# FPGA_1.net
KiCad netlist of a schematic drawn in Altium Designer
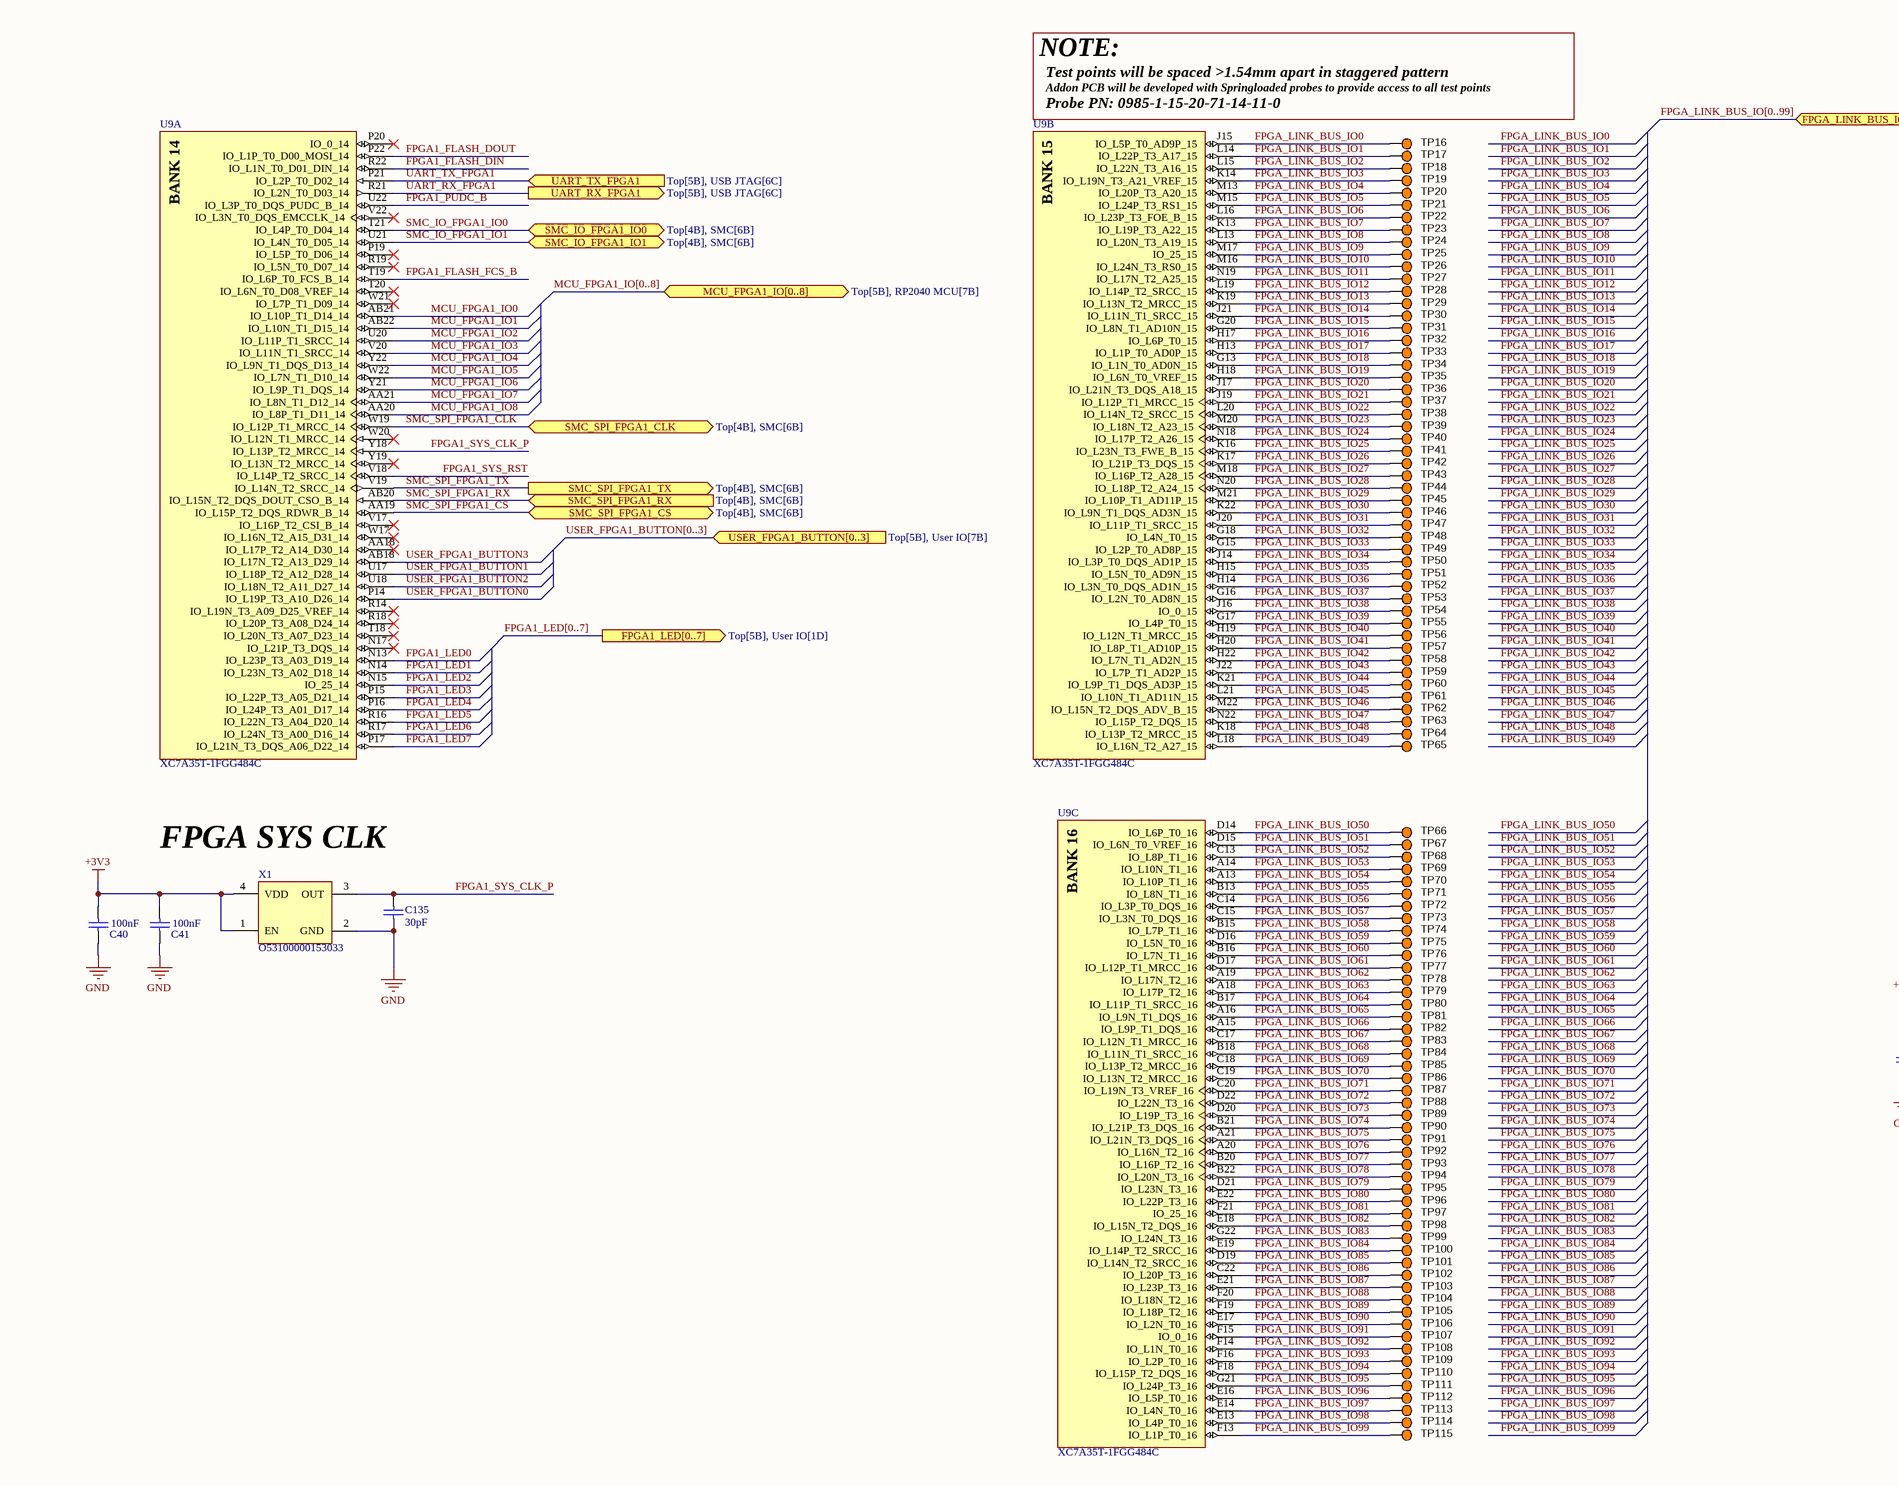
[diagram p0: FPGA_1.SchDoc, top left]
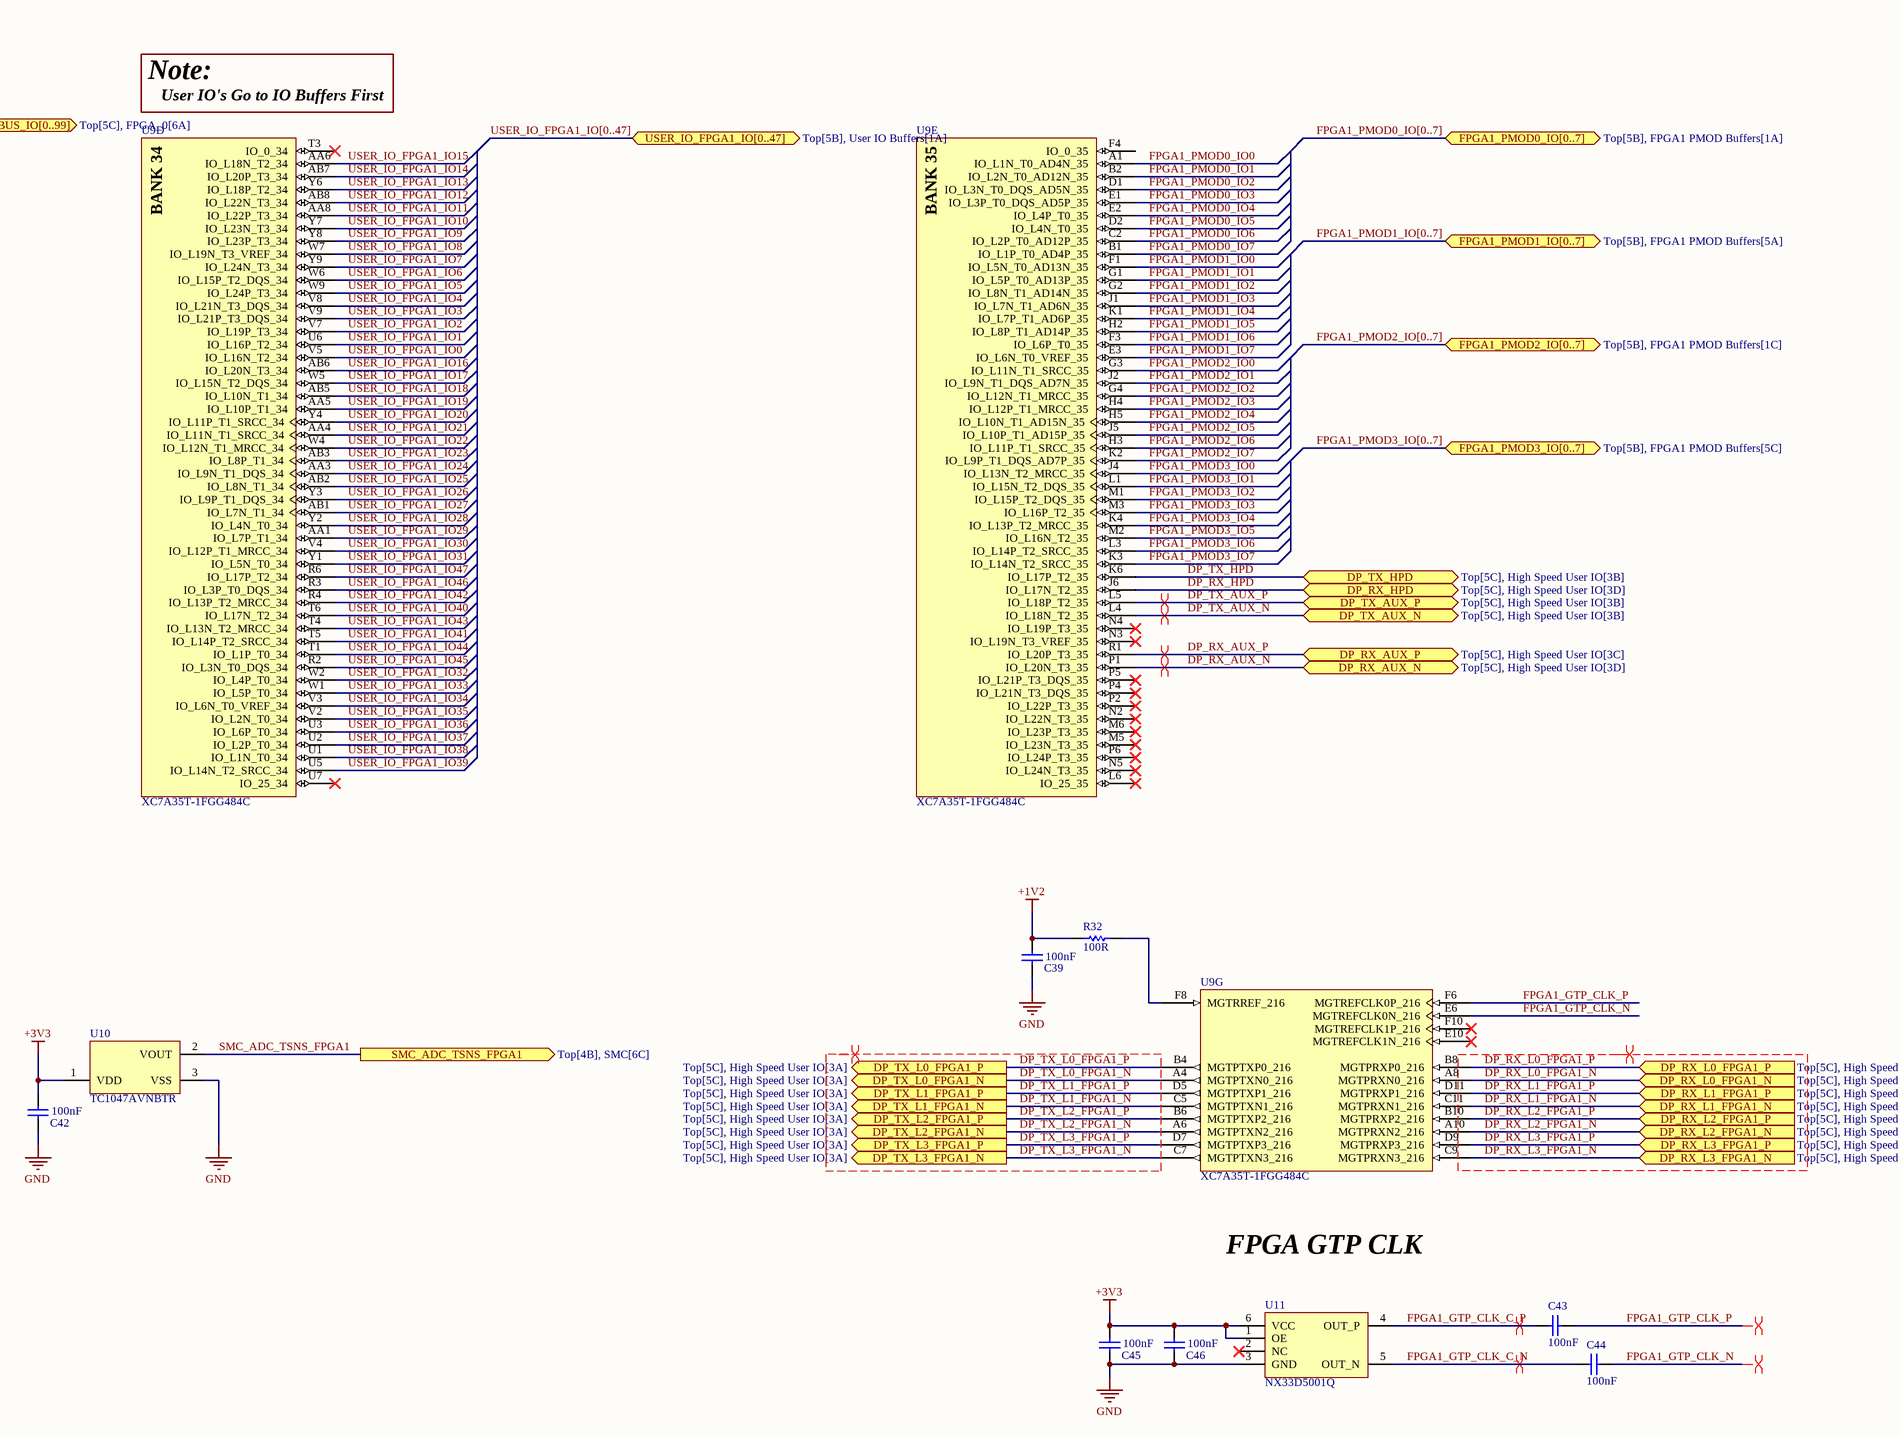
[diagram p1: FPGA_1.SchDoc, top right]
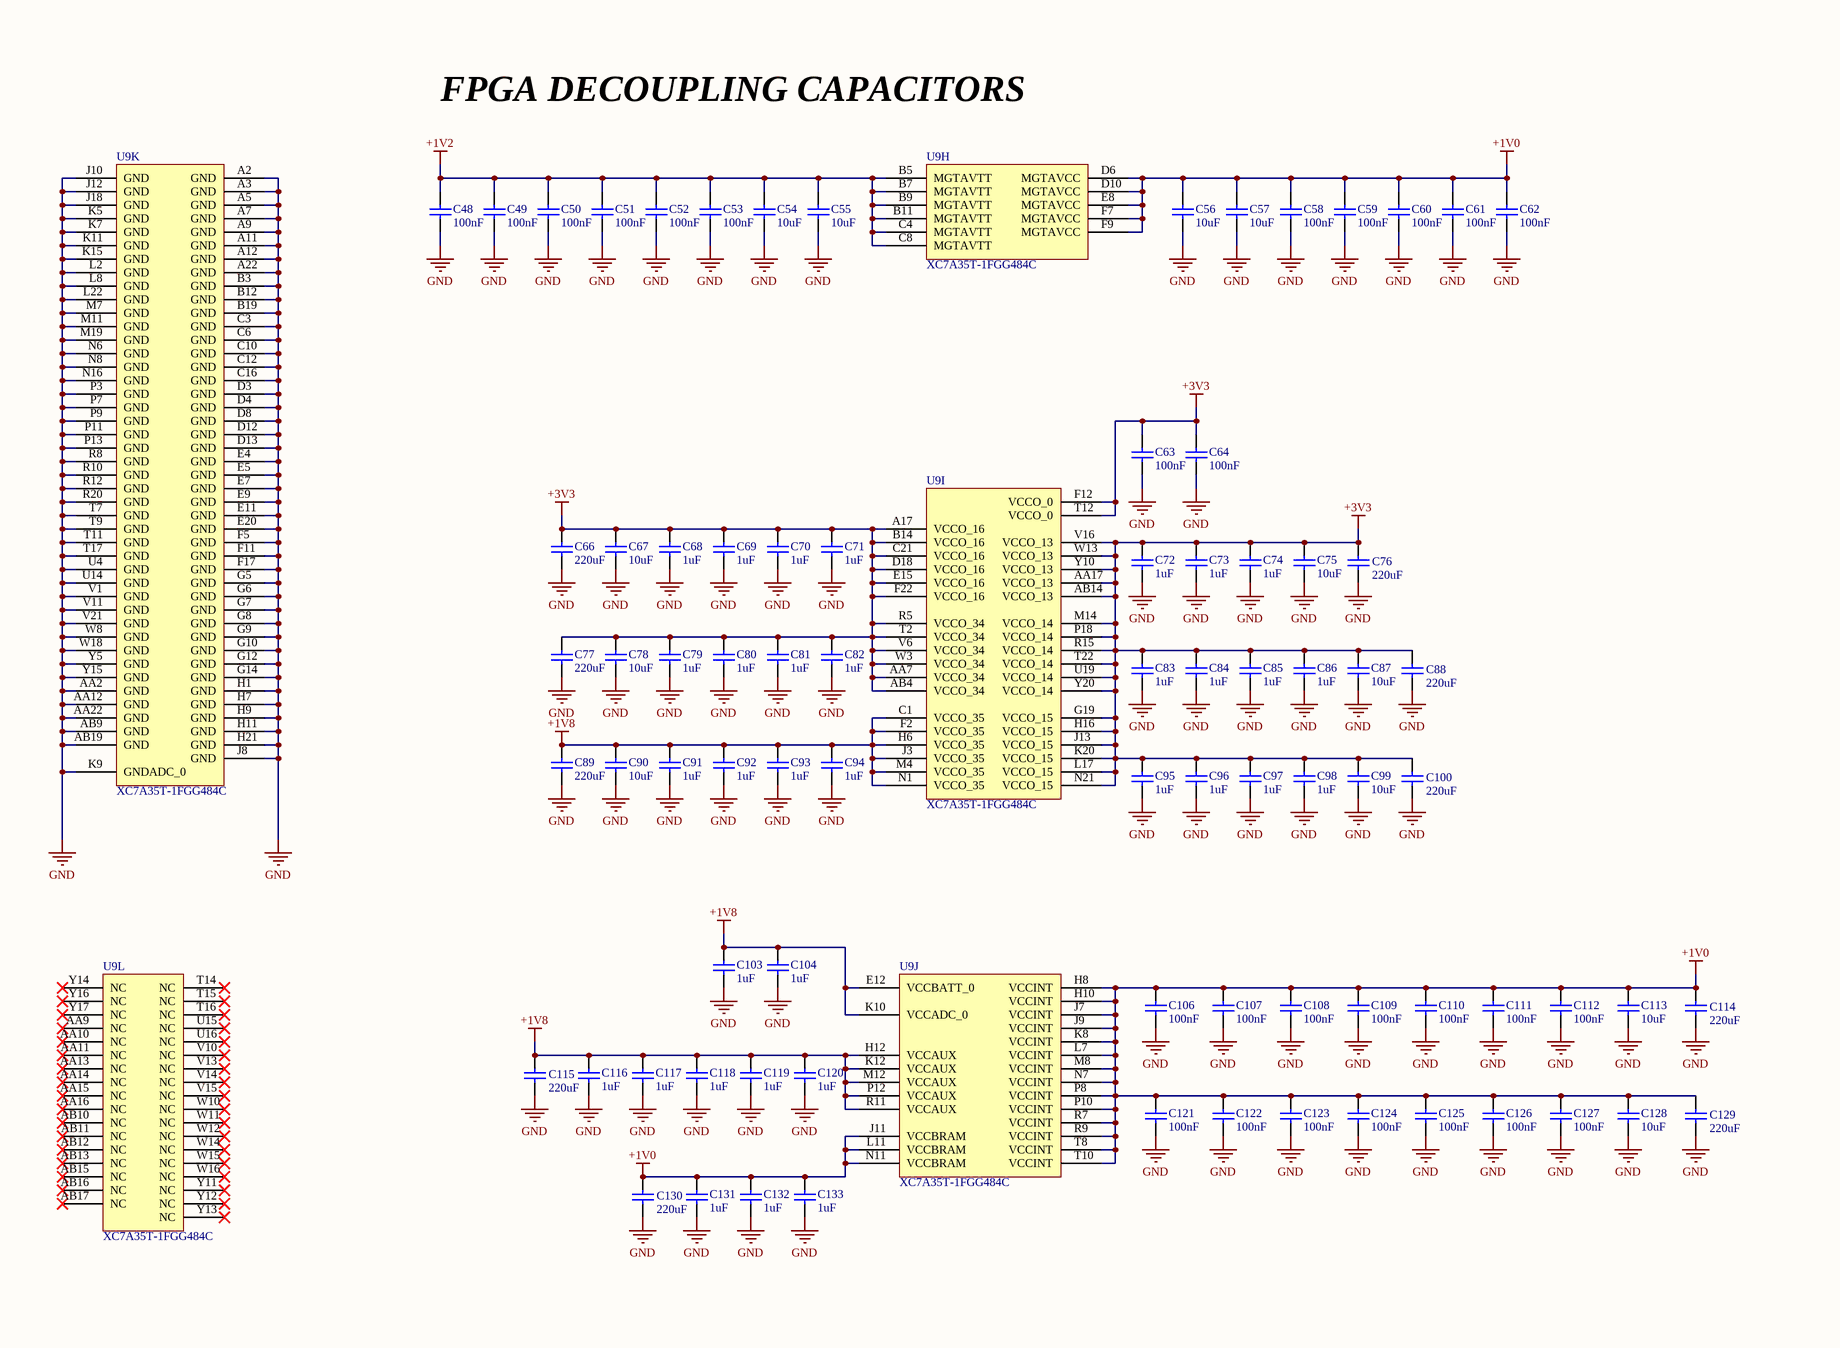
[diagram p2: FPGA_1.SchDoc, bottom left]
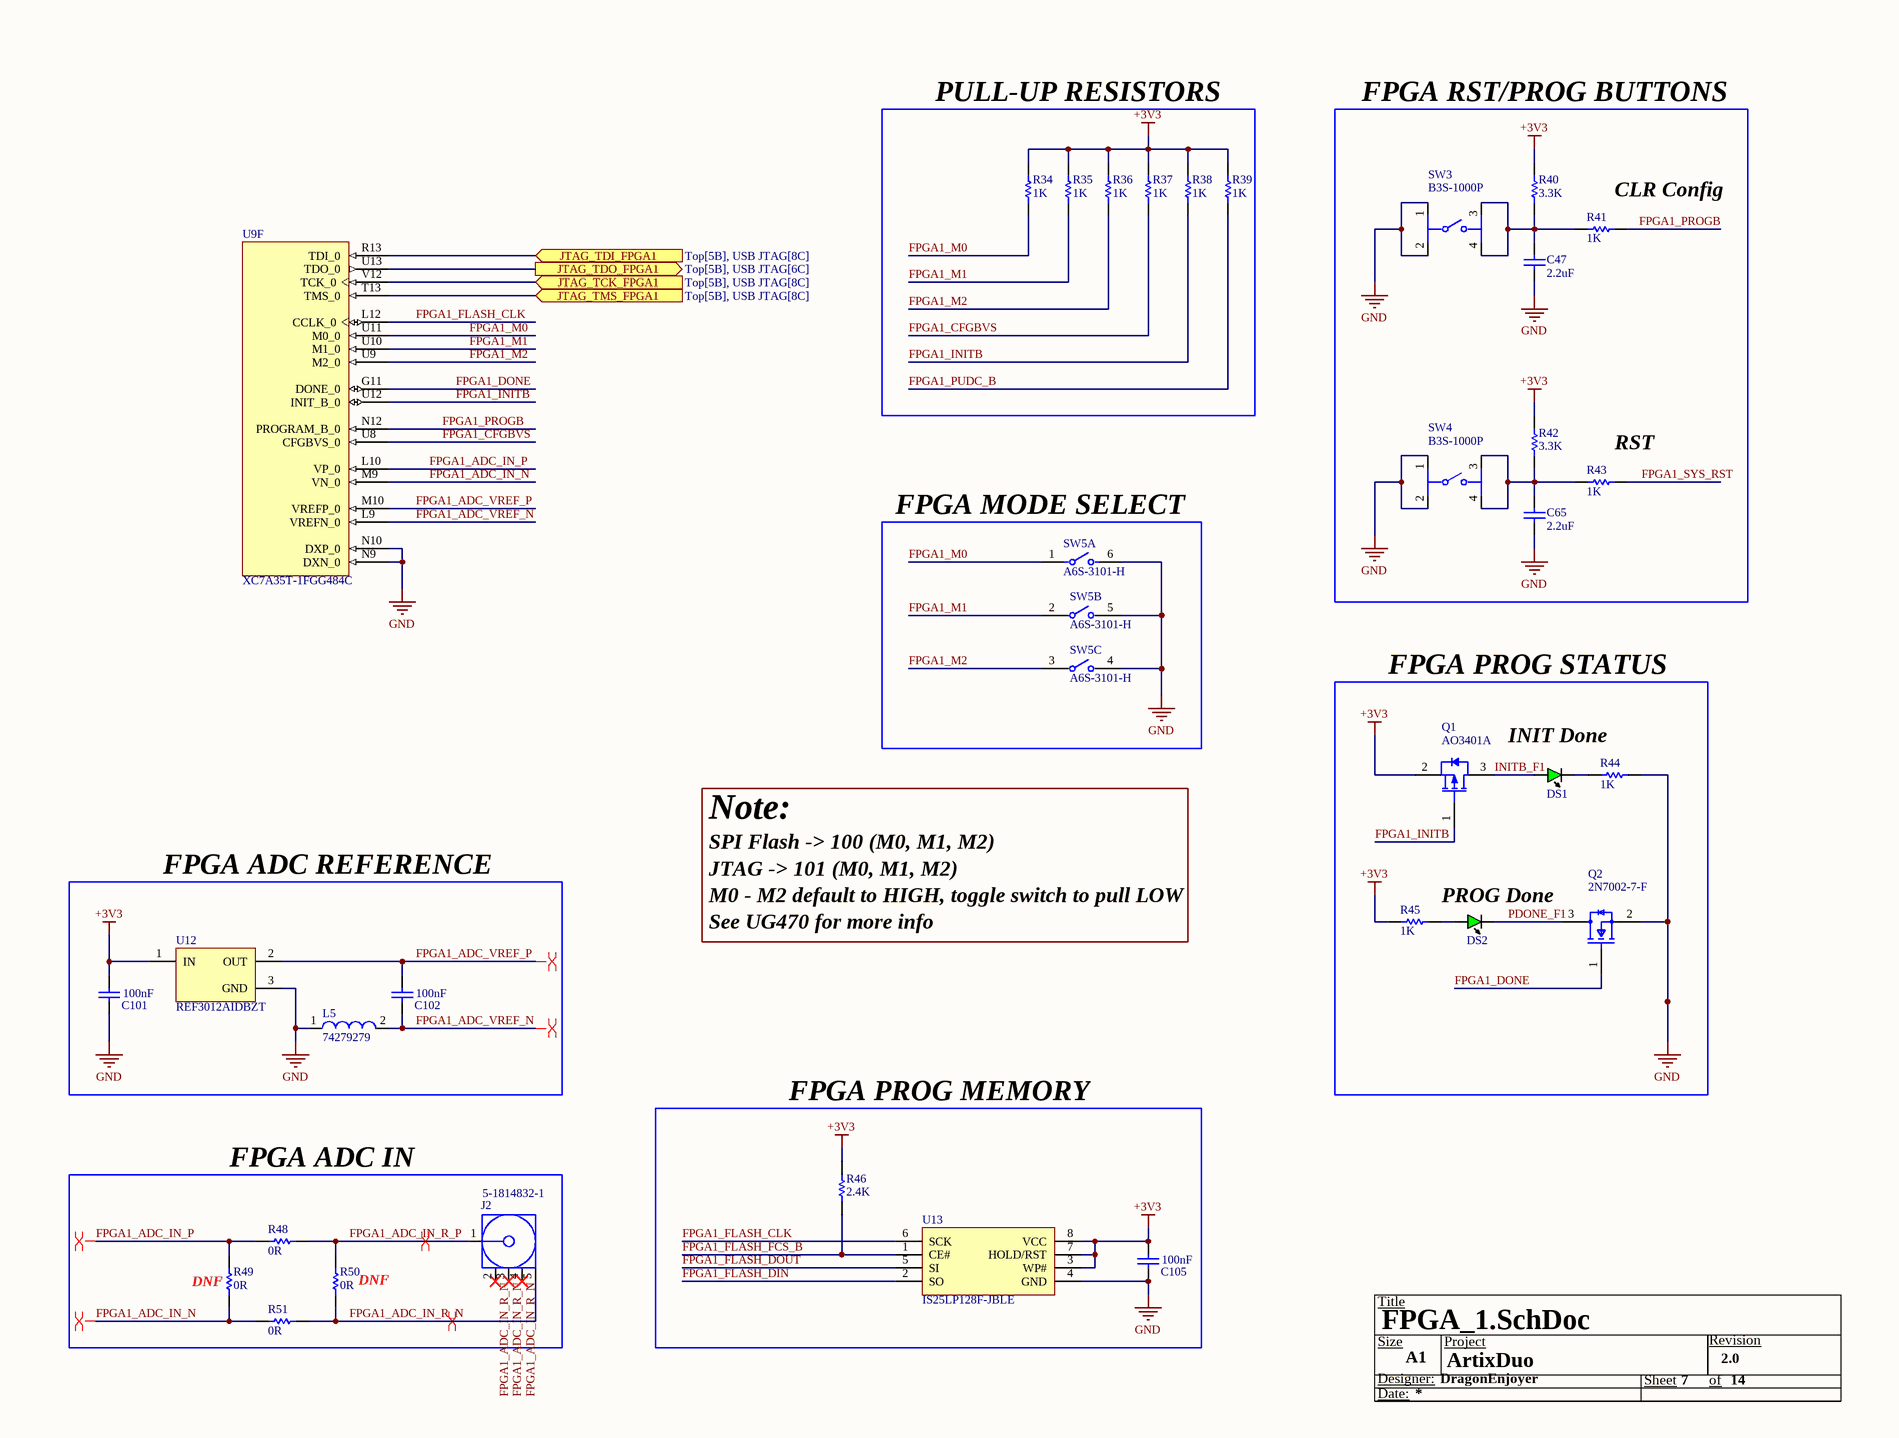
[diagram p3: FPGA_1.SchDoc, bottom right]

(export (version "E")
  (design (tool "Eeschema 10.0.6"))
  (components
    (comp (ref "C39")
      (value "100nF")
      (footprint "CAPC1005X05N")
      (description "Cap Ceramic 0.1uF 50V X7R 20% SMD 0402 125°C Paper T/R GRM155R71H104ME14J")
      (fields (field (name "VOLTAGE") "50V"))
      (libsource (lib "Main Workspace") (part "CAP"))
    )
    (comp (ref "C40")
      (value "100nF")
      (footprint "CAPC1005X05N")
      (description "Cap Ceramic 0.1uF 50V X7R 20% SMD 0402 125°C Paper T/R GRM155R71H104ME14J")
      (fields (field (name "VOLTAGE") "50V"))
      (libsource (lib "Main Workspace") (part "CAP"))
    )
    (comp (ref "C41")
      (value "100nF")
      (footprint "CAPC1005X05N")
      (description "Cap Ceramic 0.1uF 50V X7R 20% SMD 0402 125°C Paper T/R GRM155R71H104ME14J")
      (fields (field (name "VOLTAGE") "50V"))
      (libsource (lib "Main Workspace") (part "CAP"))
    )
    (comp (ref "C42")
      (value "100nF")
      (footprint "CAPC1005X05N")
      (description "Cap Ceramic 0.1uF 50V X7R 20% SMD 0402 125°C Paper T/R GRM155R71H104ME14J")
      (fields (field (name "VOLTAGE") "50V"))
      (libsource (lib "Main Workspace") (part "CAP"))
    )
    (comp (ref "C43")
      (value "100nF")
      (footprint "CAPC1005X05N")
      (description "Cap Ceramic 0.1uF 50V X7R 20% SMD 0402 125°C Paper T/R GRM155R71H104ME14J")
      (fields (field (name "VOLTAGE") "50V"))
      (libsource (lib "Main Workspace") (part "CAP"))
    )
    (comp (ref "C44")
      (value "100nF")
      (footprint "CAPC1005X05N")
      (description "Cap Ceramic 0.1uF 50V X7R 20% SMD 0402 125°C Paper T/R GRM155R71H104ME14J")
      (fields (field (name "VOLTAGE") "50V"))
      (libsource (lib "Main Workspace") (part "CAP"))
    )
    (comp (ref "C45")
      (value "100nF")
      (footprint "CAPC1005X05N")
      (description "Cap Ceramic 0.1uF 50V X7R 20% SMD 0402 125°C Paper T/R GRM155R71H104ME14J")
      (fields (field (name "VOLTAGE") "50V"))
      (libsource (lib "Main Workspace") (part "CAP"))
    )
    (comp (ref "C46")
      (value "100nF")
      (footprint "CAPC1005X05N")
      (description "Cap Ceramic 0.1uF 50V X7R 20% SMD 0402 125°C Paper T/R GRM155R71H104ME14J")
      (fields (field (name "VOLTAGE") "50V"))
      (libsource (lib "Main Workspace") (part "CAP"))
    )
    (comp (ref "C47")
      (value "2.2uF")
      (footprint "CAPC1005X55X25NL05T10")
      (description "GRM155R60J225ME15D")
      (fields (field (name "MANUFACTURER") "Murata"))
      (libsource (lib "Altium Content Vault") (part "CAP"))
    )
    (comp (ref "C48")
      (value "100nF")
      (footprint "CAPC1005X05N")
      (description "0402 0.1 uF 25 V ±10% Tolerance X7R SMT Multilayer Ceramic Capacitor")
      (fields (field (name "TOLERANCE") "10%") (field (name "Comment") "GRM155R71E104KE14J"))
      (libsource (lib "Main Workspace") (part "CAP"))
    )
    (comp (ref "C49")
      (value "100nF")
      (footprint "CAPC1005X05N")
      (description "0402 0.1 uF 25 V ±10% Tolerance X7R SMT Multilayer Ceramic Capacitor")
      (fields (field (name "TOLERANCE") "10%") (field (name "Comment") "GRM155R71E104KE14J"))
      (libsource (lib "Main Workspace") (part "CAP"))
    )
    (comp (ref "C50")
      (value "100nF")
      (footprint "CAPC1005X05N")
      (description "0402 0.1 uF 25 V ±10% Tolerance X7R SMT Multilayer Ceramic Capacitor")
      (fields (field (name "TOLERANCE") "10%") (field (name "Comment") "GRM155R71E104KE14J"))
      (libsource (lib "Main Workspace") (part "CAP"))
    )
    (comp (ref "C51")
      (value "100nF")
      (footprint "CAPC1005X05N")
      (description "0402 0.1 uF 25 V ±10% Tolerance X7R SMT Multilayer Ceramic Capacitor")
      (fields (field (name "TOLERANCE") "10%") (field (name "Comment") "GRM155R71E104KE14J"))
      (libsource (lib "Main Workspace") (part "CAP"))
    )
    (comp (ref "C52")
      (value "100nF")
      (footprint "CAPC1005X05N")
      (description "0402 0.1 uF 25 V ±10% Tolerance X7R SMT Multilayer Ceramic Capacitor")
      (fields (field (name "TOLERANCE") "10%") (field (name "Comment") "GRM155R71E104KE14J"))
      (libsource (lib "Main Workspace") (part "CAP"))
    )
    (comp (ref "C53")
      (value "100nF")
      (footprint "CAPC1005X05N")
      (description "0402 0.1 uF 25 V ±10% Tolerance X7R SMT Multilayer Ceramic Capacitor")
      (fields (field (name "TOLERANCE") "10%") (field (name "Comment") "GRM155R71E104KE14J"))
      (libsource (lib "Main Workspace") (part "CAP"))
    )
    (comp (ref "C54")
      (value "10uF")
      (footprint "CAPC1608X05N")
      (description "Cap 10UF 6.3VDC X5R 20% SMD 0603 Paper Tape")
      (fields (field (name "TOLERANCE") "20%") (field (name "Comment") "GRM185R60J106ME15J"))
      (libsource (lib "Main Workspace") (part "CAP"))
    )
    (comp (ref "C55")
      (value "10uF")
      (footprint "CAPC1608X05N")
      (description "Cap 10UF 6.3VDC X5R 20% SMD 0603 Paper Tape")
      (fields (field (name "TOLERANCE") "20%") (field (name "Comment") "GRM185R60J106ME15J"))
      (libsource (lib "Main Workspace") (part "CAP"))
    )
    (comp (ref "C56")
      (value "10uF")
      (footprint "CAPC1608X05N")
      (description "Cap 10UF 6.3VDC X5R 20% SMD 0603 Paper Tape")
      (fields (field (name "TOLERANCE") "20%") (field (name "Comment") "GRM185R60J106ME15J"))
      (libsource (lib "Main Workspace") (part "CAP"))
    )
    (comp (ref "C57")
      (value "10uF")
      (footprint "CAPC1608X05N")
      (description "Cap 10UF 6.3VDC X5R 20% SMD 0603 Paper Tape")
      (fields (field (name "TOLERANCE") "20%") (field (name "Comment") "GRM185R60J106ME15J"))
      (libsource (lib "Main Workspace") (part "CAP"))
    )
    (comp (ref "C58")
      (value "100nF")
      (footprint "CAPC1005X05N")
      (description "0402 0.1 uF 25 V ±10% Tolerance X7R SMT Multilayer Ceramic Capacitor")
      (fields (field (name "TOLERANCE") "10%") (field (name "Comment") "GRM155R71E104KE14J"))
      (libsource (lib "Main Workspace") (part "CAP"))
    )
    (comp (ref "C59")
      (value "100nF")
      (footprint "CAPC1005X05N")
      (description "0402 0.1 uF 25 V ±10% Tolerance X7R SMT Multilayer Ceramic Capacitor")
      (fields (field (name "TOLERANCE") "10%") (field (name "Comment") "GRM155R71E104KE14J"))
      (libsource (lib "Main Workspace") (part "CAP"))
    )
    (comp (ref "C60")
      (value "100nF")
      (footprint "CAPC1005X05N")
      (description "0402 0.1 uF 25 V ±10% Tolerance X7R SMT Multilayer Ceramic Capacitor")
      (fields (field (name "TOLERANCE") "10%") (field (name "Comment") "GRM155R71E104KE14J"))
      (libsource (lib "Main Workspace") (part "CAP"))
    )
    (comp (ref "C61")
      (value "100nF")
      (footprint "CAPC1005X05N")
      (description "0402 0.1 uF 25 V ±10% Tolerance X7R SMT Multilayer Ceramic Capacitor")
      (fields (field (name "TOLERANCE") "10%") (field (name "Comment") "GRM155R71E104KE14J"))
      (libsource (lib "Main Workspace") (part "CAP"))
    )
    (comp (ref "C62")
      (value "100nF")
      (footprint "CAPC1005X05N")
      (description "0402 0.1 uF 25 V ±10% Tolerance X7R SMT Multilayer Ceramic Capacitor")
      (fields (field (name "TOLERANCE") "10%") (field (name "Comment") "GRM155R71E104KE14J"))
      (libsource (lib "Main Workspace") (part "CAP"))
    )
    (comp (ref "C63")
      (value "100nF")
      (footprint "CAPC1005X05N")
      (description "0402 0.1 uF 25 V ±10% Tolerance X7R SMT Multilayer Ceramic Capacitor")
      (fields (field (name "TOLERANCE") "10%") (field (name "Comment") "GRM155R71E104KE14J"))
      (libsource (lib "Main Workspace") (part "CAP"))
    )
    (comp (ref "C64")
      (value "100nF")
      (footprint "CAPC1005X05N")
      (description "0402 0.1 uF 25 V ±10% Tolerance X7R SMT Multilayer Ceramic Capacitor")
      (fields (field (name "TOLERANCE") "10%") (field (name "Comment") "GRM155R71E104KE14J"))
      (libsource (lib "Main Workspace") (part "CAP"))
    )
    (comp (ref "C65")
      (value "2.2uF")
      (footprint "CAPC1005X55X25NL05T10")
      (description "GRM155R60J225ME15D")
      (fields (field (name "MANUFACTURER") "Murata"))
      (libsource (lib "Altium Content Vault") (part "CAP"))
    )
    (comp (ref "C66")
      (value "220uF")
      (footprint "CAPC3225X25N")
      (description "Cap Ceramic 220uF 6.3V X5R 20% SMD 1210 85°C Emboss T/R GRM32ER60J227ME05K")
      (libsource (lib "Main Workspace") (part "CAP"))
    )
    (comp (ref "C67")
      (value "10uF")
      (footprint "CAPC1608X05N")
      (description "Cap 10UF 6.3VDC X5R 20% SMD 0603 Paper Tape")
      (fields (field (name "TOLERANCE") "20%") (field (name "Comment") "GRM185R60J106ME15J"))
      (libsource (lib "Main Workspace") (part "CAP"))
    )
    (comp (ref "C68")
      (value "1uF")
      (footprint "CAPC1005X05N")
      (fields (field (name "TOLERANCE") "20%") (field (name "Comment") "GRM153R61A105ME95D"))
      (libsource (lib "Main Workspace") (part "CAP"))
    )
    (comp (ref "C69")
      (value "1uF")
      (footprint "CAPC1005X05N")
      (fields (field (name "TOLERANCE") "20%") (field (name "Comment") "GRM153R61A105ME95D"))
      (libsource (lib "Main Workspace") (part "CAP"))
    )
    (comp (ref "C70")
      (value "1uF")
      (footprint "CAPC1005X05N")
      (fields (field (name "TOLERANCE") "20%") (field (name "Comment") "GRM153R61A105ME95D"))
      (libsource (lib "Main Workspace") (part "CAP"))
    )
    (comp (ref "C71")
      (value "1uF")
      (footprint "CAPC1005X05N")
      (fields (field (name "TOLERANCE") "20%") (field (name "Comment") "GRM153R61A105ME95D"))
      (libsource (lib "Main Workspace") (part "CAP"))
    )
    (comp (ref "C72")
      (value "1uF")
      (footprint "CAPC1005X05N")
      (fields (field (name "TOLERANCE") "20%") (field (name "Comment") "GRM153R61A105ME95D"))
      (libsource (lib "Main Workspace") (part "CAP"))
    )
    (comp (ref "C73")
      (value "1uF")
      (footprint "CAPC1005X05N")
      (fields (field (name "TOLERANCE") "20%") (field (name "Comment") "GRM153R61A105ME95D"))
      (libsource (lib "Main Workspace") (part "CAP"))
    )
    (comp (ref "C74")
      (value "1uF")
      (footprint "CAPC1005X05N")
      (fields (field (name "TOLERANCE") "20%") (field (name "Comment") "GRM153R61A105ME95D"))
      (libsource (lib "Main Workspace") (part "CAP"))
    )
    (comp (ref "C75")
      (value "10uF")
      (footprint "CAPC1608X05N")
      (description "Cap 10UF 6.3VDC X5R 20% SMD 0603 Paper Tape")
      (fields (field (name "TOLERANCE") "20%") (field (name "Comment") "GRM185R60J106ME15J"))
      (libsource (lib "Main Workspace") (part "CAP"))
    )
    (comp (ref "C76")
      (value "220uF")
      (footprint "CAPC3225X25N")
      (description "Cap Ceramic 220uF 6.3V X5R 20% SMD 1210 85°C Emboss T/R GRM32ER60J227ME05K")
      (libsource (lib "Main Workspace") (part "CAP"))
    )
    (comp (ref "C77")
      (value "220uF")
      (footprint "CAPC3225X25N")
      (description "Cap Ceramic 220uF 6.3V X5R 20% SMD 1210 85°C Emboss T/R GRM32ER60J227ME05K")
      (libsource (lib "Main Workspace") (part "CAP"))
    )
    (comp (ref "C78")
      (value "10uF")
      (footprint "CAPC1608X05N")
      (description "Cap 10UF 6.3VDC X5R 20% SMD 0603 Paper Tape")
      (fields (field (name "TOLERANCE") "20%") (field (name "Comment") "GRM185R60J106ME15J"))
      (libsource (lib "Main Workspace") (part "CAP"))
    )
    (comp (ref "C79")
      (value "1uF")
      (footprint "CAPC1005X05N")
      (fields (field (name "TOLERANCE") "20%") (field (name "Comment") "GRM153R61A105ME95D"))
      (libsource (lib "Main Workspace") (part "CAP"))
    )
    (comp (ref "C80")
      (value "1uF")
      (footprint "CAPC1005X05N")
      (fields (field (name "TOLERANCE") "20%") (field (name "Comment") "GRM153R61A105ME95D"))
      (libsource (lib "Main Workspace") (part "CAP"))
    )
    (comp (ref "C81")
      (value "1uF")
      (footprint "CAPC1005X05N")
      (fields (field (name "TOLERANCE") "20%") (field (name "Comment") "GRM153R61A105ME95D"))
      (libsource (lib "Main Workspace") (part "CAP"))
    )
    (comp (ref "C82")
      (value "1uF")
      (footprint "CAPC1005X05N")
      (fields (field (name "TOLERANCE") "20%") (field (name "Comment") "GRM153R61A105ME95D"))
      (libsource (lib "Main Workspace") (part "CAP"))
    )
    (comp (ref "C83")
      (value "1uF")
      (footprint "CAPC1005X05N")
      (fields (field (name "TOLERANCE") "20%") (field (name "Comment") "GRM153R61A105ME95D"))
      (libsource (lib "Main Workspace") (part "CAP"))
    )
    (comp (ref "C84")
      (value "1uF")
      (footprint "CAPC1005X05N")
      (fields (field (name "TOLERANCE") "20%") (field (name "Comment") "GRM153R61A105ME95D"))
      (libsource (lib "Main Workspace") (part "CAP"))
    )
    (comp (ref "C85")
      (value "1uF")
      (footprint "CAPC1005X05N")
      (fields (field (name "TOLERANCE") "20%") (field (name "Comment") "GRM153R61A105ME95D"))
      (libsource (lib "Main Workspace") (part "CAP"))
    )
    (comp (ref "C86")
      (value "1uF")
      (footprint "CAPC1005X05N")
      (fields (field (name "TOLERANCE") "20%") (field (name "Comment") "GRM153R61A105ME95D"))
      (libsource (lib "Main Workspace") (part "CAP"))
    )
    (comp (ref "C87")
      (value "10uF")
      (footprint "CAPC1608X05N")
      (description "Cap 10UF 6.3VDC X5R 20% SMD 0603 Paper Tape")
      (fields (field (name "TOLERANCE") "20%") (field (name "Comment") "GRM185R60J106ME15J"))
      (libsource (lib "Main Workspace") (part "CAP"))
    )
    (comp (ref "C88")
      (value "220uF")
      (footprint "CAPC3225X25N")
      (description "Cap Ceramic 220uF 6.3V X5R 20% SMD 1210 85°C Emboss T/R GRM32ER60J227ME05K")
      (libsource (lib "Main Workspace") (part "CAP"))
    )
    (comp (ref "C89")
      (value "220uF")
      (footprint "CAPC3225X25N")
      (description "Cap Ceramic 220uF 6.3V X5R 20% SMD 1210 85°C Emboss T/R GRM32ER60J227ME05K")
      (libsource (lib "Main Workspace") (part "CAP"))
    )
    (comp (ref "C90")
      (value "10uF")
      (footprint "CAPC1608X05N")
      (description "Cap 10UF 6.3VDC X5R 20% SMD 0603 Paper Tape")
      (fields (field (name "TOLERANCE") "20%") (field (name "Comment") "GRM185R60J106ME15J"))
      (libsource (lib "Main Workspace") (part "CAP"))
    )
    (comp (ref "C91")
      (value "1uF")
      (footprint "CAPC1005X05N")
      (fields (field (name "TOLERANCE") "20%") (field (name "Comment") "GRM153R61A105ME95D"))
      (libsource (lib "Main Workspace") (part "CAP"))
    )
    (comp (ref "C92")
      (value "1uF")
      (footprint "CAPC1005X05N")
      (fields (field (name "TOLERANCE") "20%") (field (name "Comment") "GRM153R61A105ME95D"))
      (libsource (lib "Main Workspace") (part "CAP"))
    )
    (comp (ref "C93")
      (value "1uF")
      (footprint "CAPC1005X05N")
      (fields (field (name "TOLERANCE") "20%") (field (name "Comment") "GRM153R61A105ME95D"))
      (libsource (lib "Main Workspace") (part "CAP"))
    )
    (comp (ref "C94")
      (value "1uF")
      (footprint "CAPC1005X05N")
      (fields (field (name "TOLERANCE") "20%") (field (name "Comment") "GRM153R61A105ME95D"))
      (libsource (lib "Main Workspace") (part "CAP"))
    )
    (comp (ref "C95")
      (value "1uF")
      (footprint "CAPC1005X05N")
      (fields (field (name "TOLERANCE") "20%") (field (name "Comment") "GRM153R61A105ME95D"))
      (libsource (lib "Main Workspace") (part "CAP"))
    )
    (comp (ref "C96")
      (value "1uF")
      (footprint "CAPC1005X05N")
      (fields (field (name "TOLERANCE") "20%") (field (name "Comment") "GRM153R61A105ME95D"))
      (libsource (lib "Main Workspace") (part "CAP"))
    )
    (comp (ref "C97")
      (value "1uF")
      (footprint "CAPC1005X05N")
      (fields (field (name "TOLERANCE") "20%") (field (name "Comment") "GRM153R61A105ME95D"))
      (libsource (lib "Main Workspace") (part "CAP"))
    )
    (comp (ref "C98")
      (value "1uF")
      (footprint "CAPC1005X05N")
      (fields (field (name "TOLERANCE") "20%") (field (name "Comment") "GRM153R61A105ME95D"))
      (libsource (lib "Main Workspace") (part "CAP"))
    )
    (comp (ref "C99")
      (value "10uF")
      (footprint "CAPC1608X05N")
      (description "Cap 10UF 6.3VDC X5R 20% SMD 0603 Paper Tape")
      (fields (field (name "TOLERANCE") "20%") (field (name "Comment") "GRM185R60J106ME15J"))
      (libsource (lib "Main Workspace") (part "CAP"))
    )
    (comp (ref "C100")
      (value "220uF")
      (footprint "CAPC3225X25N")
      (description "Cap Ceramic 220uF 6.3V X5R 20% SMD 1210 85°C Emboss T/R GRM32ER60J227ME05K")
      (libsource (lib "Main Workspace") (part "CAP"))
    )
    (comp (ref "C101")
      (value "100nF")
      (footprint "CAPC1005X05N")
      (description "Cap Ceramic 0.1uF 50V X7R 20% SMD 0402 125°C Paper T/R GRM155R71H104ME14J")
      (fields (field (name "VOLTAGE") "50V"))
      (libsource (lib "Main Workspace") (part "CAP"))
    )
    (comp (ref "C102")
      (value "100nF")
      (footprint "CAPC1005X05N")
      (description "Cap Ceramic 0.1uF 50V X7R 20% SMD 0402 125°C Paper T/R GRM155R71H104ME14J")
      (fields (field (name "VOLTAGE") "50V"))
      (libsource (lib "Main Workspace") (part "CAP"))
    )
    (comp (ref "C103")
      (value "1uF")
      (footprint "CAPC1005X05N")
      (fields (field (name "TOLERANCE") "20%") (field (name "Comment") "GRM153R61A105ME95D"))
      (libsource (lib "Main Workspace") (part "CAP"))
    )
    (comp (ref "C104")
      (value "1uF")
      (footprint "CAPC1005X05N")
      (fields (field (name "TOLERANCE") "20%") (field (name "Comment") "GRM153R61A105ME95D"))
      (libsource (lib "Main Workspace") (part "CAP"))
    )
    (comp (ref "C105")
      (value "100nF")
      (footprint "CAPC1005X05N")
      (description "Cap Ceramic 0.1uF 50V X7R 20% SMD 0402 125°C Paper T/R GRM155R71H104ME14J")
      (fields (field (name "VOLTAGE") "50V"))
      (libsource (lib "Main Workspace") (part "CAP"))
    )
    (comp (ref "C106")
      (value "100nF")
      (footprint "CAPC1005X05N")
      (description "0402 0.1 uF 25 V ±10% Tolerance X7R SMT Multilayer Ceramic Capacitor")
      (fields (field (name "TOLERANCE") "10%") (field (name "Comment") "GRM155R71E104KE14J"))
      (libsource (lib "Main Workspace") (part "CAP"))
    )
    (comp (ref "C107")
      (value "100nF")
      (footprint "CAPC1005X05N")
      (description "0402 0.1 uF 25 V ±10% Tolerance X7R SMT Multilayer Ceramic Capacitor")
      (fields (field (name "TOLERANCE") "10%") (field (name "Comment") "GRM155R71E104KE14J"))
      (libsource (lib "Main Workspace") (part "CAP"))
    )
    (comp (ref "C108")
      (value "100nF")
      (footprint "CAPC1005X05N")
      (description "0402 0.1 uF 25 V ±10% Tolerance X7R SMT Multilayer Ceramic Capacitor")
      (fields (field (name "TOLERANCE") "10%") (field (name "Comment") "GRM155R71E104KE14J"))
      (libsource (lib "Main Workspace") (part "CAP"))
    )
    (comp (ref "C109")
      (value "100nF")
      (footprint "CAPC1005X05N")
      (description "0402 0.1 uF 25 V ±10% Tolerance X7R SMT Multilayer Ceramic Capacitor")
      (fields (field (name "TOLERANCE") "10%") (field (name "Comment") "GRM155R71E104KE14J"))
      (libsource (lib "Main Workspace") (part "CAP"))
    )
    (comp (ref "C110")
      (value "100nF")
      (footprint "CAPC1005X05N")
      (description "0402 0.1 uF 25 V ±10% Tolerance X7R SMT Multilayer Ceramic Capacitor")
      (fields (field (name "TOLERANCE") "10%") (field (name "Comment") "GRM155R71E104KE14J"))
      (libsource (lib "Main Workspace") (part "CAP"))
    )
    (comp (ref "C111")
      (value "100nF")
      (footprint "CAPC1005X05N")
      (description "0402 0.1 uF 25 V ±10% Tolerance X7R SMT Multilayer Ceramic Capacitor")
      (fields (field (name "TOLERANCE") "10%") (field (name "Comment") "GRM155R71E104KE14J"))
      (libsource (lib "Main Workspace") (part "CAP"))
    )
    (comp (ref "C112")
      (value "100nF")
      (footprint "CAPC1005X05N")
      (description "0402 0.1 uF 25 V ±10% Tolerance X7R SMT Multilayer Ceramic Capacitor")
      (fields (field (name "TOLERANCE") "10%") (field (name "Comment") "GRM155R71E104KE14J"))
      (libsource (lib "Main Workspace") (part "CAP"))
    )
    (comp (ref "C113")
      (value "10uF")
      (footprint "CAPC1608X05N")
      (description "Cap 10UF 6.3VDC X5R 20% SMD 0603 Paper Tape")
      (fields (field (name "TOLERANCE") "20%") (field (name "Comment") "GRM185R60J106ME15J"))
      (libsource (lib "Main Workspace") (part "CAP"))
    )
    (comp (ref "C114")
      (value "220uF")
      (footprint "CAPC3225X25N")
      (description "Cap Ceramic 220uF 6.3V X5R 20% SMD 1210 85°C Emboss T/R GRM32ER60J227ME05K")
      (libsource (lib "Main Workspace") (part "CAP"))
    )
    (comp (ref "C115")
      (value "220uF")
      (footprint "CAPC3225X25N")
      (description "Cap Ceramic 220uF 6.3V X5R 20% SMD 1210 85°C Emboss T/R GRM32ER60J227ME05K")
      (libsource (lib "Main Workspace") (part "CAP"))
    )
    (comp (ref "C116")
      (value "1uF")
      (footprint "CAPC1005X05N")
      (fields (field (name "TOLERANCE") "20%") (field (name "Comment") "GRM153R61A105ME95D"))
      (libsource (lib "Main Workspace") (part "CAP"))
    )
    (comp (ref "C117")
      (value "1uF")
      (footprint "CAPC1005X05N")
      (fields (field (name "TOLERANCE") "20%") (field (name "Comment") "GRM153R61A105ME95D"))
      (libsource (lib "Main Workspace") (part "CAP"))
    )
    (comp (ref "C118")
      (value "1uF")
      (footprint "CAPC1005X05N")
      (fields (field (name "TOLERANCE") "20%") (field (name "Comment") "GRM153R61A105ME95D"))
      (libsource (lib "Main Workspace") (part "CAP"))
    )
    (comp (ref "C119")
      (value "1uF")
      (footprint "CAPC1005X05N")
      (fields (field (name "TOLERANCE") "20%") (field (name "Comment") "GRM153R61A105ME95D"))
      (libsource (lib "Main Workspace") (part "CAP"))
    )
    (comp (ref "C120")
      (value "1uF")
      (footprint "CAPC1005X05N")
      (fields (field (name "TOLERANCE") "20%") (field (name "Comment") "GRM153R61A105ME95D"))
      (libsource (lib "Main Workspace") (part "CAP"))
    )
    (comp (ref "C121")
      (value "100nF")
      (footprint "CAPC1005X05N")
      (description "0402 0.1 uF 25 V ±10% Tolerance X7R SMT Multilayer Ceramic Capacitor")
      (fields (field (name "TOLERANCE") "10%") (field (name "Comment") "GRM155R71E104KE14J"))
      (libsource (lib "Main Workspace") (part "CAP"))
    )
    (comp (ref "C122")
      (value "100nF")
      (footprint "CAPC1005X05N")
      (description "0402 0.1 uF 25 V ±10% Tolerance X7R SMT Multilayer Ceramic Capacitor")
      (fields (field (name "TOLERANCE") "10%") (field (name "Comment") "GRM155R71E104KE14J"))
      (libsource (lib "Main Workspace") (part "CAP"))
    )
    (comp (ref "C123")
      (value "100nF")
      (footprint "CAPC1005X05N")
      (description "0402 0.1 uF 25 V ±10% Tolerance X7R SMT Multilayer Ceramic Capacitor")
      (fields (field (name "TOLERANCE") "10%") (field (name "Comment") "GRM155R71E104KE14J"))
      (libsource (lib "Main Workspace") (part "CAP"))
    )
    (comp (ref "C124")
      (value "100nF")
      (footprint "CAPC1005X05N")
      (description "0402 0.1 uF 25 V ±10% Tolerance X7R SMT Multilayer Ceramic Capacitor")
      (fields (field (name "TOLERANCE") "10%") (field (name "Comment") "GRM155R71E104KE14J"))
      (libsource (lib "Main Workspace") (part "CAP"))
    )
    (comp (ref "C125")
      (value "100nF")
      (footprint "CAPC1005X05N")
      (description "0402 0.1 uF 25 V ±10% Tolerance X7R SMT Multilayer Ceramic Capacitor")
      (fields (field (name "TOLERANCE") "10%") (field (name "Comment") "GRM155R71E104KE14J"))
      (libsource (lib "Main Workspace") (part "CAP"))
    )
    (comp (ref "C126")
      (value "100nF")
      (footprint "CAPC1005X05N")
      (description "0402 0.1 uF 25 V ±10% Tolerance X7R SMT Multilayer Ceramic Capacitor")
      (fields (field (name "TOLERANCE") "10%") (field (name "Comment") "GRM155R71E104KE14J"))
      (libsource (lib "Main Workspace") (part "CAP"))
    )
    (comp (ref "C127")
      (value "100nF")
      (footprint "CAPC1005X05N")
      (description "0402 0.1 uF 25 V ±10% Tolerance X7R SMT Multilayer Ceramic Capacitor")
      (fields (field (name "TOLERANCE") "10%") (field (name "Comment") "GRM155R71E104KE14J"))
      (libsource (lib "Main Workspace") (part "CAP"))
    )
    (comp (ref "C128")
      (value "10uF")
      (footprint "CAPC1608X05N")
      (description "Cap 10UF 6.3VDC X5R 20% SMD 0603 Paper Tape")
      (fields (field (name "TOLERANCE") "20%") (field (name "Comment") "GRM185R60J106ME15J"))
      (libsource (lib "Main Workspace") (part "CAP"))
    )
    (comp (ref "C129")
      (value "220uF")
      (footprint "CAPC3225X25N")
      (description "Cap Ceramic 220uF 6.3V X5R 20% SMD 1210 85°C Emboss T/R GRM32ER60J227ME05K")
      (libsource (lib "Main Workspace") (part "CAP"))
    )
    (comp (ref "C130")
      (value "220uF")
      (footprint "CAPC3225X25N")
      (description "Cap Ceramic 220uF 6.3V X5R 20% SMD 1210 85°C Emboss T/R GRM32ER60J227ME05K")
      (libsource (lib "Main Workspace") (part "CAP"))
    )
    (comp (ref "C131")
      (value "1uF")
      (footprint "CAPC1005X05N")
      (fields (field (name "TOLERANCE") "20%") (field (name "Comment") "GRM153R61A105ME95D"))
      (libsource (lib "Main Workspace") (part "CAP"))
    )
    (comp (ref "C132")
      (value "1uF")
      (footprint "CAPC1005X05N")
      (fields (field (name "TOLERANCE") "20%") (field (name "Comment") "GRM153R61A105ME95D"))
      (libsource (lib "Main Workspace") (part "CAP"))
    )
    (comp (ref "C133")
      (value "1uF")
      (footprint "CAPC1005X05N")
      (fields (field (name "TOLERANCE") "20%") (field (name "Comment") "GRM153R61A105ME95D"))
      (libsource (lib "Main Workspace") (part "CAP"))
    )
    (comp (ref "C135")
      (value "30pF")
      (footprint "CAPC1005X56X25NL10T15")
      (description "04025A300JAT2A")
      (fields (field (name "MANUFACTURER") "AVX Interconnect / Elco"))
      (libsource (lib "Altium Content Vault") (part "CAP"))
    )
    (comp (ref "DS1")
      (value "SMLLX0603GWTR")
      (footprint "LUMX-SML-LX0603_V")
      (description "LED GREEN DIFFUSED SMD")
      (libsource (lib "Main Workspace") (part "LED-GREEN-AK-2"))
    )
    (comp (ref "DS2")
      (value "SMLLX0603GWTR")
      (footprint "LUMX-SML-LX0603_V")
      (description "LED GREEN DIFFUSED SMD")
      (libsource (lib "Main Workspace") (part "LED-GREEN-AK-2"))
    )
    (comp (ref "J2")
      (value "5-1814832-1")
      (footprint "TECO-5-1814832-1_V")
      (fields (field (name "MANUFACTURER") "TE Connectivity"))
      (libsource (lib "Altium Content Vault") (part "CN-S-4F-RF5"))
    )
    (comp (ref "L5")
      (value "74279279")
      (footprint "SMD-0402")
      (description "SMD EMI Suppression Ferrite Bead WE-CBF, Z = 600 Ohm")
      (libsource (lib "Altium Content Vault") (part "PAS-IND-INDUCTOR-2"))
    )
    (comp (ref "Q1")
      (value "AO3401A")
      (footprint "AO-SOT-23-3L_V")
      (description "P-Channel MOSFET, 30 V, 4 A, -55 to 150 degC, 3-Pin SOT-23-3L, RoHS, Tape and Reel")
      (fields (field (name "MANUFACTURER") "Alpha and Omega"))
      (libsource (lib "Altium Content Vault") (part "PEMOS-GSD-3"))
    )
    (comp (ref "Q2")
      (value "2N7002-7-F")
      (footprint "FP-SOT23-MFG")
      (description "MOSFET N-CH 60V 115MA SOT23-3")
      (fields (field (name "VOLTAGE") "60V"))
      (libsource (lib "Altium Content Vault") (part "3b9c635fedb024a5347a57b145af9cc"))
    )
    (comp (ref "R32")
      (value "100R")
      (footprint "RESC1005X40X25NL05T05")
      (fields
        (field (name "MANUFACTURER") "Basic Passives")
        (field (name "TOLERANCE") "1%")
        (field (name "PARTNUMBER") "ERJ-2RKF1000X")
      )
      (libsource (lib "Altium Content Vault") (part "RES-2"))
    )
    (comp (ref "R34")
      (value "1K")
      (footprint "RESC1005X40X25NL05T10")
      (description "CRCW04021K00FKEDHP")
      (fields (field (name "MANUFACTURER") "Vishay Dale"))
      (libsource (lib "Altium Content Vault") (part "RES"))
    )
    (comp (ref "R35")
      (value "1K")
      (footprint "RESC1005X40X25NL05T10")
      (description "CRCW04021K00FKEDHP")
      (fields (field (name "MANUFACTURER") "Vishay Dale"))
      (libsource (lib "Altium Content Vault") (part "RES"))
    )
    (comp (ref "R36")
      (value "1K")
      (footprint "RESC1005X40X25NL05T10")
      (description "CRCW04021K00FKEDHP")
      (fields (field (name "MANUFACTURER") "Vishay Dale"))
      (libsource (lib "Altium Content Vault") (part "RES"))
    )
    (comp (ref "R37")
      (value "1K")
      (footprint "RESC1005X40X25NL05T10")
      (description "CRCW04021K00FKEDHP")
      (fields (field (name "MANUFACTURER") "Vishay Dale"))
      (libsource (lib "Altium Content Vault") (part "RES"))
    )
    (comp (ref "R38")
      (value "1K")
      (footprint "RESC1005X40X25NL05T10")
      (description "CRCW04021K00FKEDHP")
      (fields (field (name "MANUFACTURER") "Vishay Dale"))
      (libsource (lib "Altium Content Vault") (part "RES"))
    )
    (comp (ref "R39")
      (value "1K")
      (footprint "RESC1005X40X25NL05T10")
      (description "CRCW04021K00FKEDHP")
      (fields (field (name "MANUFACTURER") "Vishay Dale"))
      (libsource (lib "Altium Content Vault") (part "RES"))
    )
    (comp (ref "R40")
      (value "3.3K")
      (footprint "RESC1005X40X25NL05T10")
      (description "CRCW04023K30FKEDHP")
      (fields (field (name "MANUFACTURER") "Vishay Dale"))
      (libsource (lib "Altium Content Vault") (part "RES"))
    )
    (comp (ref "R41")
      (value "1K")
      (footprint "RESC1005X40X25NL05T10")
      (description "CRCW04021K00FKEDHP")
      (fields (field (name "MANUFACTURER") "Vishay Dale"))
      (libsource (lib "Altium Content Vault") (part "RES"))
    )
    (comp (ref "R42")
      (value "3.3K")
      (footprint "RESC1005X40X25NL05T10")
      (description "CRCW04023K30FKEDHP")
      (fields (field (name "MANUFACTURER") "Vishay Dale"))
      (libsource (lib "Altium Content Vault") (part "RES"))
    )
    (comp (ref "R43")
      (value "1K")
      (footprint "RESC1005X40X25NL05T10")
      (description "CRCW04021K00FKEDHP")
      (fields (field (name "MANUFACTURER") "Vishay Dale"))
      (libsource (lib "Altium Content Vault") (part "RES"))
    )
    (comp (ref "R44")
      (value "1K")
      (footprint "RESC1005X40X25NL05T10")
      (description "CRCW04021K00FKEDHP")
      (fields (field (name "MANUFACTURER") "Vishay Dale"))
      (libsource (lib "Altium Content Vault") (part "RES"))
    )
    (comp (ref "R45")
      (value "1K")
      (footprint "RESC1005X40X25NL05T10")
      (description "CRCW04021K00FKEDHP")
      (fields (field (name "MANUFACTURER") "Vishay Dale"))
      (libsource (lib "Altium Content Vault") (part "RES"))
    )
    (comp (ref "R46")
      (value "2.4K")
      (footprint "RESC1005X40X25NL05T05")
      (description "CRCW04022K40FKED")
      (fields (field (name "MANUFACTURER") "Vishay Dale"))
      (libsource (lib "Altium Content Vault") (part "RES"))
    )
    (comp (ref "R48")
      (value "0R")
      (footprint "RESC1005X40X25NL05T10")
      (description "CRCW04020000Z0EDHP")
      (fields (field (name "MANUFACTURER") "Vishay Dale"))
      (libsource (lib "Altium Content Vault") (part "RES"))
    )
    (comp (ref "R49")
      (value "0R")
      (footprint "RESC1005X40X25NL05T10")
      (description "CRCW04020000Z0EDHP")
      (fields (field (name "MANUFACTURER") "Vishay Dale"))
      (libsource (lib "Altium Content Vault") (part "RES"))
    )
    (comp (ref "R50")
      (value "0R")
      (footprint "RESC1005X40X25NL05T10")
      (description "CRCW04020000Z0EDHP")
      (fields (field (name "MANUFACTURER") "Vishay Dale"))
      (libsource (lib "Altium Content Vault") (part "RES"))
    )
    (comp (ref "R51")
      (value "0R")
      (footprint "RESC1005X40X25NL05T10")
      (description "CRCW04020000Z0EDHP")
      (fields (field (name "MANUFACTURER") "Vishay Dale"))
      (libsource (lib "Altium Content Vault") (part "RES"))
    )
    (comp (ref "SW3")
      (value "B3S-1000P")
      (footprint "FP-B3S-1000P-MFG")
      (description "SWITCH TACTILE SPST-NO 0.05A 24V")
      (libsource (lib "Altium Content Vault") (part "b8895f3f4cefb76e1819d2863dba89b"))
    )
    (comp (ref "SW4")
      (value "B3S-1000P")
      (footprint "FP-B3S-1000P-MFG")
      (description "SWITCH TACTILE SPST-NO 0.05A 24V")
      (libsource (lib "Altium Content Vault") (part "b8895f3f4cefb76e1819d2863dba89b"))
    )
    (comp (ref "SW5")
      (value "A6S-3101-H")
      (footprint "FP-A6S-3101-H-MFG")
      (description "SWITCH SLIDE DIP SPST 25MA 24V")
      (libsource (lib "Altium Content Vault") (part "3494dd441064fb229d3d9931c8c67f4"))
    )
    (comp (ref "TP16")
      (value "Test Point Round 0.5mm")
      (footprint "Test Point Round 0.5mm-Footprint-1")
      (description "SMD Test point 0.5mm Diameter")
      (libsource (lib "Main Workspace") (part "TESTPOINT_ORANGE"))
    )
    (comp (ref "TP17")
      (value "Test Point Round 0.5mm")
      (footprint "Test Point Round 0.5mm-Footprint-1")
      (description "SMD Test point 0.5mm Diameter")
      (libsource (lib "Main Workspace") (part "TESTPOINT_ORANGE"))
    )
    (comp (ref "TP18")
      (value "Test Point Round 0.5mm")
      (footprint "Test Point Round 0.5mm-Footprint-1")
      (description "SMD Test point 0.5mm Diameter")
      (libsource (lib "Main Workspace") (part "TESTPOINT_ORANGE"))
    )
    (comp (ref "TP19")
      (value "Test Point Round 0.5mm")
      (footprint "Test Point Round 0.5mm-Footprint-1")
      (description "SMD Test point 0.5mm Diameter")
      (libsource (lib "Main Workspace") (part "TESTPOINT_ORANGE"))
    )
    (comp (ref "TP20")
      (value "Test Point Round 0.5mm")
      (footprint "Test Point Round 0.5mm-Footprint-1")
      (description "SMD Test point 0.5mm Diameter")
      (libsource (lib "Main Workspace") (part "TESTPOINT_ORANGE"))
    )
    (comp (ref "TP21")
      (value "Test Point Round 0.5mm")
      (footprint "Test Point Round 0.5mm-Footprint-1")
      (description "SMD Test point 0.5mm Diameter")
      (libsource (lib "Main Workspace") (part "TESTPOINT_ORANGE"))
    )
    (comp (ref "TP22")
      (value "Test Point Round 0.5mm")
      (footprint "Test Point Round 0.5mm-Footprint-1")
      (description "SMD Test point 0.5mm Diameter")
      (libsource (lib "Main Workspace") (part "TESTPOINT_ORANGE"))
    )
    (comp (ref "TP23")
      (value "Test Point Round 0.5mm")
      (footprint "Test Point Round 0.5mm-Footprint-1")
      (description "SMD Test point 0.5mm Diameter")
      (libsource (lib "Main Workspace") (part "TESTPOINT_ORANGE"))
    )
    (comp (ref "TP24")
      (value "Test Point Round 0.5mm")
      (footprint "Test Point Round 0.5mm-Footprint-1")
      (description "SMD Test point 0.5mm Diameter")
      (libsource (lib "Main Workspace") (part "TESTPOINT_ORANGE"))
    )
    (comp (ref "TP25")
      (value "Test Point Round 0.5mm")
      (footprint "Test Point Round 0.5mm-Footprint-1")
      (description "SMD Test point 0.5mm Diameter")
      (libsource (lib "Main Workspace") (part "TESTPOINT_ORANGE"))
    )
    (comp (ref "TP26")
      (value "Test Point Round 0.5mm")
      (footprint "Test Point Round 0.5mm-Footprint-1")
      (description "SMD Test point 0.5mm Diameter")
      (libsource (lib "Main Workspace") (part "TESTPOINT_ORANGE"))
    )
    (comp (ref "TP27")
      (value "Test Point Round 0.5mm")
      (footprint "Test Point Round 0.5mm-Footprint-1")
      (description "SMD Test point 0.5mm Diameter")
      (libsource (lib "Main Workspace") (part "TESTPOINT_ORANGE"))
    )
    (comp (ref "TP28")
      (value "Test Point Round 0.5mm")
      (footprint "Test Point Round 0.5mm-Footprint-1")
      (description "SMD Test point 0.5mm Diameter")
      (libsource (lib "Main Workspace") (part "TESTPOINT_ORANGE"))
    )
    (comp (ref "TP29")
      (value "Test Point Round 0.5mm")
      (footprint "Test Point Round 0.5mm-Footprint-1")
      (description "SMD Test point 0.5mm Diameter")
      (libsource (lib "Main Workspace") (part "TESTPOINT_ORANGE"))
    )
    (comp (ref "TP30")
      (value "Test Point Round 0.5mm")
      (footprint "Test Point Round 0.5mm-Footprint-1")
      (description "SMD Test point 0.5mm Diameter")
      (libsource (lib "Main Workspace") (part "TESTPOINT_ORANGE"))
    )
    (comp (ref "TP31")
      (value "Test Point Round 0.5mm")
      (footprint "Test Point Round 0.5mm-Footprint-1")
      (description "SMD Test point 0.5mm Diameter")
      (libsource (lib "Main Workspace") (part "TESTPOINT_ORANGE"))
    )
    (comp (ref "TP32")
      (value "Test Point Round 0.5mm")
      (footprint "Test Point Round 0.5mm-Footprint-1")
      (description "SMD Test point 0.5mm Diameter")
      (libsource (lib "Main Workspace") (part "TESTPOINT_ORANGE"))
    )
    (comp (ref "TP33")
      (value "Test Point Round 0.5mm")
      (footprint "Test Point Round 0.5mm-Footprint-1")
      (description "SMD Test point 0.5mm Diameter")
      (libsource (lib "Main Workspace") (part "TESTPOINT_ORANGE"))
    )
    (comp (ref "TP34")
      (value "Test Point Round 0.5mm")
      (footprint "Test Point Round 0.5mm-Footprint-1")
      (description "SMD Test point 0.5mm Diameter")
      (libsource (lib "Main Workspace") (part "TESTPOINT_ORANGE"))
    )
    (comp (ref "TP35")
      (value "Test Point Round 0.5mm")
      (footprint "Test Point Round 0.5mm-Footprint-1")
      (description "SMD Test point 0.5mm Diameter")
      (libsource (lib "Main Workspace") (part "TESTPOINT_ORANGE"))
    )
    (comp (ref "TP36")
      (value "Test Point Round 0.5mm")
      (footprint "Test Point Round 0.5mm-Footprint-1")
      (description "SMD Test point 0.5mm Diameter")
      (libsource (lib "Main Workspace") (part "TESTPOINT_ORANGE"))
    )
    (comp (ref "TP37")
      (value "Test Point Round 0.5mm")
      (footprint "Test Point Round 0.5mm-Footprint-1")
      (description "SMD Test point 0.5mm Diameter")
      (libsource (lib "Main Workspace") (part "TESTPOINT_ORANGE"))
    )
    (comp (ref "TP38")
      (value "Test Point Round 0.5mm")
      (footprint "Test Point Round 0.5mm-Footprint-1")
      (description "SMD Test point 0.5mm Diameter")
      (libsource (lib "Main Workspace") (part "TESTPOINT_ORANGE"))
    )
    (comp (ref "TP39")
      (value "Test Point Round 0.5mm")
      (footprint "Test Point Round 0.5mm-Footprint-1")
      (description "SMD Test point 0.5mm Diameter")
      (libsource (lib "Main Workspace") (part "TESTPOINT_ORANGE"))
    )
    (comp (ref "TP40")
      (value "Test Point Round 0.5mm")
      (footprint "Test Point Round 0.5mm-Footprint-1")
      (description "SMD Test point 0.5mm Diameter")
      (libsource (lib "Main Workspace") (part "TESTPOINT_ORANGE"))
    )
    (comp (ref "TP41")
      (value "Test Point Round 0.5mm")
      (footprint "Test Point Round 0.5mm-Footprint-1")
      (description "SMD Test point 0.5mm Diameter")
      (libsource (lib "Main Workspace") (part "TESTPOINT_ORANGE"))
    )
    (comp (ref "TP42")
      (value "Test Point Round 0.5mm")
      (footprint "Test Point Round 0.5mm-Footprint-1")
      (description "SMD Test point 0.5mm Diameter")
      (libsource (lib "Main Workspace") (part "TESTPOINT_ORANGE"))
    )
    (comp (ref "TP43")
      (value "Test Point Round 0.5mm")
      (footprint "Test Point Round 0.5mm-Footprint-1")
      (description "SMD Test point 0.5mm Diameter")
      (libsource (lib "Main Workspace") (part "TESTPOINT_ORANGE"))
    )
    (comp (ref "TP44")
      (value "Test Point Round 0.5mm")
      (footprint "Test Point Round 0.5mm-Footprint-1")
      (description "SMD Test point 0.5mm Diameter")
      (libsource (lib "Main Workspace") (part "TESTPOINT_ORANGE"))
    )
    (comp (ref "TP45")
      (value "Test Point Round 0.5mm")
      (footprint "Test Point Round 0.5mm-Footprint-1")
      (description "SMD Test point 0.5mm Diameter")
      (libsource (lib "Main Workspace") (part "TESTPOINT_ORANGE"))
    )
    (comp (ref "TP46")
      (value "Test Point Round 0.5mm")
      (footprint "Test Point Round 0.5mm-Footprint-1")
      (description "SMD Test point 0.5mm Diameter")
      (libsource (lib "Main Workspace") (part "TESTPOINT_ORANGE"))
    )
    (comp (ref "TP47")
      (value "Test Point Round 0.5mm")
      (footprint "Test Point Round 0.5mm-Footprint-1")
      (description "SMD Test point 0.5mm Diameter")
      (libsource (lib "Main Workspace") (part "TESTPOINT_ORANGE"))
    )
    (comp (ref "TP48")
      (value "Test Point Round 0.5mm")
      (footprint "Test Point Round 0.5mm-Footprint-1")
      (description "SMD Test point 0.5mm Diameter")
      (libsource (lib "Main Workspace") (part "TESTPOINT_ORANGE"))
    )
    (comp (ref "TP49")
      (value "Test Point Round 0.5mm")
      (footprint "Test Point Round 0.5mm-Footprint-1")
      (description "SMD Test point 0.5mm Diameter")
      (libsource (lib "Main Workspace") (part "TESTPOINT_ORANGE"))
    )
    (comp (ref "TP50")
      (value "Test Point Round 0.5mm")
      (footprint "Test Point Round 0.5mm-Footprint-1")
      (description "SMD Test point 0.5mm Diameter")
      (libsource (lib "Main Workspace") (part "TESTPOINT_ORANGE"))
    )
    (comp (ref "TP51")
      (value "Test Point Round 0.5mm")
      (footprint "Test Point Round 0.5mm-Footprint-1")
      (description "SMD Test point 0.5mm Diameter")
      (libsource (lib "Main Workspace") (part "TESTPOINT_ORANGE"))
    )
    (comp (ref "TP52")
      (value "Test Point Round 0.5mm")
      (footprint "Test Point Round 0.5mm-Footprint-1")
      (description "SMD Test point 0.5mm Diameter")
      (libsource (lib "Main Workspace") (part "TESTPOINT_ORANGE"))
    )
    (comp (ref "TP53")
      (value "Test Point Round 0.5mm")
      (footprint "Test Point Round 0.5mm-Footprint-1")
      (description "SMD Test point 0.5mm Diameter")
      (libsource (lib "Main Workspace") (part "TESTPOINT_ORANGE"))
    )
    (comp (ref "TP54")
      (value "Test Point Round 0.5mm")
      (footprint "Test Point Round 0.5mm-Footprint-1")
      (description "SMD Test point 0.5mm Diameter")
      (libsource (lib "Main Workspace") (part "TESTPOINT_ORANGE"))
    )
    (comp (ref "TP55")
      (value "Test Point Round 0.5mm")
      (footprint "Test Point Round 0.5mm-Footprint-1")
      (description "SMD Test point 0.5mm Diameter")
      (libsource (lib "Main Workspace") (part "TESTPOINT_ORANGE"))
    )
    (comp (ref "TP56")
      (value "Test Point Round 0.5mm")
      (footprint "Test Point Round 0.5mm-Footprint-1")
      (description "SMD Test point 0.5mm Diameter")
      (libsource (lib "Main Workspace") (part "TESTPOINT_ORANGE"))
    )
    (comp (ref "TP57")
      (value "Test Point Round 0.5mm")
      (footprint "Test Point Round 0.5mm-Footprint-1")
      (description "SMD Test point 0.5mm Diameter")
      (libsource (lib "Main Workspace") (part "TESTPOINT_ORANGE"))
    )
    (comp (ref "TP58")
      (value "Test Point Round 0.5mm")
      (footprint "Test Point Round 0.5mm-Footprint-1")
      (description "SMD Test point 0.5mm Diameter")
      (libsource (lib "Main Workspace") (part "TESTPOINT_ORANGE"))
    )
    (comp (ref "TP59")
      (value "Test Point Round 0.5mm")
      (footprint "Test Point Round 0.5mm-Footprint-1")
      (description "SMD Test point 0.5mm Diameter")
      (libsource (lib "Main Workspace") (part "TESTPOINT_ORANGE"))
    )
    (comp (ref "TP60")
      (value "Test Point Round 0.5mm")
      (footprint "Test Point Round 0.5mm-Footprint-1")
      (description "SMD Test point 0.5mm Diameter")
      (libsource (lib "Main Workspace") (part "TESTPOINT_ORANGE"))
    )
    (comp (ref "TP61")
      (value "Test Point Round 0.5mm")
      (footprint "Test Point Round 0.5mm-Footprint-1")
      (description "SMD Test point 0.5mm Diameter")
      (libsource (lib "Main Workspace") (part "TESTPOINT_ORANGE"))
    )
    (comp (ref "TP62")
      (value "Test Point Round 0.5mm")
      (footprint "Test Point Round 0.5mm-Footprint-1")
      (description "SMD Test point 0.5mm Diameter")
      (libsource (lib "Main Workspace") (part "TESTPOINT_ORANGE"))
    )
    (comp (ref "TP63")
      (value "Test Point Round 0.5mm")
      (footprint "Test Point Round 0.5mm-Footprint-1")
      (description "SMD Test point 0.5mm Diameter")
      (libsource (lib "Main Workspace") (part "TESTPOINT_ORANGE"))
    )
    (comp (ref "TP64")
      (value "Test Point Round 0.5mm")
      (footprint "Test Point Round 0.5mm-Footprint-1")
      (description "SMD Test point 0.5mm Diameter")
      (libsource (lib "Main Workspace") (part "TESTPOINT_ORANGE"))
    )
    (comp (ref "TP65")
      (value "Test Point Round 0.5mm")
      (footprint "Test Point Round 0.5mm-Footprint-1")
      (description "SMD Test point 0.5mm Diameter")
      (libsource (lib "Main Workspace") (part "TESTPOINT_ORANGE"))
    )
    (comp (ref "TP66")
      (value "Test Point Round 0.5mm")
      (footprint "Test Point Round 0.5mm-Footprint-1")
      (description "SMD Test point 0.5mm Diameter")
      (libsource (lib "Main Workspace") (part "TESTPOINT_ORANGE"))
    )
    (comp (ref "TP67")
      (value "Test Point Round 0.5mm")
      (footprint "Test Point Round 0.5mm-Footprint-1")
      (description "SMD Test point 0.5mm Diameter")
      (libsource (lib "Main Workspace") (part "TESTPOINT_ORANGE"))
    )
    (comp (ref "TP68")
      (value "Test Point Round 0.5mm")
      (footprint "Test Point Round 0.5mm-Footprint-1")
      (description "SMD Test point 0.5mm Diameter")
      (libsource (lib "Main Workspace") (part "TESTPOINT_ORANGE"))
    )
    (comp (ref "TP69")
      (value "Test Point Round 0.5mm")
      (footprint "Test Point Round 0.5mm-Footprint-1")
      (description "SMD Test point 0.5mm Diameter")
      (libsource (lib "Main Workspace") (part "TESTPOINT_ORANGE"))
    )
    (comp (ref "TP70")
      (value "Test Point Round 0.5mm")
      (footprint "Test Point Round 0.5mm-Footprint-1")
      (description "SMD Test point 0.5mm Diameter")
      (libsource (lib "Main Workspace") (part "TESTPOINT_ORANGE"))
    )
    (comp (ref "TP71")
      (value "Test Point Round 0.5mm")
      (footprint "Test Point Round 0.5mm-Footprint-1")
      (description "SMD Test point 0.5mm Diameter")
      (libsource (lib "Main Workspace") (part "TESTPOINT_ORANGE"))
    )
    (comp (ref "TP72")
      (value "Test Point Round 0.5mm")
      (footprint "Test Point Round 0.5mm-Footprint-1")
      (description "SMD Test point 0.5mm Diameter")
      (libsource (lib "Main Workspace") (part "TESTPOINT_ORANGE"))
    )
    (comp (ref "TP73")
      (value "Test Point Round 0.5mm")
      (footprint "Test Point Round 0.5mm-Footprint-1")
      (description "SMD Test point 0.5mm Diameter")
      (libsource (lib "Main Workspace") (part "TESTPOINT_ORANGE"))
    )
    (comp (ref "TP74")
      (value "Test Point Round 0.5mm")
      (footprint "Test Point Round 0.5mm-Footprint-1")
      (description "SMD Test point 0.5mm Diameter")
      (libsource (lib "Main Workspace") (part "TESTPOINT_ORANGE"))
    )
    (comp (ref "TP75")
      (value "Test Point Round 0.5mm")
      (footprint "Test Point Round 0.5mm-Footprint-1")
      (description "SMD Test point 0.5mm Diameter")
      (libsource (lib "Main Workspace") (part "TESTPOINT_ORANGE"))
    )
    (comp (ref "TP76")
      (value "Test Point Round 0.5mm")
      (footprint "Test Point Round 0.5mm-Footprint-1")
      (description "SMD Test point 0.5mm Diameter")
      (libsource (lib "Main Workspace") (part "TESTPOINT_ORANGE"))
    )
    (comp (ref "TP77")
      (value "Test Point Round 0.5mm")
      (footprint "Test Point Round 0.5mm-Footprint-1")
      (description "SMD Test point 0.5mm Diameter")
      (libsource (lib "Main Workspace") (part "TESTPOINT_ORANGE"))
    )
    (comp (ref "TP78")
      (value "Test Point Round 0.5mm")
      (footprint "Test Point Round 0.5mm-Footprint-1")
      (description "SMD Test point 0.5mm Diameter")
      (libsource (lib "Main Workspace") (part "TESTPOINT_ORANGE"))
    )
    (comp (ref "TP79")
      (value "Test Point Round 0.5mm")
      (footprint "Test Point Round 0.5mm-Footprint-1")
      (description "SMD Test point 0.5mm Diameter")
      (libsource (lib "Main Workspace") (part "TESTPOINT_ORANGE"))
    )
    (comp (ref "TP80")
      (value "Test Point Round 0.5mm")
      (footprint "Test Point Round 0.5mm-Footprint-1")
      (description "SMD Test point 0.5mm Diameter")
      (libsource (lib "Main Workspace") (part "TESTPOINT_ORANGE"))
    )
    (comp (ref "TP81")
      (value "Test Point Round 0.5mm")
      (footprint "Test Point Round 0.5mm-Footprint-1")
      (description "SMD Test point 0.5mm Diameter")
      (libsource (lib "Main Workspace") (part "TESTPOINT_ORANGE"))
    )
    (comp (ref "TP82")
      (value "Test Point Round 0.5mm")
      (footprint "Test Point Round 0.5mm-Footprint-1")
      (description "SMD Test point 0.5mm Diameter")
      (libsource (lib "Main Workspace") (part "TESTPOINT_ORANGE"))
    )
    (comp (ref "TP83")
      (value "Test Point Round 0.5mm")
      (footprint "Test Point Round 0.5mm-Footprint-1")
      (description "SMD Test point 0.5mm Diameter")
      (libsource (lib "Main Workspace") (part "TESTPOINT_ORANGE"))
    )
    (comp (ref "TP84")
      (value "Test Point Round 0.5mm")
      (footprint "Test Point Round 0.5mm-Footprint-1")
      (description "SMD Test point 0.5mm Diameter")
      (libsource (lib "Main Workspace") (part "TESTPOINT_ORANGE"))
    )
    (comp (ref "TP85")
      (value "Test Point Round 0.5mm")
      (footprint "Test Point Round 0.5mm-Footprint-1")
      (description "SMD Test point 0.5mm Diameter")
      (libsource (lib "Main Workspace") (part "TESTPOINT_ORANGE"))
    )
    (comp (ref "TP86")
      (value "Test Point Round 0.5mm")
      (footprint "Test Point Round 0.5mm-Footprint-1")
      (description "SMD Test point 0.5mm Diameter")
      (libsource (lib "Main Workspace") (part "TESTPOINT_ORANGE"))
    )
    (comp (ref "TP87")
      (value "Test Point Round 0.5mm")
      (footprint "Test Point Round 0.5mm-Footprint-1")
      (description "SMD Test point 0.5mm Diameter")
      (libsource (lib "Main Workspace") (part "TESTPOINT_ORANGE"))
    )
    (comp (ref "TP88")
      (value "Test Point Round 0.5mm")
      (footprint "Test Point Round 0.5mm-Footprint-1")
      (description "SMD Test point 0.5mm Diameter")
      (libsource (lib "Main Workspace") (part "TESTPOINT_ORANGE"))
    )
    (comp (ref "TP89")
      (value "Test Point Round 0.5mm")
      (footprint "Test Point Round 0.5mm-Footprint-1")
      (description "SMD Test point 0.5mm Diameter")
      (libsource (lib "Main Workspace") (part "TESTPOINT_ORANGE"))
    )
    (comp (ref "TP90")
      (value "Test Point Round 0.5mm")
      (footprint "Test Point Round 0.5mm-Footprint-1")
      (description "SMD Test point 0.5mm Diameter")
      (libsource (lib "Main Workspace") (part "TESTPOINT_ORANGE"))
    )
    (comp (ref "TP91")
      (value "Test Point Round 0.5mm")
      (footprint "Test Point Round 0.5mm-Footprint-1")
      (description "SMD Test point 0.5mm Diameter")
      (libsource (lib "Main Workspace") (part "TESTPOINT_ORANGE"))
    )
    (comp (ref "TP92")
      (value "Test Point Round 0.5mm")
      (footprint "Test Point Round 0.5mm-Footprint-1")
      (description "SMD Test point 0.5mm Diameter")
      (libsource (lib "Main Workspace") (part "TESTPOINT_ORANGE"))
    )
    (comp (ref "TP93")
      (value "Test Point Round 0.5mm")
      (footprint "Test Point Round 0.5mm-Footprint-1")
      (description "SMD Test point 0.5mm Diameter")
      (libsource (lib "Main Workspace") (part "TESTPOINT_ORANGE"))
    )
    (comp (ref "TP94")
      (value "Test Point Round 0.5mm")
      (footprint "Test Point Round 0.5mm-Footprint-1")
      (description "SMD Test point 0.5mm Diameter")
      (libsource (lib "Main Workspace") (part "TESTPOINT_ORANGE"))
    )
    (comp (ref "TP95")
      (value "Test Point Round 0.5mm")
      (footprint "Test Point Round 0.5mm-Footprint-1")
      (description "SMD Test point 0.5mm Diameter")
      (libsource (lib "Main Workspace") (part "TESTPOINT_ORANGE"))
    )
    (comp (ref "TP96")
      (value "Test Point Round 0.5mm")
      (footprint "Test Point Round 0.5mm-Footprint-1")
      (description "SMD Test point 0.5mm Diameter")
      (libsource (lib "Main Workspace") (part "TESTPOINT_ORANGE"))
    )
    (comp (ref "TP97")
      (value "Test Point Round 0.5mm")
      (footprint "Test Point Round 0.5mm-Footprint-1")
      (description "SMD Test point 0.5mm Diameter")
      (libsource (lib "Main Workspace") (part "TESTPOINT_ORANGE"))
    )
    (comp (ref "TP98")
      (value "Test Point Round 0.5mm")
      (footprint "Test Point Round 0.5mm-Footprint-1")
      (description "SMD Test point 0.5mm Diameter")
      (libsource (lib "Main Workspace") (part "TESTPOINT_ORANGE"))
    )
    (comp (ref "TP99")
      (value "Test Point Round 0.5mm")
      (footprint "Test Point Round 0.5mm-Footprint-1")
      (description "SMD Test point 0.5mm Diameter")
      (libsource (lib "Main Workspace") (part "TESTPOINT_ORANGE"))
    )
    (comp (ref "TP100")
      (value "Test Point Round 0.5mm")
      (footprint "Test Point Round 0.5mm-Footprint-1")
      (description "SMD Test point 0.5mm Diameter")
      (libsource (lib "Main Workspace") (part "TESTPOINT_ORANGE"))
    )
    (comp (ref "TP101")
      (value "Test Point Round 0.5mm")
      (footprint "Test Point Round 0.5mm-Footprint-1")
      (description "SMD Test point 0.5mm Diameter")
      (libsource (lib "Main Workspace") (part "TESTPOINT_ORANGE"))
    )
    (comp (ref "TP102")
      (value "Test Point Round 0.5mm")
      (footprint "Test Point Round 0.5mm-Footprint-1")
      (description "SMD Test point 0.5mm Diameter")
      (libsource (lib "Main Workspace") (part "TESTPOINT_ORANGE"))
    )
    (comp (ref "TP103")
      (value "Test Point Round 0.5mm")
      (footprint "Test Point Round 0.5mm-Footprint-1")
      (description "SMD Test point 0.5mm Diameter")
      (libsource (lib "Main Workspace") (part "TESTPOINT_ORANGE"))
    )
    (comp (ref "TP104")
      (value "Test Point Round 0.5mm")
      (footprint "Test Point Round 0.5mm-Footprint-1")
      (description "SMD Test point 0.5mm Diameter")
      (libsource (lib "Main Workspace") (part "TESTPOINT_ORANGE"))
    )
    (comp (ref "TP105")
      (value "Test Point Round 0.5mm")
      (footprint "Test Point Round 0.5mm-Footprint-1")
      (description "SMD Test point 0.5mm Diameter")
      (libsource (lib "Main Workspace") (part "TESTPOINT_ORANGE"))
    )
    (comp (ref "TP106")
      (value "Test Point Round 0.5mm")
      (footprint "Test Point Round 0.5mm-Footprint-1")
      (description "SMD Test point 0.5mm Diameter")
      (libsource (lib "Main Workspace") (part "TESTPOINT_ORANGE"))
    )
    (comp (ref "TP107")
      (value "Test Point Round 0.5mm")
      (footprint "Test Point Round 0.5mm-Footprint-1")
      (description "SMD Test point 0.5mm Diameter")
      (libsource (lib "Main Workspace") (part "TESTPOINT_ORANGE"))
    )
    (comp (ref "TP108")
      (value "Test Point Round 0.5mm")
      (footprint "Test Point Round 0.5mm-Footprint-1")
      (description "SMD Test point 0.5mm Diameter")
      (libsource (lib "Main Workspace") (part "TESTPOINT_ORANGE"))
    )
    (comp (ref "TP109")
      (value "Test Point Round 0.5mm")
      (footprint "Test Point Round 0.5mm-Footprint-1")
      (description "SMD Test point 0.5mm Diameter")
      (libsource (lib "Main Workspace") (part "TESTPOINT_ORANGE"))
    )
    (comp (ref "TP110")
      (value "Test Point Round 0.5mm")
      (footprint "Test Point Round 0.5mm-Footprint-1")
      (description "SMD Test point 0.5mm Diameter")
      (libsource (lib "Main Workspace") (part "TESTPOINT_ORANGE"))
    )
    (comp (ref "TP111")
      (value "Test Point Round 0.5mm")
      (footprint "Test Point Round 0.5mm-Footprint-1")
      (description "SMD Test point 0.5mm Diameter")
      (libsource (lib "Main Workspace") (part "TESTPOINT_ORANGE"))
    )
    (comp (ref "TP112")
      (value "Test Point Round 0.5mm")
      (footprint "Test Point Round 0.5mm-Footprint-1")
      (description "SMD Test point 0.5mm Diameter")
      (libsource (lib "Main Workspace") (part "TESTPOINT_ORANGE"))
    )
    (comp (ref "TP113")
      (value "Test Point Round 0.5mm")
      (footprint "Test Point Round 0.5mm-Footprint-1")
      (description "SMD Test point 0.5mm Diameter")
      (libsource (lib "Main Workspace") (part "TESTPOINT_ORANGE"))
    )
    (comp (ref "TP114")
      (value "Test Point Round 0.5mm")
      (footprint "Test Point Round 0.5mm-Footprint-1")
      (description "SMD Test point 0.5mm Diameter")
      (libsource (lib "Main Workspace") (part "TESTPOINT_ORANGE"))
    )
    (comp (ref "TP115")
      (value "Test Point Round 0.5mm")
      (footprint "Test Point Round 0.5mm-Footprint-1")
      (description "SMD Test point 0.5mm Diameter")
      (libsource (lib "Main Workspace") (part "TESTPOINT_ORANGE"))
    )
    (comp (ref "U9")
      (value "XC7A35T-1FGG484C")
      (footprint "FGG484")
      (description "Artix-7 FPGA, 250 User I/Os, 4 GTP, 484-Ball BGA, Speed Grade 1, Commercial Grade, Pb-Free")
      (fields (field (name "MANUFACTURER") "Xilinx"))
      (libsource (lib "Altium Content Vault") (part "XLNX-XC7A35T-FGG484"))
    )
    (comp (ref "U10")
      (value "TC1047AVNBTR")
      (footprint "SOT-23-NB3_L")
      (description "Precision Temperature-to-Voltage Converter, 3-Pin SOT-23, Extended Temperature, Tape and Reel")
      (libsource (lib "Altium Content Vault") (part "CON-TVC-TC1046-3"))
    )
    (comp (ref "U11")
      (value "NX33D5001Q")
      (footprint "SOTFL125P185X90-6N")
      (description "Xtal Osc Xo 135.0000MHZ Lvds SMD")
      (libsource (lib "Main Workspace") (part "NX33D5001Q"))
    )
    (comp (ref "U12")
      (value "REF3012AIDBZT")
      (footprint "DBZ0003A_L")
      (fields (field (name "MANUFACTURER") "Texas Instruments"))
      (libsource (lib "Altium Content Vault") (part "TI-REF3012DBZ3"))
    )
    (comp (ref "U13")
      (value "IS25LP128F-JBLE")
      (footprint "SOIC127P790X216-8N")
      (description "Flash, Multi I/O SPI, QPI, DTR, 2.3-3.6V, -40 to 125°C, 8-pin SOIC 208mil, RoHS")
      (libsource (lib "Main Workspace") (part "IS25LP128F-JBLE"))
    )
    (comp (ref "X1")
      (value "O53100000153033")
      (footprint "DFN254P500X120-4N")
      (description "Single Ended CMOS Oscillator 3.3V 100Mhz")
      (libsource (lib "Main Workspace") (part "O53100000153033"))
    )
  )
  (nets
    (net (code "1") (name "+1V0") (class "Default")
      (node (ref "C106") (pin "2") (pinfunction "2_2") (pintype "passive"))
      (node (ref "C107") (pin "2") (pinfunction "2_2") (pintype "passive"))
      (node (ref "C108") (pin "2") (pinfunction "2_2") (pintype "passive"))
      (node (ref "C109") (pin "2") (pinfunction "2_2") (pintype "passive"))
      (node (ref "C110") (pin "2") (pinfunction "2_2") (pintype "passive"))
      (node (ref "C111") (pin "2") (pinfunction "2_2") (pintype "passive"))
      (node (ref "C112") (pin "2") (pinfunction "2_2") (pintype "passive"))
      (node (ref "C113") (pin "2") (pinfunction "2_2") (pintype "passive"))
      (node (ref "C114") (pin "2") (pinfunction "2_2") (pintype "passive"))
      (node (ref "C121") (pin "2") (pinfunction "2_2") (pintype "passive"))
      (node (ref "C122") (pin "2") (pinfunction "2_2") (pintype "passive"))
      (node (ref "C123") (pin "2") (pinfunction "2_2") (pintype "passive"))
      (node (ref "C124") (pin "2") (pinfunction "2_2") (pintype "passive"))
      (node (ref "C125") (pin "2") (pinfunction "2_2") (pintype "passive"))
      (node (ref "C126") (pin "2") (pinfunction "2_2") (pintype "passive"))
      (node (ref "C127") (pin "2") (pinfunction "2_2") (pintype "passive"))
      (node (ref "C128") (pin "2") (pinfunction "2_2") (pintype "passive"))
      (node (ref "C129") (pin "2") (pinfunction "2_2") (pintype "passive"))
      (node (ref "C130") (pin "2") (pinfunction "2_2") (pintype "passive"))
      (node (ref "C131") (pin "2") (pinfunction "2_2") (pintype "passive"))
      (node (ref "C132") (pin "2") (pinfunction "2_2") (pintype "passive"))
      (node (ref "C133") (pin "2") (pinfunction "2_2") (pintype "passive"))
      (node (ref "C56") (pin "2") (pinfunction "2_2") (pintype "passive"))
      (node (ref "C57") (pin "2") (pinfunction "2_2") (pintype "passive"))
      (node (ref "C58") (pin "2") (pinfunction "2_2") (pintype "passive"))
      (node (ref "C59") (pin "2") (pinfunction "2_2") (pintype "passive"))
      (node (ref "C60") (pin "2") (pinfunction "2_2") (pintype "passive"))
      (node (ref "C61") (pin "2") (pinfunction "2_2") (pintype "passive"))
      (node (ref "C62") (pin "2") (pinfunction "2_2") (pintype "passive"))
      (node (ref "U9") (pin "D10") (pinfunction "MGTAVCC_D10") (pintype "power_in"))
      (node (ref "U9") (pin "D6") (pinfunction "MGTAVCC_D6") (pintype "power_in"))
      (node (ref "U9") (pin "E8") (pinfunction "MGTAVCC_E8") (pintype "power_in"))
      (node (ref "U9") (pin "F7") (pinfunction "MGTAVCC_F7") (pintype "power_in"))
      (node (ref "U9") (pin "F9") (pinfunction "MGTAVCC_F9") (pintype "power_in"))
      (node (ref "U9") (pin "H10") (pinfunction "VCCINT_H10") (pintype "power_in"))
      (node (ref "U9") (pin "H8") (pinfunction "VCCINT_H8") (pintype "power_in"))
      (node (ref "U9") (pin "J11") (pinfunction "VCCBRAM_J11") (pintype "power_in"))
      (node (ref "U9") (pin "J7") (pinfunction "VCCINT_J7") (pintype "power_in"))
      (node (ref "U9") (pin "J9") (pinfunction "VCCINT_J9") (pintype "power_in"))
      (node (ref "U9") (pin "K8") (pinfunction "VCCINT_K8") (pintype "power_in"))
      (node (ref "U9") (pin "L11") (pinfunction "VCCBRAM_L11") (pintype "power_in"))
      (node (ref "U9") (pin "L7") (pinfunction "VCCINT_L7") (pintype "power_in"))
      (node (ref "U9") (pin "M8") (pinfunction "VCCINT_M8") (pintype "power_in"))
      (node (ref "U9") (pin "N11") (pinfunction "VCCBRAM_N11") (pintype "power_in"))
      (node (ref "U9") (pin "N7") (pinfunction "VCCINT_N7") (pintype "power_in"))
      (node (ref "U9") (pin "P10") (pinfunction "VCCINT_P10") (pintype "power_in"))
      (node (ref "U9") (pin "P8") (pinfunction "VCCINT_P8") (pintype "power_in"))
      (node (ref "U9") (pin "R7") (pinfunction "VCCINT_R7") (pintype "power_in"))
      (node (ref "U9") (pin "R9") (pinfunction "VCCINT_R9") (pintype "power_in"))
      (node (ref "U9") (pin "T10") (pinfunction "VCCINT_T10") (pintype "power_in"))
      (node (ref "U9") (pin "T8") (pinfunction "VCCINT_T8") (pintype "power_in"))
    )
    (net (code "2") (name "+1V2") (class "Default")
      (node (ref "C39") (pin "2") (pinfunction "2_2") (pintype "passive"))
      (node (ref "C48") (pin "2") (pinfunction "2_2") (pintype "passive"))
      (node (ref "C49") (pin "2") (pinfunction "2_2") (pintype "passive"))
      (node (ref "C50") (pin "2") (pinfunction "2_2") (pintype "passive"))
      (node (ref "C51") (pin "2") (pinfunction "2_2") (pintype "passive"))
      (node (ref "C52") (pin "2") (pinfunction "2_2") (pintype "passive"))
      (node (ref "C53") (pin "2") (pinfunction "2_2") (pintype "passive"))
      (node (ref "C54") (pin "2") (pinfunction "2_2") (pintype "passive"))
      (node (ref "C55") (pin "2") (pinfunction "2_2") (pintype "passive"))
      (node (ref "R32") (pin "1") (pinfunction "1_1") (pintype "passive"))
      (node (ref "U9") (pin "B11") (pinfunction "MGTAVTT_B11") (pintype "power_in"))
      (node (ref "U9") (pin "B5") (pinfunction "MGTAVTT_B5") (pintype "power_in"))
      (node (ref "U9") (pin "B7") (pinfunction "MGTAVTT_B7") (pintype "power_in"))
      (node (ref "U9") (pin "B9") (pinfunction "MGTAVTT_B9") (pintype "power_in"))
      (node (ref "U9") (pin "C4") (pinfunction "MGTAVTT_C4") (pintype "power_in"))
      (node (ref "U9") (pin "C8") (pinfunction "MGTAVTT_C8") (pintype "power_in"))
    )
    (net (code "3") (name "+1V8") (class "Default")
      (node (ref "C103") (pin "2") (pinfunction "2_2") (pintype "passive"))
      (node (ref "C104") (pin "2") (pinfunction "2_2") (pintype "passive"))
      (node (ref "C115") (pin "2") (pinfunction "2_2") (pintype "passive"))
      (node (ref "C116") (pin "2") (pinfunction "2_2") (pintype "passive"))
      (node (ref "C117") (pin "2") (pinfunction "2_2") (pintype "passive"))
      (node (ref "C118") (pin "2") (pinfunction "2_2") (pintype "passive"))
      (node (ref "C119") (pin "2") (pinfunction "2_2") (pintype "passive"))
      (node (ref "C120") (pin "2") (pinfunction "2_2") (pintype "passive"))
      (node (ref "C89") (pin "2") (pinfunction "2_2") (pintype "passive"))
      (node (ref "C90") (pin "2") (pinfunction "2_2") (pintype "passive"))
      (node (ref "C91") (pin "2") (pinfunction "2_2") (pintype "passive"))
      (node (ref "C92") (pin "2") (pinfunction "2_2") (pintype "passive"))
      (node (ref "C93") (pin "2") (pinfunction "2_2") (pintype "passive"))
      (node (ref "C94") (pin "2") (pinfunction "2_2") (pintype "passive"))
      (node (ref "U9") (pin "C1") (pinfunction "VCCO_35_C1") (pintype "power_in"))
      (node (ref "U9") (pin "E12") (pinfunction "VCCBATT_0_E12") (pintype "power_in"))
      (node (ref "U9") (pin "F2") (pinfunction "VCCO_35_F2") (pintype "power_in"))
      (node (ref "U9") (pin "H12") (pinfunction "VCCAUX_H12") (pintype "power_in"))
      (node (ref "U9") (pin "H6") (pinfunction "VCCO_35_H6") (pintype "power_in"))
      (node (ref "U9") (pin "J3") (pinfunction "VCCO_35_J3") (pintype "power_in"))
      (node (ref "U9") (pin "K10") (pinfunction "VCCADC_0_K10") (pintype "power_in"))
      (node (ref "U9") (pin "K12") (pinfunction "VCCAUX_K12") (pintype "power_in"))
      (node (ref "U9") (pin "M12") (pinfunction "VCCAUX_M12") (pintype "power_in"))
      (node (ref "U9") (pin "M4") (pinfunction "VCCO_35_M4") (pintype "power_in"))
      (node (ref "U9") (pin "N1") (pinfunction "VCCO_35_N1") (pintype "power_in"))
      (node (ref "U9") (pin "P12") (pinfunction "VCCAUX_P12") (pintype "power_in"))
      (node (ref "U9") (pin "R11") (pinfunction "VCCAUX_R11") (pintype "power_in"))
    )
    (net (code "4") (name "+3V3") (class "Default")
      (node (ref "C100") (pin "2") (pinfunction "2_2") (pintype "passive"))
      (node (ref "C101") (pin "2") (pinfunction "2_2") (pintype "passive"))
      (node (ref "C105") (pin "2") (pinfunction "2_2") (pintype "passive"))
      (node (ref "C40") (pin "2") (pinfunction "2_2") (pintype "passive"))
      (node (ref "C41") (pin "2") (pinfunction "2_2") (pintype "passive"))
      (node (ref "C42") (pin "2") (pinfunction "2_2") (pintype "passive"))
      (node (ref "C45") (pin "2") (pinfunction "2_2") (pintype "passive"))
      (node (ref "C46") (pin "2") (pinfunction "2_2") (pintype "passive"))
      (node (ref "C63") (pin "2") (pinfunction "2_2") (pintype "passive"))
      (node (ref "C64") (pin "2") (pinfunction "2_2") (pintype "passive"))
      (node (ref "C66") (pin "2") (pinfunction "2_2") (pintype "passive"))
      (node (ref "C67") (pin "2") (pinfunction "2_2") (pintype "passive"))
      (node (ref "C68") (pin "2") (pinfunction "2_2") (pintype "passive"))
      (node (ref "C69") (pin "2") (pinfunction "2_2") (pintype "passive"))
      (node (ref "C70") (pin "2") (pinfunction "2_2") (pintype "passive"))
      (node (ref "C71") (pin "2") (pinfunction "2_2") (pintype "passive"))
      (node (ref "C72") (pin "2") (pinfunction "2_2") (pintype "passive"))
      (node (ref "C73") (pin "2") (pinfunction "2_2") (pintype "passive"))
      (node (ref "C74") (pin "2") (pinfunction "2_2") (pintype "passive"))
      (node (ref "C75") (pin "2") (pinfunction "2_2") (pintype "passive"))
      (node (ref "C76") (pin "2") (pinfunction "2_2") (pintype "passive"))
      (node (ref "C77") (pin "2") (pinfunction "2_2") (pintype "passive"))
      (node (ref "C78") (pin "2") (pinfunction "2_2") (pintype "passive"))
      (node (ref "C79") (pin "2") (pinfunction "2_2") (pintype "passive"))
      (node (ref "C80") (pin "2") (pinfunction "2_2") (pintype "passive"))
      (node (ref "C81") (pin "2") (pinfunction "2_2") (pintype "passive"))
      (node (ref "C82") (pin "2") (pinfunction "2_2") (pintype "passive"))
      (node (ref "C83") (pin "2") (pinfunction "2_2") (pintype "passive"))
      (node (ref "C84") (pin "2") (pinfunction "2_2") (pintype "passive"))
      (node (ref "C85") (pin "2") (pinfunction "2_2") (pintype "passive"))
      (node (ref "C86") (pin "2") (pinfunction "2_2") (pintype "passive"))
      (node (ref "C87") (pin "2") (pinfunction "2_2") (pintype "passive"))
      (node (ref "C88") (pin "2") (pinfunction "2_2") (pintype "passive"))
      (node (ref "C95") (pin "2") (pinfunction "2_2") (pintype "passive"))
      (node (ref "C96") (pin "2") (pinfunction "2_2") (pintype "passive"))
      (node (ref "C97") (pin "2") (pinfunction "2_2") (pintype "passive"))
      (node (ref "C98") (pin "2") (pinfunction "2_2") (pintype "passive"))
      (node (ref "C99") (pin "2") (pinfunction "2_2") (pintype "passive"))
      (node (ref "Q1") (pin "2") (pinfunction "SOURCE_2") (pintype "passive"))
      (node (ref "R34") (pin "2") (pinfunction "2_2") (pintype "passive"))
      (node (ref "R35") (pin "2") (pinfunction "2_2") (pintype "passive"))
      (node (ref "R36") (pin "2") (pinfunction "2_2") (pintype "passive"))
      (node (ref "R37") (pin "2") (pinfunction "2_2") (pintype "passive"))
      (node (ref "R38") (pin "2") (pinfunction "2_2") (pintype "passive"))
      (node (ref "R39") (pin "2") (pinfunction "2_2") (pintype "passive"))
      (node (ref "R40") (pin "2") (pinfunction "2_2") (pintype "passive"))
      (node (ref "R42") (pin "2") (pinfunction "2_2") (pintype "passive"))
      (node (ref "R45") (pin "2") (pinfunction "2_2") (pintype "passive"))
      (node (ref "R46") (pin "2") (pinfunction "2_2") (pintype "passive"))
      (node (ref "U10") (pin "1") (pinfunction "VDD_1") (pintype "power_in"))
      (node (ref "U11") (pin "1") (pinfunction "OE_1") (pintype "passive"))
      (node (ref "U11") (pin "6") (pinfunction "VCC_6") (pintype "passive"))
      (node (ref "U12") (pin "1") (pinfunction "IN_1") (pintype "power_in"))
      (node (ref "U13") (pin "3") (pinfunction "WP#_3") (pintype "passive"))
      (node (ref "U13") (pin "7") (pinfunction "HOLD/RST_7") (pintype "passive"))
      (node (ref "U13") (pin "8") (pinfunction "VCC_8") (pintype "passive"))
      (node (ref "U9") (pin "A17") (pinfunction "VCCO_16_A17") (pintype "power_in"))
      (node (ref "U9") (pin "AA17") (pinfunction "VCCO_13_AA17") (pintype "power_in"))
      (node (ref "U9") (pin "AA7") (pinfunction "VCCO_34_AA7") (pintype "power_in"))
      (node (ref "U9") (pin "AB14") (pinfunction "VCCO_13_AB14") (pintype "power_in"))
      (node (ref "U9") (pin "AB4") (pinfunction "VCCO_34_AB4") (pintype "power_in"))
      (node (ref "U9") (pin "B14") (pinfunction "VCCO_16_B14") (pintype "power_in"))
      (node (ref "U9") (pin "C21") (pinfunction "VCCO_16_C21") (pintype "power_in"))
      (node (ref "U9") (pin "D18") (pinfunction "VCCO_16_D18") (pintype "power_in"))
      (node (ref "U9") (pin "E15") (pinfunction "VCCO_16_E15") (pintype "power_in"))
      (node (ref "U9") (pin "F12") (pinfunction "VCCO_0_F12") (pintype "power_in"))
      (node (ref "U9") (pin "F22") (pinfunction "VCCO_16_F22") (pintype "power_in"))
      (node (ref "U9") (pin "G19") (pinfunction "VCCO_15_G19") (pintype "power_in"))
      (node (ref "U9") (pin "H16") (pinfunction "VCCO_15_H16") (pintype "power_in"))
      (node (ref "U9") (pin "J13") (pinfunction "VCCO_15_J13") (pintype "power_in"))
      (node (ref "U9") (pin "K20") (pinfunction "VCCO_15_K20") (pintype "power_in"))
      (node (ref "U9") (pin "L17") (pinfunction "VCCO_15_L17") (pintype "power_in"))
      (node (ref "U9") (pin "M14") (pinfunction "VCCO_14_M14") (pintype "power_in"))
      (node (ref "U9") (pin "N21") (pinfunction "VCCO_15_N21") (pintype "power_in"))
      (node (ref "U9") (pin "P18") (pinfunction "VCCO_14_P18") (pintype "power_in"))
      (node (ref "U9") (pin "R15") (pinfunction "VCCO_14_R15") (pintype "power_in"))
      (node (ref "U9") (pin "R5") (pinfunction "VCCO_34_R5") (pintype "power_in"))
      (node (ref "U9") (pin "T12") (pinfunction "VCCO_0_T12") (pintype "power_in"))
      (node (ref "U9") (pin "T2") (pinfunction "VCCO_34_T2") (pintype "power_in"))
      (node (ref "U9") (pin "T22") (pinfunction "VCCO_14_T22") (pintype "power_in"))
      (node (ref "U9") (pin "U19") (pinfunction "VCCO_14_U19") (pintype "power_in"))
      (node (ref "U9") (pin "V16") (pinfunction "VCCO_13_V16") (pintype "power_in"))
      (node (ref "U9") (pin "V6") (pinfunction "VCCO_34_V6") (pintype "power_in"))
      (node (ref "U9") (pin "W13") (pinfunction "VCCO_13_W13") (pintype "power_in"))
      (node (ref "U9") (pin "W3") (pinfunction "VCCO_34_W3") (pintype "power_in"))
      (node (ref "U9") (pin "Y10") (pinfunction "VCCO_13_Y10") (pintype "power_in"))
      (node (ref "U9") (pin "Y20") (pinfunction "VCCO_14_Y20") (pintype "power_in"))
      (node (ref "X1") (pin "1") (pinfunction "EN_1") (pintype "passive"))
      (node (ref "X1") (pin "4") (pinfunction "VDD_4") (pintype "passive"))
    )
    (net (code "5") (name "/DP_RX_AUX_N") (class "Default")
      (node (ref "U9") (pin "P1") (pinfunction "IO_L20N_T3_35_P1") (pintype "bidirectional"))
    )
    (net (code "6") (name "/DP_RX_AUX_P") (class "Default")
      (node (ref "U9") (pin "R1") (pinfunction "IO_L20P_T3_35_R1") (pintype "bidirectional"))
    )
    (net (code "7") (name "/DP_RX_HPD") (class "Default")
      (node (ref "U9") (pin "J6") (pinfunction "IO_L17N_T2_35_J6") (pintype "bidirectional"))
    )
    (net (code "8") (name "/DP_RX_L0_FPGA1_N") (class "Default")
      (node (ref "U9") (pin "A8") (pinfunction "MGTPRXN0_216_A8") (pintype "input"))
    )
    (net (code "9") (name "/DP_RX_L0_FPGA1_P") (class "Default")
      (node (ref "U9") (pin "B8") (pinfunction "MGTPRXP0_216_B8") (pintype "input"))
    )
    (net (code "10") (name "/DP_RX_L1_FPGA1_N") (class "Default")
      (node (ref "U9") (pin "C11") (pinfunction "MGTPRXN1_216_C11") (pintype "input"))
    )
    (net (code "11") (name "/DP_RX_L1_FPGA1_P") (class "Default")
      (node (ref "U9") (pin "D11") (pinfunction "MGTPRXP1_216_D11") (pintype "input"))
    )
    (net (code "12") (name "/DP_RX_L2_FPGA1_N") (class "Default")
      (node (ref "U9") (pin "A10") (pinfunction "MGTPRXN2_216_A10") (pintype "input"))
    )
    (net (code "13") (name "/DP_RX_L2_FPGA1_P") (class "Default")
      (node (ref "U9") (pin "B10") (pinfunction "MGTPRXP2_216_B10") (pintype "input"))
    )
    (net (code "14") (name "/DP_RX_L3_FPGA1_N") (class "Default")
      (node (ref "U9") (pin "C9") (pinfunction "MGTPRXN3_216_C9") (pintype "input"))
    )
    (net (code "15") (name "/DP_RX_L3_FPGA1_P") (class "Default")
      (node (ref "U9") (pin "D9") (pinfunction "MGTPRXP3_216_D9") (pintype "input"))
    )
    (net (code "16") (name "/DP_TX_AUX_N") (class "Default")
      (node (ref "U9") (pin "L4") (pinfunction "IO_L18N_T2_35_L4") (pintype "bidirectional"))
    )
    (net (code "17") (name "/DP_TX_AUX_P") (class "Default")
      (node (ref "U9") (pin "L5") (pinfunction "IO_L18P_T2_35_L5") (pintype "bidirectional"))
    )
    (net (code "18") (name "/DP_TX_HPD") (class "Default")
      (node (ref "U9") (pin "K6") (pinfunction "IO_L17P_T2_35_K6") (pintype "bidirectional"))
    )
    (net (code "19") (name "/DP_TX_L0_FPGA1_N") (class "Default")
      (node (ref "U9") (pin "A4") (pinfunction "MGTPTXN0_216_A4") (pintype "output"))
    )
    (net (code "20") (name "/DP_TX_L0_FPGA1_P") (class "Default")
      (node (ref "U9") (pin "B4") (pinfunction "MGTPTXP0_216_B4") (pintype "output"))
    )
    (net (code "21") (name "/DP_TX_L1_FPGA1_N") (class "Default")
      (node (ref "U9") (pin "C5") (pinfunction "MGTPTXN1_216_C5") (pintype "output"))
    )
    (net (code "22") (name "/DP_TX_L1_FPGA1_P") (class "Default")
      (node (ref "U9") (pin "D5") (pinfunction "MGTPTXP1_216_D5") (pintype "output"))
    )
    (net (code "23") (name "/DP_TX_L2_FPGA1_N") (class "Default")
      (node (ref "U9") (pin "A6") (pinfunction "MGTPTXN2_216_A6") (pintype "output"))
    )
    (net (code "24") (name "/DP_TX_L2_FPGA1_P") (class "Default")
      (node (ref "U9") (pin "B6") (pinfunction "MGTPTXP2_216_B6") (pintype "output"))
    )
    (net (code "25") (name "/DP_TX_L3_FPGA1_N") (class "Default")
      (node (ref "U9") (pin "C7") (pinfunction "MGTPTXN3_216_C7") (pintype "output"))
    )
    (net (code "26") (name "/DP_TX_L3_FPGA1_P") (class "Default")
      (node (ref "U9") (pin "D7") (pinfunction "MGTPTXP3_216_D7") (pintype "output"))
    )
    (net (code "27") (name "/FPGA1_ADC_IN_N") (class "Default")
      (node (ref "R49") (pin "1") (pinfunction "1_1") (pintype "passive"))
      (node (ref "R51") (pin "1") (pinfunction "1_1") (pintype "passive"))
      (node (ref "U9") (pin "M9") (pinfunction "VN_0_M9") (pintype "input"))
    )
    (net (code "28") (name "/FPGA1_ADC_IN_P") (class "Default")
      (node (ref "R48") (pin "1") (pinfunction "1_1") (pintype "passive"))
      (node (ref "R49") (pin "2") (pinfunction "2_2") (pintype "passive"))
      (node (ref "U9") (pin "L10") (pinfunction "VP_0_L10") (pintype "input"))
    )
    (net (code "29") (name "/FPGA1_ADC_IN_R_N") (class "Default")
      (node (ref "J2") (pin "2") (pinfunction "2_2") (pintype "passive"))
      (node (ref "J2") (pin "3") (pinfunction "3_3") (pintype "passive"))
      (node (ref "J2") (pin "4") (pinfunction "4_4") (pintype "passive"))
      (node (ref "J2") (pin "5") (pinfunction "5_5") (pintype "passive"))
      (node (ref "R50") (pin "1") (pinfunction "1_1") (pintype "passive"))
      (node (ref "R51") (pin "2") (pinfunction "2_2") (pintype "passive"))
    )
    (net (code "30") (name "/FPGA1_ADC_IN_R_P") (class "Default")
      (node (ref "J2") (pin "1") (pinfunction "1_1") (pintype "passive"))
      (node (ref "R48") (pin "2") (pinfunction "2_2") (pintype "passive"))
      (node (ref "R50") (pin "2") (pinfunction "2_2") (pintype "passive"))
    )
    (net (code "31") (name "/FPGA1_ADC_VREF_N") (class "Default")
      (node (ref "C102") (pin "1") (pinfunction "1_1") (pintype "passive"))
      (node (ref "L5") (pin "2") (pinfunction "2_2") (pintype "passive"))
      (node (ref "U9") (pin "L9") (pinfunction "VREFN_0_L9") (pintype "input"))
    )
    (net (code "32") (name "/FPGA1_ADC_VREF_P") (class "Default")
      (node (ref "C102") (pin "2") (pinfunction "2_2") (pintype "passive"))
      (node (ref "U12") (pin "2") (pinfunction "OUT_2") (pintype "power_in"))
      (node (ref "U9") (pin "M10") (pinfunction "VREFP_0_M10") (pintype "input"))
    )
    (net (code "33") (name "/FPGA1_CFGBVS") (class "Default")
      (node (ref "R37") (pin "1") (pinfunction "1_1") (pintype "passive"))
      (node (ref "U9") (pin "U8") (pinfunction "CFGBVS_0_U8") (pintype "input"))
    )
    (net (code "34") (name "/FPGA1_DONE") (class "Default")
      (node (ref "Q2") (pin "1") (pinfunction "G_1") (pintype "passive"))
      (node (ref "U9") (pin "G11") (pinfunction "DONE_0_G11") (pintype "bidirectional"))
    )
    (net (code "35") (name "/FPGA1_FLASH_CLK") (class "Default")
      (node (ref "U13") (pin "6") (pinfunction "SCK_6") (pintype "passive"))
      (node (ref "U9") (pin "L12") (pinfunction "CCLK_0_L12") (pintype "bidirectional"))
    )
    (net (code "36") (name "/FPGA1_FLASH_DIN") (class "Default")
      (node (ref "U13") (pin "2") (pinfunction "SO_2") (pintype "passive"))
      (node (ref "U9") (pin "R22") (pinfunction "IO_L1N_T0_D01_DIN_14_R22") (pintype "bidirectional"))
    )
    (net (code "37") (name "/FPGA1_FLASH_DOUT") (class "Default")
      (node (ref "U13") (pin "5") (pinfunction "SI_5") (pintype "passive"))
      (node (ref "U9") (pin "P22") (pinfunction "IO_L1P_T0_D00_MOSI_14_P22") (pintype "bidirectional"))
    )
    (net (code "38") (name "/FPGA1_FLASH_FCS_B") (class "Default")
      (node (ref "R46") (pin "1") (pinfunction "1_1") (pintype "passive"))
      (node (ref "U13") (pin "1") (pinfunction "CE#_1") (pintype "passive"))
      (node (ref "U9") (pin "T19") (pinfunction "IO_L6P_T0_FCS_B_14_T19") (pintype "bidirectional"))
    )
    (net (code "39") (name "/FPGA1_GTP_CLK_C_N") (class "Default")
      (node (ref "C44") (pin "2") (pinfunction "2_2") (pintype "passive"))
      (node (ref "U11") (pin "5") (pinfunction "OUT_N_5") (pintype "passive"))
    )
    (net (code "40") (name "/FPGA1_GTP_CLK_C_P") (class "Default")
      (node (ref "C43") (pin "2") (pinfunction "2_2") (pintype "passive"))
      (node (ref "U11") (pin "4") (pinfunction "OUT_P_4") (pintype "passive"))
    )
    (net (code "41") (name "/FPGA1_GTP_CLK_N") (class "Default")
      (node (ref "C44") (pin "1") (pinfunction "1_1") (pintype "passive"))
      (node (ref "U9") (pin "E6") (pinfunction "MGTREFCLK0N_216_E6") (pintype "input"))
    )
    (net (code "42") (name "/FPGA1_GTP_CLK_P") (class "Default")
      (node (ref "C43") (pin "1") (pinfunction "1_1") (pintype "passive"))
      (node (ref "U9") (pin "F6") (pinfunction "MGTREFCLK0P_216_F6") (pintype "input"))
    )
    (net (code "43") (name "/FPGA1_INITB") (class "Default")
      (node (ref "Q1") (pin "1") (pinfunction "GATE_1") (pintype "passive"))
      (node (ref "R38") (pin "1") (pinfunction "1_1") (pintype "passive"))
      (node (ref "U9") (pin "U12") (pinfunction "INIT_B_0_U12") (pintype "bidirectional"))
    )
    (net (code "44") (name "/FPGA1_LED0") (class "Default")
      (node (ref "U9") (pin "N13") (pinfunction "IO_L23P_T3_A03_D19_14_N13") (pintype "bidirectional"))
    )
    (net (code "45") (name "/FPGA1_LED1") (class "Default")
      (node (ref "U9") (pin "N14") (pinfunction "IO_L23N_T3_A02_D18_14_N14") (pintype "bidirectional"))
    )
    (net (code "46") (name "/FPGA1_LED2") (class "Default")
      (node (ref "U9") (pin "N15") (pinfunction "IO_25_14_N15") (pintype "bidirectional"))
    )
    (net (code "47") (name "/FPGA1_LED3") (class "Default")
      (node (ref "U9") (pin "P15") (pinfunction "IO_L22P_T3_A05_D21_14_P15") (pintype "bidirectional"))
    )
    (net (code "48") (name "/FPGA1_LED4") (class "Default")
      (node (ref "U9") (pin "P16") (pinfunction "IO_L24P_T3_A01_D17_14_P16") (pintype "bidirectional"))
    )
    (net (code "49") (name "/FPGA1_LED5") (class "Default")
      (node (ref "U9") (pin "R16") (pinfunction "IO_L22N_T3_A04_D20_14_R16") (pintype "bidirectional"))
    )
    (net (code "50") (name "/FPGA1_LED6") (class "Default")
      (node (ref "U9") (pin "R17") (pinfunction "IO_L24N_T3_A00_D16_14_R17") (pintype "bidirectional"))
    )
    (net (code "51") (name "/FPGA1_LED7") (class "Default")
      (node (ref "U9") (pin "P17") (pinfunction "IO_L21N_T3_DQS_A06_D22_14_P17") (pintype "bidirectional"))
    )
    (net (code "53") (name "/FPGA1_M0") (class "Default")
      (node (ref "R34") (pin "1") (pinfunction "1_1") (pintype "passive"))
      (node (ref "SW5") (pin "1") (pinfunction "1_1") (pintype "passive"))
      (node (ref "U9") (pin "U11") (pinfunction "M0_0_U11") (pintype "input"))
    )
    (net (code "54") (name "/FPGA1_M1") (class "Default")
      (node (ref "R35") (pin "1") (pinfunction "1_1") (pintype "passive"))
      (node (ref "SW5") (pin "2") (pinfunction "2_2") (pintype "passive"))
      (node (ref "U9") (pin "U10") (pinfunction "M1_0_U10") (pintype "input"))
    )
    (net (code "55") (name "/FPGA1_M2") (class "Default")
      (node (ref "R36") (pin "1") (pinfunction "1_1") (pintype "passive"))
      (node (ref "SW5") (pin "3") (pinfunction "3_3") (pintype "passive"))
      (node (ref "U9") (pin "U9") (pinfunction "M2_0_U9") (pintype "input"))
    )
    (net (code "56") (name "/FPGA1_PMOD0_IO0") (class "Default")
      (node (ref "U9") (pin "A1") (pinfunction "IO_L1N_T0_AD4N_35_A1") (pintype "bidirectional"))
    )
    (net (code "57") (name "/FPGA1_PMOD0_IO1") (class "Default")
      (node (ref "U9") (pin "B2") (pinfunction "IO_L2N_T0_AD12N_35_B2") (pintype "bidirectional"))
    )
    (net (code "58") (name "/FPGA1_PMOD0_IO2") (class "Default")
      (node (ref "U9") (pin "D1") (pinfunction "IO_L3N_T0_DQS_AD5N_35_D1") (pintype "bidirectional"))
    )
    (net (code "59") (name "/FPGA1_PMOD0_IO3") (class "Default")
      (node (ref "U9") (pin "E1") (pinfunction "IO_L3P_T0_DQS_AD5P_35_E1") (pintype "bidirectional"))
    )
    (net (code "60") (name "/FPGA1_PMOD0_IO4") (class "Default")
      (node (ref "U9") (pin "E2") (pinfunction "IO_L4P_T0_35_E2") (pintype "bidirectional"))
    )
    (net (code "61") (name "/FPGA1_PMOD0_IO5") (class "Default")
      (node (ref "U9") (pin "D2") (pinfunction "IO_L4N_T0_35_D2") (pintype "bidirectional"))
    )
    (net (code "62") (name "/FPGA1_PMOD0_IO6") (class "Default")
      (node (ref "U9") (pin "C2") (pinfunction "IO_L2P_T0_AD12P_35_C2") (pintype "bidirectional"))
    )
    (net (code "63") (name "/FPGA1_PMOD0_IO7") (class "Default")
      (node (ref "U9") (pin "B1") (pinfunction "IO_L1P_T0_AD4P_35_B1") (pintype "bidirectional"))
    )
    (net (code "65") (name "/FPGA1_PMOD1_IO0") (class "Default")
      (node (ref "U9") (pin "F1") (pinfunction "IO_L5N_T0_AD13N_35_F1") (pintype "bidirectional"))
    )
    (net (code "66") (name "/FPGA1_PMOD1_IO1") (class "Default")
      (node (ref "U9") (pin "G1") (pinfunction "IO_L5P_T0_AD13P_35_G1") (pintype "bidirectional"))
    )
    (net (code "67") (name "/FPGA1_PMOD1_IO2") (class "Default")
      (node (ref "U9") (pin "G2") (pinfunction "IO_L8N_T1_AD14N_35_G2") (pintype "bidirectional"))
    )
    (net (code "68") (name "/FPGA1_PMOD1_IO3") (class "Default")
      (node (ref "U9") (pin "J1") (pinfunction "IO_L7N_T1_AD6N_35_J1") (pintype "bidirectional"))
    )
    (net (code "69") (name "/FPGA1_PMOD1_IO4") (class "Default")
      (node (ref "U9") (pin "K1") (pinfunction "IO_L7P_T1_AD6P_35_K1") (pintype "bidirectional"))
    )
    (net (code "70") (name "/FPGA1_PMOD1_IO5") (class "Default")
      (node (ref "U9") (pin "H2") (pinfunction "IO_L8P_T1_AD14P_35_H2") (pintype "bidirectional"))
    )
    (net (code "71") (name "/FPGA1_PMOD1_IO6") (class "Default")
      (node (ref "U9") (pin "F3") (pinfunction "IO_L6P_T0_35_F3") (pintype "bidirectional"))
    )
    (net (code "72") (name "/FPGA1_PMOD1_IO7") (class "Default")
      (node (ref "U9") (pin "E3") (pinfunction "IO_L6N_T0_VREF_35_E3") (pintype "bidirectional"))
    )
    (net (code "74") (name "/FPGA1_PMOD2_IO0") (class "Default")
      (node (ref "U9") (pin "G3") (pinfunction "IO_L11N_T1_SRCC_35_G3") (pintype "bidirectional"))
    )
    (net (code "75") (name "/FPGA1_PMOD2_IO1") (class "Default")
      (node (ref "U9") (pin "J2") (pinfunction "IO_L9N_T1_DQS_AD7N_35_J2") (pintype "bidirectional"))
    )
    (net (code "76") (name "/FPGA1_PMOD2_IO2") (class "Default")
      (node (ref "U9") (pin "G4") (pinfunction "IO_L12N_T1_MRCC_35_G4") (pintype "bidirectional"))
    )
    (net (code "77") (name "/FPGA1_PMOD2_IO3") (class "Default")
      (node (ref "U9") (pin "H4") (pinfunction "IO_L12P_T1_MRCC_35_H4") (pintype "bidirectional"))
    )
    (net (code "78") (name "/FPGA1_PMOD2_IO4") (class "Default")
      (node (ref "U9") (pin "H5") (pinfunction "IO_L10N_T1_AD15N_35_H5") (pintype "bidirectional"))
    )
    (net (code "79") (name "/FPGA1_PMOD2_IO5") (class "Default")
      (node (ref "U9") (pin "J5") (pinfunction "IO_L10P_T1_AD15P_35_J5") (pintype "bidirectional"))
    )
    (net (code "80") (name "/FPGA1_PMOD2_IO6") (class "Default")
      (node (ref "U9") (pin "H3") (pinfunction "IO_L11P_T1_SRCC_35_H3") (pintype "bidirectional"))
    )
    (net (code "81") (name "/FPGA1_PMOD2_IO7") (class "Default")
      (node (ref "U9") (pin "K2") (pinfunction "IO_L9P_T1_DQS_AD7P_35_K2") (pintype "bidirectional"))
    )
    (net (code "83") (name "/FPGA1_PMOD3_IO0") (class "Default")
      (node (ref "U9") (pin "J4") (pinfunction "IO_L13N_T2_MRCC_35_J4") (pintype "bidirectional"))
    )
    (net (code "84") (name "/FPGA1_PMOD3_IO1") (class "Default")
      (node (ref "U9") (pin "L1") (pinfunction "IO_L15N_T2_DQS_35_L1") (pintype "bidirectional"))
    )
    (net (code "85") (name "/FPGA1_PMOD3_IO2") (class "Default")
      (node (ref "U9") (pin "M1") (pinfunction "IO_L15P_T2_DQS_35_M1") (pintype "bidirectional"))
    )
    (net (code "86") (name "/FPGA1_PMOD3_IO3") (class "Default")
      (node (ref "U9") (pin "M3") (pinfunction "IO_L16P_T2_35_M3") (pintype "bidirectional"))
    )
    (net (code "87") (name "/FPGA1_PMOD3_IO4") (class "Default")
      (node (ref "U9") (pin "K4") (pinfunction "IO_L13P_T2_MRCC_35_K4") (pintype "bidirectional"))
    )
    (net (code "88") (name "/FPGA1_PMOD3_IO5") (class "Default")
      (node (ref "U9") (pin "M2") (pinfunction "IO_L16N_T2_35_M2") (pintype "bidirectional"))
    )
    (net (code "89") (name "/FPGA1_PMOD3_IO6") (class "Default")
      (node (ref "U9") (pin "L3") (pinfunction "IO_L14P_T2_SRCC_35_L3") (pintype "bidirectional"))
    )
    (net (code "90") (name "/FPGA1_PMOD3_IO7") (class "Default")
      (node (ref "U9") (pin "K3") (pinfunction "IO_L14N_T2_SRCC_35_K3") (pintype "bidirectional"))
    )
    (net (code "92") (name "/FPGA1_PROGB") (class "Default")
      (node (ref "R41") (pin "1") (pinfunction "1_1") (pintype "passive"))
      (node (ref "U9") (pin "N12") (pinfunction "PROGRAM_B_0_N12") (pintype "input"))
    )
    (net (code "93") (name "/FPGA1_PUDC_B") (class "Default")
      (node (ref "R39") (pin "1") (pinfunction "1_1") (pintype "passive"))
      (node (ref "U9") (pin "U22") (pinfunction "IO_L3P_T0_DQS_PUDC_B_14_U22") (pintype "bidirectional"))
    )
    (net (code "94") (name "/FPGA1_SYS_CLK_P") (class "Default")
      (node (ref "C135") (pin "2") (pinfunction "2_2") (pintype "passive"))
      (node (ref "U9") (pin "Y18") (pinfunction "IO_L13P_T2_MRCC_14_Y18") (pintype "input"))
      (node (ref "X1") (pin "3") (pinfunction "OUT_3") (pintype "passive"))
    )
    (net (code "95") (name "/FPGA1_SYS_RST") (class "Default")
      (node (ref "R43") (pin "1") (pinfunction "1_1") (pintype "passive"))
      (node (ref "U9") (pin "V18") (pinfunction "IO_L14P_T2_SRCC_14_V18") (pintype "bidirectional"))
    )
    (net (code "96") (name "/FPGA_LINK_BUS_IO0") (class "Default")
      (node (ref "TP16") (pin "1") (pinfunction "1_1") (pintype "passive"))
      (node (ref "U9") (pin "J15") (pinfunction "IO_L5P_T0_AD9P_15_J15") (pintype "bidirectional"))
    )
    (net (code "97") (name "/FPGA_LINK_BUS_IO1") (class "Default")
      (node (ref "TP17") (pin "1") (pinfunction "1_1") (pintype "passive"))
      (node (ref "U9") (pin "L14") (pinfunction "IO_L22P_T3_A17_15_L14") (pintype "bidirectional"))
    )
    (net (code "98") (name "/FPGA_LINK_BUS_IO2") (class "Default")
      (node (ref "TP18") (pin "1") (pinfunction "1_1") (pintype "passive"))
      (node (ref "U9") (pin "L15") (pinfunction "IO_L22N_T3_A16_15_L15") (pintype "bidirectional"))
    )
    (net (code "99") (name "/FPGA_LINK_BUS_IO3") (class "Default")
      (node (ref "TP19") (pin "1") (pinfunction "1_1") (pintype "passive"))
      (node (ref "U9") (pin "K14") (pinfunction "IO_L19N_T3_A21_VREF_15_K14") (pintype "bidirectional"))
    )
    (net (code "100") (name "/FPGA_LINK_BUS_IO4") (class "Default")
      (node (ref "TP20") (pin "1") (pinfunction "1_1") (pintype "passive"))
      (node (ref "U9") (pin "M13") (pinfunction "IO_L20P_T3_A20_15_M13") (pintype "bidirectional"))
    )
    (net (code "101") (name "/FPGA_LINK_BUS_IO5") (class "Default")
      (node (ref "TP21") (pin "1") (pinfunction "1_1") (pintype "passive"))
      (node (ref "U9") (pin "M15") (pinfunction "IO_L24P_T3_RS1_15_M15") (pintype "bidirectional"))
    )
    (net (code "102") (name "/FPGA_LINK_BUS_IO6") (class "Default")
      (node (ref "TP22") (pin "1") (pinfunction "1_1") (pintype "passive"))
      (node (ref "U9") (pin "L16") (pinfunction "IO_L23P_T3_FOE_B_15_L16") (pintype "bidirectional"))
    )
    (net (code "103") (name "/FPGA_LINK_BUS_IO7") (class "Default")
      (node (ref "TP23") (pin "1") (pinfunction "1_1") (pintype "passive"))
      (node (ref "U9") (pin "K13") (pinfunction "IO_L19P_T3_A22_15_K13") (pintype "bidirectional"))
    )
    (net (code "104") (name "/FPGA_LINK_BUS_IO8") (class "Default")
      (node (ref "TP24") (pin "1") (pinfunction "1_1") (pintype "passive"))
      (node (ref "U9") (pin "L13") (pinfunction "IO_L20N_T3_A19_15_L13") (pintype "bidirectional"))
    )
    (net (code "105") (name "/FPGA_LINK_BUS_IO9") (class "Default")
      (node (ref "TP25") (pin "1") (pinfunction "1_1") (pintype "passive"))
      (node (ref "U9") (pin "M17") (pinfunction "IO_25_15_M17") (pintype "bidirectional"))
    )
    (net (code "106") (name "/FPGA_LINK_BUS_IO10") (class "Default")
      (node (ref "TP26") (pin "1") (pinfunction "1_1") (pintype "passive"))
      (node (ref "U9") (pin "M16") (pinfunction "IO_L24N_T3_RS0_15_M16") (pintype "bidirectional"))
    )
    (net (code "107") (name "/FPGA_LINK_BUS_IO11") (class "Default")
      (node (ref "TP27") (pin "1") (pinfunction "1_1") (pintype "passive"))
      (node (ref "U9") (pin "N19") (pinfunction "IO_L17N_T2_A25_15_N19") (pintype "bidirectional"))
    )
    (net (code "108") (name "/FPGA_LINK_BUS_IO12") (class "Default")
      (node (ref "TP28") (pin "1") (pinfunction "1_1") (pintype "passive"))
      (node (ref "U9") (pin "L19") (pinfunction "IO_L14P_T2_SRCC_15_L19") (pintype "bidirectional"))
    )
    (net (code "109") (name "/FPGA_LINK_BUS_IO13") (class "Default")
      (node (ref "TP29") (pin "1") (pinfunction "1_1") (pintype "passive"))
      (node (ref "U9") (pin "K19") (pinfunction "IO_L13N_T2_MRCC_15_K19") (pintype "bidirectional"))
    )
    (net (code "110") (name "/FPGA_LINK_BUS_IO14") (class "Default")
      (node (ref "TP30") (pin "1") (pinfunction "1_1") (pintype "passive"))
      (node (ref "U9") (pin "J21") (pinfunction "IO_L11N_T1_SRCC_15_J21") (pintype "bidirectional"))
    )
    (net (code "111") (name "/FPGA_LINK_BUS_IO15") (class "Default")
      (node (ref "TP31") (pin "1") (pinfunction "1_1") (pintype "passive"))
      (node (ref "U9") (pin "G20") (pinfunction "IO_L8N_T1_AD10N_15_G20") (pintype "bidirectional"))
    )
    (net (code "112") (name "/FPGA_LINK_BUS_IO16") (class "Default")
      (node (ref "TP32") (pin "1") (pinfunction "1_1") (pintype "passive"))
      (node (ref "U9") (pin "H17") (pinfunction "IO_L6P_T0_15_H17") (pintype "bidirectional"))
    )
    (net (code "113") (name "/FPGA_LINK_BUS_IO17") (class "Default")
      (node (ref "TP33") (pin "1") (pinfunction "1_1") (pintype "passive"))
      (node (ref "U9") (pin "H13") (pinfunction "IO_L1P_T0_AD0P_15_H13") (pintype "bidirectional"))
    )
    (net (code "114") (name "/FPGA_LINK_BUS_IO18") (class "Default")
      (node (ref "TP34") (pin "1") (pinfunction "1_1") (pintype "passive"))
      (node (ref "U9") (pin "G13") (pinfunction "IO_L1N_T0_AD0N_15_G13") (pintype "bidirectional"))
    )
    (net (code "115") (name "/FPGA_LINK_BUS_IO19") (class "Default")
      (node (ref "TP35") (pin "1") (pinfunction "1_1") (pintype "passive"))
      (node (ref "U9") (pin "H18") (pinfunction "IO_L6N_T0_VREF_15_H18") (pintype "bidirectional"))
    )
    (net (code "116") (name "/FPGA_LINK_BUS_IO20") (class "Default")
      (node (ref "TP36") (pin "1") (pinfunction "1_1") (pintype "passive"))
      (node (ref "U9") (pin "J17") (pinfunction "IO_L21N_T3_DQS_A18_15_J17") (pintype "bidirectional"))
    )
    (net (code "117") (name "/FPGA_LINK_BUS_IO21") (class "Default")
      (node (ref "TP37") (pin "1") (pinfunction "1_1") (pintype "passive"))
      (node (ref "U9") (pin "J19") (pinfunction "IO_L12P_T1_MRCC_15_J19") (pintype "bidirectional"))
    )
    (net (code "118") (name "/FPGA_LINK_BUS_IO22") (class "Default")
      (node (ref "TP38") (pin "1") (pinfunction "1_1") (pintype "passive"))
      (node (ref "U9") (pin "L20") (pinfunction "IO_L14N_T2_SRCC_15_L20") (pintype "bidirectional"))
    )
    (net (code "119") (name "/FPGA_LINK_BUS_IO23") (class "Default")
      (node (ref "TP39") (pin "1") (pinfunction "1_1") (pintype "passive"))
      (node (ref "U9") (pin "M20") (pinfunction "IO_L18N_T2_A23_15_M20") (pintype "bidirectional"))
    )
    (net (code "120") (name "/FPGA_LINK_BUS_IO24") (class "Default")
      (node (ref "TP40") (pin "1") (pinfunction "1_1") (pintype "passive"))
      (node (ref "U9") (pin "N18") (pinfunction "IO_L17P_T2_A26_15_N18") (pintype "bidirectional"))
    )
    (net (code "121") (name "/FPGA_LINK_BUS_IO25") (class "Default")
      (node (ref "TP41") (pin "1") (pinfunction "1_1") (pintype "passive"))
      (node (ref "U9") (pin "K16") (pinfunction "IO_L23N_T3_FWE_B_15_K16") (pintype "bidirectional"))
    )
    (net (code "122") (name "/FPGA_LINK_BUS_IO26") (class "Default")
      (node (ref "TP42") (pin "1") (pinfunction "1_1") (pintype "passive"))
      (node (ref "U9") (pin "K17") (pinfunction "IO_L21P_T3_DQS_15_K17") (pintype "bidirectional"))
    )
    (net (code "123") (name "/FPGA_LINK_BUS_IO27") (class "Default")
      (node (ref "TP43") (pin "1") (pinfunction "1_1") (pintype "passive"))
      (node (ref "U9") (pin "M18") (pinfunction "IO_L16P_T2_A28_15_M18") (pintype "bidirectional"))
    )
    (net (code "124") (name "/FPGA_LINK_BUS_IO28") (class "Default")
      (node (ref "TP44") (pin "1") (pinfunction "1_1") (pintype "passive"))
      (node (ref "U9") (pin "N20") (pinfunction "IO_L18P_T2_A24_15_N20") (pintype "bidirectional"))
    )
    (net (code "125") (name "/FPGA_LINK_BUS_IO29") (class "Default")
      (node (ref "TP45") (pin "1") (pinfunction "1_1") (pintype "passive"))
      (node (ref "U9") (pin "M21") (pinfunction "IO_L10P_T1_AD11P_15_M21") (pintype "bidirectional"))
    )
    (net (code "126") (name "/FPGA_LINK_BUS_IO30") (class "Default")
      (node (ref "TP46") (pin "1") (pinfunction "1_1") (pintype "passive"))
      (node (ref "U9") (pin "K22") (pinfunction "IO_L9N_T1_DQS_AD3N_15_K22") (pintype "bidirectional"))
    )
    (net (code "127") (name "/FPGA_LINK_BUS_IO31") (class "Default")
      (node (ref "TP47") (pin "1") (pinfunction "1_1") (pintype "passive"))
      (node (ref "U9") (pin "J20") (pinfunction "IO_L11P_T1_SRCC_15_J20") (pintype "bidirectional"))
    )
    (net (code "128") (name "/FPGA_LINK_BUS_IO32") (class "Default")
      (node (ref "TP48") (pin "1") (pinfunction "1_1") (pintype "passive"))
      (node (ref "U9") (pin "G18") (pinfunction "IO_L4N_T0_15_G18") (pintype "bidirectional"))
    )
    (net (code "129") (name "/FPGA_LINK_BUS_IO33") (class "Default")
      (node (ref "TP49") (pin "1") (pinfunction "1_1") (pintype "passive"))
      (node (ref "U9") (pin "G15") (pinfunction "IO_L2P_T0_AD8P_15_G15") (pintype "bidirectional"))
    )
    (net (code "130") (name "/FPGA_LINK_BUS_IO34") (class "Default")
      (node (ref "TP50") (pin "1") (pinfunction "1_1") (pintype "passive"))
      (node (ref "U9") (pin "J14") (pinfunction "IO_L3P_T0_DQS_AD1P_15_J14") (pintype "bidirectional"))
    )
    (net (code "131") (name "/FPGA_LINK_BUS_IO35") (class "Default")
      (node (ref "TP51") (pin "1") (pinfunction "1_1") (pintype "passive"))
      (node (ref "U9") (pin "H15") (pinfunction "IO_L5N_T0_AD9N_15_H15") (pintype "bidirectional"))
    )
    (net (code "132") (name "/FPGA_LINK_BUS_IO36") (class "Default")
      (node (ref "TP52") (pin "1") (pinfunction "1_1") (pintype "passive"))
      (node (ref "U9") (pin "H14") (pinfunction "IO_L3N_T0_DQS_AD1N_15_H14") (pintype "bidirectional"))
    )
    (net (code "133") (name "/FPGA_LINK_BUS_IO37") (class "Default")
      (node (ref "TP53") (pin "1") (pinfunction "1_1") (pintype "passive"))
      (node (ref "U9") (pin "G16") (pinfunction "IO_L2N_T0_AD8N_15_G16") (pintype "bidirectional"))
    )
    (net (code "134") (name "/FPGA_LINK_BUS_IO38") (class "Default")
      (node (ref "TP54") (pin "1") (pinfunction "1_1") (pintype "passive"))
      (node (ref "U9") (pin "J16") (pinfunction "IO_0_15_J16") (pintype "bidirectional"))
    )
    (net (code "135") (name "/FPGA_LINK_BUS_IO39") (class "Default")
      (node (ref "TP55") (pin "1") (pinfunction "1_1") (pintype "passive"))
      (node (ref "U9") (pin "G17") (pinfunction "IO_L4P_T0_15_G17") (pintype "bidirectional"))
    )
    (net (code "136") (name "/FPGA_LINK_BUS_IO40") (class "Default")
      (node (ref "TP56") (pin "1") (pinfunction "1_1") (pintype "passive"))
      (node (ref "U9") (pin "H19") (pinfunction "IO_L12N_T1_MRCC_15_H19") (pintype "bidirectional"))
    )
    (net (code "137") (name "/FPGA_LINK_BUS_IO41") (class "Default")
      (node (ref "TP57") (pin "1") (pinfunction "1_1") (pintype "passive"))
      (node (ref "U9") (pin "H20") (pinfunction "IO_L8P_T1_AD10P_15_H20") (pintype "bidirectional"))
    )
    (net (code "138") (name "/FPGA_LINK_BUS_IO42") (class "Default")
      (node (ref "TP58") (pin "1") (pinfunction "1_1") (pintype "passive"))
      (node (ref "U9") (pin "H22") (pinfunction "IO_L7N_T1_AD2N_15_H22") (pintype "bidirectional"))
    )
    (net (code "139") (name "/FPGA_LINK_BUS_IO43") (class "Default")
      (node (ref "TP59") (pin "1") (pinfunction "1_1") (pintype "passive"))
      (node (ref "U9") (pin "J22") (pinfunction "IO_L7P_T1_AD2P_15_J22") (pintype "bidirectional"))
    )
    (net (code "140") (name "/FPGA_LINK_BUS_IO44") (class "Default")
      (node (ref "TP60") (pin "1") (pinfunction "1_1") (pintype "passive"))
      (node (ref "U9") (pin "K21") (pinfunction "IO_L9P_T1_DQS_AD3P_15_K21") (pintype "bidirectional"))
    )
    (net (code "141") (name "/FPGA_LINK_BUS_IO45") (class "Default")
      (node (ref "TP61") (pin "1") (pinfunction "1_1") (pintype "passive"))
      (node (ref "U9") (pin "L21") (pinfunction "IO_L10N_T1_AD11N_15_L21") (pintype "bidirectional"))
    )
    (net (code "142") (name "/FPGA_LINK_BUS_IO46") (class "Default")
      (node (ref "TP62") (pin "1") (pinfunction "1_1") (pintype "passive"))
      (node (ref "U9") (pin "M22") (pinfunction "IO_L15N_T2_DQS_ADV_B_15_M22") (pintype "bidirectional"))
    )
    (net (code "143") (name "/FPGA_LINK_BUS_IO47") (class "Default")
      (node (ref "TP63") (pin "1") (pinfunction "1_1") (pintype "passive"))
      (node (ref "U9") (pin "N22") (pinfunction "IO_L15P_T2_DQS_15_N22") (pintype "bidirectional"))
    )
    (net (code "144") (name "/FPGA_LINK_BUS_IO48") (class "Default")
      (node (ref "TP64") (pin "1") (pinfunction "1_1") (pintype "passive"))
      (node (ref "U9") (pin "K18") (pinfunction "IO_L13P_T2_MRCC_15_K18") (pintype "bidirectional"))
    )
    (net (code "145") (name "/FPGA_LINK_BUS_IO49") (class "Default")
      (node (ref "TP65") (pin "1") (pinfunction "1_1") (pintype "passive"))
      (node (ref "U9") (pin "L18") (pinfunction "IO_L16N_T2_A27_15_L18") (pintype "bidirectional"))
    )
    (net (code "146") (name "/FPGA_LINK_BUS_IO50") (class "Default")
      (node (ref "TP66") (pin "1") (pinfunction "1_1") (pintype "passive"))
      (node (ref "U9") (pin "D14") (pinfunction "IO_L6P_T0_16_D14") (pintype "bidirectional"))
    )
    (net (code "147") (name "/FPGA_LINK_BUS_IO51") (class "Default")
      (node (ref "TP67") (pin "1") (pinfunction "1_1") (pintype "passive"))
      (node (ref "U9") (pin "D15") (pinfunction "IO_L6N_T0_VREF_16_D15") (pintype "bidirectional"))
    )
    (net (code "148") (name "/FPGA_LINK_BUS_IO52") (class "Default")
      (node (ref "TP68") (pin "1") (pinfunction "1_1") (pintype "passive"))
      (node (ref "U9") (pin "C13") (pinfunction "IO_L8P_T1_16_C13") (pintype "bidirectional"))
    )
    (net (code "149") (name "/FPGA_LINK_BUS_IO53") (class "Default")
      (node (ref "TP69") (pin "1") (pinfunction "1_1") (pintype "passive"))
      (node (ref "U9") (pin "A14") (pinfunction "IO_L10N_T1_16_A14") (pintype "bidirectional"))
    )
    (net (code "150") (name "/FPGA_LINK_BUS_IO54") (class "Default")
      (node (ref "TP70") (pin "1") (pinfunction "1_1") (pintype "passive"))
      (node (ref "U9") (pin "A13") (pinfunction "IO_L10P_T1_16_A13") (pintype "bidirectional"))
    )
    (net (code "151") (name "/FPGA_LINK_BUS_IO55") (class "Default")
      (node (ref "TP71") (pin "1") (pinfunction "1_1") (pintype "passive"))
      (node (ref "U9") (pin "B13") (pinfunction "IO_L8N_T1_16_B13") (pintype "bidirectional"))
    )
    (net (code "152") (name "/FPGA_LINK_BUS_IO56") (class "Default")
      (node (ref "TP72") (pin "1") (pinfunction "1_1") (pintype "passive"))
      (node (ref "U9") (pin "C14") (pinfunction "IO_L3P_T0_DQS_16_C14") (pintype "bidirectional"))
    )
    (net (code "153") (name "/FPGA_LINK_BUS_IO57") (class "Default")
      (node (ref "TP73") (pin "1") (pinfunction "1_1") (pintype "passive"))
      (node (ref "U9") (pin "C15") (pinfunction "IO_L3N_T0_DQS_16_C15") (pintype "bidirectional"))
    )
    (net (code "154") (name "/FPGA_LINK_BUS_IO58") (class "Default")
      (node (ref "TP74") (pin "1") (pinfunction "1_1") (pintype "passive"))
      (node (ref "U9") (pin "B15") (pinfunction "IO_L7P_T1_16_B15") (pintype "bidirectional"))
    )
    (net (code "155") (name "/FPGA_LINK_BUS_IO59") (class "Default")
      (node (ref "TP75") (pin "1") (pinfunction "1_1") (pintype "passive"))
      (node (ref "U9") (pin "D16") (pinfunction "IO_L5N_T0_16_D16") (pintype "bidirectional"))
    )
    (net (code "156") (name "/FPGA_LINK_BUS_IO60") (class "Default")
      (node (ref "TP76") (pin "1") (pinfunction "1_1") (pintype "passive"))
      (node (ref "U9") (pin "B16") (pinfunction "IO_L7N_T1_16_B16") (pintype "bidirectional"))
    )
    (net (code "157") (name "/FPGA_LINK_BUS_IO61") (class "Default")
      (node (ref "TP77") (pin "1") (pinfunction "1_1") (pintype "passive"))
      (node (ref "U9") (pin "D17") (pinfunction "IO_L12P_T1_MRCC_16_D17") (pintype "bidirectional"))
    )
    (net (code "158") (name "/FPGA_LINK_BUS_IO62") (class "Default")
      (node (ref "TP78") (pin "1") (pinfunction "1_1") (pintype "passive"))
      (node (ref "U9") (pin "A19") (pinfunction "IO_L17N_T2_16_A19") (pintype "bidirectional"))
    )
    (net (code "159") (name "/FPGA_LINK_BUS_IO63") (class "Default")
      (node (ref "TP79") (pin "1") (pinfunction "1_1") (pintype "passive"))
      (node (ref "U9") (pin "A18") (pinfunction "IO_L17P_T2_16_A18") (pintype "bidirectional"))
    )
    (net (code "160") (name "/FPGA_LINK_BUS_IO64") (class "Default")
      (node (ref "TP80") (pin "1") (pinfunction "1_1") (pintype "passive"))
      (node (ref "U9") (pin "B17") (pinfunction "IO_L11P_T1_SRCC_16_B17") (pintype "bidirectional"))
    )
    (net (code "161") (name "/FPGA_LINK_BUS_IO65") (class "Default")
      (node (ref "TP81") (pin "1") (pinfunction "1_1") (pintype "passive"))
      (node (ref "U9") (pin "A16") (pinfunction "IO_L9N_T1_DQS_16_A16") (pintype "bidirectional"))
    )
    (net (code "162") (name "/FPGA_LINK_BUS_IO66") (class "Default")
      (node (ref "TP82") (pin "1") (pinfunction "1_1") (pintype "passive"))
      (node (ref "U9") (pin "A15") (pinfunction "IO_L9P_T1_DQS_16_A15") (pintype "bidirectional"))
    )
    (net (code "163") (name "/FPGA_LINK_BUS_IO67") (class "Default")
      (node (ref "TP83") (pin "1") (pinfunction "1_1") (pintype "passive"))
      (node (ref "U9") (pin "C17") (pinfunction "IO_L12N_T1_MRCC_16_C17") (pintype "bidirectional"))
    )
    (net (code "164") (name "/FPGA_LINK_BUS_IO68") (class "Default")
      (node (ref "TP84") (pin "1") (pinfunction "1_1") (pintype "passive"))
      (node (ref "U9") (pin "B18") (pinfunction "IO_L11N_T1_SRCC_16_B18") (pintype "bidirectional"))
    )
    (net (code "165") (name "/FPGA_LINK_BUS_IO69") (class "Default")
      (node (ref "TP85") (pin "1") (pinfunction "1_1") (pintype "passive"))
      (node (ref "U9") (pin "C18") (pinfunction "IO_L13P_T2_MRCC_16_C18") (pintype "bidirectional"))
    )
    (net (code "166") (name "/FPGA_LINK_BUS_IO70") (class "Default")
      (node (ref "TP86") (pin "1") (pinfunction "1_1") (pintype "passive"))
      (node (ref "U9") (pin "C19") (pinfunction "IO_L13N_T2_MRCC_16_C19") (pintype "bidirectional"))
    )
    (net (code "167") (name "/FPGA_LINK_BUS_IO71") (class "Default")
      (node (ref "TP87") (pin "1") (pinfunction "1_1") (pintype "passive"))
      (node (ref "U9") (pin "C20") (pinfunction "IO_L19N_T3_VREF_16_C20") (pintype "bidirectional"))
    )
    (net (code "168") (name "/FPGA_LINK_BUS_IO72") (class "Default")
      (node (ref "TP88") (pin "1") (pinfunction "1_1") (pintype "passive"))
      (node (ref "U9") (pin "D22") (pinfunction "IO_L22N_T3_16_D22") (pintype "bidirectional"))
    )
    (net (code "169") (name "/FPGA_LINK_BUS_IO73") (class "Default")
      (node (ref "TP89") (pin "1") (pinfunction "1_1") (pintype "passive"))
      (node (ref "U9") (pin "D20") (pinfunction "IO_L19P_T3_16_D20") (pintype "bidirectional"))
    )
    (net (code "170") (name "/FPGA_LINK_BUS_IO74") (class "Default")
      (node (ref "TP90") (pin "1") (pinfunction "1_1") (pintype "passive"))
      (node (ref "U9") (pin "B21") (pinfunction "IO_L21P_T3_DQS_16_B21") (pintype "bidirectional"))
    )
    (net (code "171") (name "/FPGA_LINK_BUS_IO75") (class "Default")
      (node (ref "TP91") (pin "1") (pinfunction "1_1") (pintype "passive"))
      (node (ref "U9") (pin "A21") (pinfunction "IO_L21N_T3_DQS_16_A21") (pintype "bidirectional"))
    )
    (net (code "172") (name "/FPGA_LINK_BUS_IO76") (class "Default")
      (node (ref "TP92") (pin "1") (pinfunction "1_1") (pintype "passive"))
      (node (ref "U9") (pin "A20") (pinfunction "IO_L16N_T2_16_A20") (pintype "bidirectional"))
    )
    (net (code "173") (name "/FPGA_LINK_BUS_IO77") (class "Default")
      (node (ref "TP93") (pin "1") (pinfunction "1_1") (pintype "passive"))
      (node (ref "U9") (pin "B20") (pinfunction "IO_L16P_T2_16_B20") (pintype "bidirectional"))
    )
    (net (code "174") (name "/FPGA_LINK_BUS_IO78") (class "Default")
      (node (ref "TP94") (pin "1") (pinfunction "1_1") (pintype "passive"))
      (node (ref "U9") (pin "B22") (pinfunction "IO_L20N_T3_16_B22") (pintype "bidirectional"))
    )
    (net (code "175") (name "/FPGA_LINK_BUS_IO79") (class "Default")
      (node (ref "TP95") (pin "1") (pinfunction "1_1") (pintype "passive"))
      (node (ref "U9") (pin "D21") (pinfunction "IO_L23N_T3_16_D21") (pintype "bidirectional"))
    )
    (net (code "176") (name "/FPGA_LINK_BUS_IO80") (class "Default")
      (node (ref "TP96") (pin "1") (pinfunction "1_1") (pintype "passive"))
      (node (ref "U9") (pin "E22") (pinfunction "IO_L22P_T3_16_E22") (pintype "bidirectional"))
    )
    (net (code "177") (name "/FPGA_LINK_BUS_IO81") (class "Default")
      (node (ref "TP97") (pin "1") (pinfunction "1_1") (pintype "passive"))
      (node (ref "U9") (pin "F21") (pinfunction "IO_25_16_F21") (pintype "bidirectional"))
    )
    (net (code "178") (name "/FPGA_LINK_BUS_IO82") (class "Default")
      (node (ref "TP98") (pin "1") (pinfunction "1_1") (pintype "passive"))
      (node (ref "U9") (pin "E18") (pinfunction "IO_L15N_T2_DQS_16_E18") (pintype "bidirectional"))
    )
    (net (code "179") (name "/FPGA_LINK_BUS_IO83") (class "Default")
      (node (ref "TP99") (pin "1") (pinfunction "1_1") (pintype "passive"))
      (node (ref "U9") (pin "G22") (pinfunction "IO_L24N_T3_16_G22") (pintype "bidirectional"))
    )
    (net (code "180") (name "/FPGA_LINK_BUS_IO84") (class "Default")
      (node (ref "TP100") (pin "1") (pinfunction "1_1") (pintype "passive"))
      (node (ref "U9") (pin "E19") (pinfunction "IO_L14P_T2_SRCC_16_E19") (pintype "bidirectional"))
    )
    (net (code "181") (name "/FPGA_LINK_BUS_IO85") (class "Default")
      (node (ref "TP101") (pin "1") (pinfunction "1_1") (pintype "passive"))
      (node (ref "U9") (pin "D19") (pinfunction "IO_L14N_T2_SRCC_16_D19") (pintype "bidirectional"))
    )
    (net (code "182") (name "/FPGA_LINK_BUS_IO86") (class "Default")
      (node (ref "TP102") (pin "1") (pinfunction "1_1") (pintype "passive"))
      (node (ref "U9") (pin "C22") (pinfunction "IO_L20P_T3_16_C22") (pintype "bidirectional"))
    )
    (net (code "183") (name "/FPGA_LINK_BUS_IO87") (class "Default")
      (node (ref "TP103") (pin "1") (pinfunction "1_1") (pintype "passive"))
      (node (ref "U9") (pin "E21") (pinfunction "IO_L23P_T3_16_E21") (pintype "bidirectional"))
    )
    (net (code "184") (name "/FPGA_LINK_BUS_IO88") (class "Default")
      (node (ref "TP104") (pin "1") (pinfunction "1_1") (pintype "passive"))
      (node (ref "U9") (pin "F20") (pinfunction "IO_L18N_T2_16_F20") (pintype "bidirectional"))
    )
    (net (code "185") (name "/FPGA_LINK_BUS_IO89") (class "Default")
      (node (ref "TP105") (pin "1") (pinfunction "1_1") (pintype "passive"))
      (node (ref "U9") (pin "F19") (pinfunction "IO_L18P_T2_16_F19") (pintype "bidirectional"))
    )
    (net (code "186") (name "/FPGA_LINK_BUS_IO90") (class "Default")
      (node (ref "TP106") (pin "1") (pinfunction "1_1") (pintype "passive"))
      (node (ref "U9") (pin "E17") (pinfunction "IO_L2N_T0_16_E17") (pintype "bidirectional"))
    )
    (net (code "187") (name "/FPGA_LINK_BUS_IO91") (class "Default")
      (node (ref "TP107") (pin "1") (pinfunction "1_1") (pintype "passive"))
      (node (ref "U9") (pin "F15") (pinfunction "IO_0_16_F15") (pintype "bidirectional"))
    )
    (net (code "188") (name "/FPGA_LINK_BUS_IO92") (class "Default")
      (node (ref "TP108") (pin "1") (pinfunction "1_1") (pintype "passive"))
      (node (ref "U9") (pin "F14") (pinfunction "IO_L1N_T0_16_F14") (pintype "bidirectional"))
    )
    (net (code "189") (name "/FPGA_LINK_BUS_IO93") (class "Default")
      (node (ref "TP109") (pin "1") (pinfunction "1_1") (pintype "passive"))
      (node (ref "U9") (pin "F16") (pinfunction "IO_L2P_T0_16_F16") (pintype "bidirectional"))
    )
    (net (code "190") (name "/FPGA_LINK_BUS_IO94") (class "Default")
      (node (ref "TP110") (pin "1") (pinfunction "1_1") (pintype "passive"))
      (node (ref "U9") (pin "F18") (pinfunction "IO_L15P_T2_DQS_16_F18") (pintype "bidirectional"))
    )
    (net (code "191") (name "/FPGA_LINK_BUS_IO95") (class "Default")
      (node (ref "TP111") (pin "1") (pinfunction "1_1") (pintype "passive"))
      (node (ref "U9") (pin "G21") (pinfunction "IO_L24P_T3_16_G21") (pintype "bidirectional"))
    )
    (net (code "192") (name "/FPGA_LINK_BUS_IO96") (class "Default")
      (node (ref "TP112") (pin "1") (pinfunction "1_1") (pintype "passive"))
      (node (ref "U9") (pin "E16") (pinfunction "IO_L5P_T0_16_E16") (pintype "bidirectional"))
    )
    (net (code "193") (name "/FPGA_LINK_BUS_IO97") (class "Default")
      (node (ref "TP113") (pin "1") (pinfunction "1_1") (pintype "passive"))
      (node (ref "U9") (pin "E14") (pinfunction "IO_L4N_T0_16_E14") (pintype "bidirectional"))
    )
    (net (code "194") (name "/FPGA_LINK_BUS_IO98") (class "Default")
      (node (ref "TP114") (pin "1") (pinfunction "1_1") (pintype "passive"))
      (node (ref "U9") (pin "E13") (pinfunction "IO_L4P_T0_16_E13") (pintype "bidirectional"))
    )
    (net (code "195") (name "/FPGA_LINK_BUS_IO99") (class "Default")
      (node (ref "TP115") (pin "1") (pinfunction "1_1") (pintype "passive"))
      (node (ref "U9") (pin "F13") (pinfunction "IO_L1P_T0_16_F13") (pintype "bidirectional"))
    )
    (net (code "197") (name "/INITB_F1") (class "Default")
      (node (ref "DS1") (pin "1") (pinfunction "A_1") (pintype "passive"))
      (node (ref "Q1") (pin "3") (pinfunction "DRAIN_3") (pintype "passive"))
    )
    (net (code "198") (name "/JTAG_TCK_FPGA1") (class "Default")
      (node (ref "U9") (pin "V12") (pinfunction "TCK_0_V12") (pintype "input"))
    )
    (net (code "199") (name "/JTAG_TDI_FPGA1") (class "Default")
      (node (ref "U9") (pin "R13") (pinfunction "TDI_0_R13") (pintype "input"))
    )
    (net (code "200") (name "/JTAG_TDO_FPGA1") (class "Default")
      (node (ref "U9") (pin "U13") (pinfunction "TDO_0_U13") (pintype "output"))
    )
    (net (code "201") (name "/JTAG_TMS_FPGA1") (class "Default")
      (node (ref "U9") (pin "T13") (pinfunction "TMS_0_T13") (pintype "input"))
    )
    (net (code "202") (name "/MCU_FPGA1_IO0") (class "Default")
      (node (ref "U9") (pin "AB21") (pinfunction "IO_L10P_T1_D14_14_AB21") (pintype "bidirectional"))
    )
    (net (code "203") (name "/MCU_FPGA1_IO1") (class "Default")
      (node (ref "U9") (pin "AB22") (pinfunction "IO_L10N_T1_D15_14_AB22") (pintype "bidirectional"))
    )
    (net (code "204") (name "/MCU_FPGA1_IO2") (class "Default")
      (node (ref "U9") (pin "U20") (pinfunction "IO_L11P_T1_SRCC_14_U20") (pintype "bidirectional"))
    )
    (net (code "205") (name "/MCU_FPGA1_IO3") (class "Default")
      (node (ref "U9") (pin "V20") (pinfunction "IO_L11N_T1_SRCC_14_V20") (pintype "bidirectional"))
    )
    (net (code "206") (name "/MCU_FPGA1_IO4") (class "Default")
      (node (ref "U9") (pin "Y22") (pinfunction "IO_L9N_T1_DQS_D13_14_Y22") (pintype "bidirectional"))
    )
    (net (code "207") (name "/MCU_FPGA1_IO5") (class "Default")
      (node (ref "U9") (pin "W22") (pinfunction "IO_L7N_T1_D10_14_W22") (pintype "bidirectional"))
    )
    (net (code "208") (name "/MCU_FPGA1_IO6") (class "Default")
      (node (ref "U9") (pin "Y21") (pinfunction "IO_L9P_T1_DQS_14_Y21") (pintype "bidirectional"))
    )
    (net (code "209") (name "/MCU_FPGA1_IO7") (class "Default")
      (node (ref "U9") (pin "AA21") (pinfunction "IO_L8N_T1_D12_14_AA21") (pintype "bidirectional"))
    )
    (net (code "210") (name "/MCU_FPGA1_IO8") (class "Default")
      (node (ref "U9") (pin "AA20") (pinfunction "IO_L8P_T1_D11_14_AA20") (pintype "bidirectional"))
    )
    (net (code "212") (name "/PDONE_F1") (class "Default")
      (node (ref "DS2") (pin "2") (pinfunction "K_2") (pintype "passive"))
      (node (ref "Q2") (pin "3") (pinfunction "D_3") (pintype "passive"))
    )
    (net (code "213") (name "/SMC_ADC_TSNS_FPGA1") (class "Default")
      (node (ref "U10") (pin "2") (pinfunction "VOUT_2") (pintype "passive"))
    )
    (net (code "214") (name "/SMC_IO_FPGA1_IO0") (class "Default")
      (node (ref "U9") (pin "T21") (pinfunction "IO_L4P_T0_D04_14_T21") (pintype "bidirectional"))
    )
    (net (code "215") (name "/SMC_IO_FPGA1_IO1") (class "Default")
      (node (ref "U9") (pin "U21") (pinfunction "IO_L4N_T0_D05_14_U21") (pintype "bidirectional"))
    )
    (net (code "216") (name "/SMC_SPI_FPGA1_CLK") (class "Default")
      (node (ref "U9") (pin "W19") (pinfunction "IO_L12P_T1_MRCC_14_W19") (pintype "bidirectional"))
    )
    (net (code "217") (name "/SMC_SPI_FPGA1_CS") (class "Default")
      (node (ref "U9") (pin "AA19") (pinfunction "IO_L15P_T2_DQS_RDWR_B_14_AA19") (pintype "bidirectional"))
    )
    (net (code "218") (name "/SMC_SPI_FPGA1_RX") (class "Default")
      (node (ref "U9") (pin "AB20") (pinfunction "IO_L15N_T2_DQS_DOUT_CSO_B_14_AB20") (pintype "input"))
    )
    (net (code "219") (name "/SMC_SPI_FPGA1_TX") (class "Default")
      (node (ref "U9") (pin "V19") (pinfunction "IO_L14N_T2_SRCC_14_V19") (pintype "output"))
    )
    (net (code "220") (name "/UART_RX_FPGA1") (class "Default")
      (node (ref "U9") (pin "R21") (pinfunction "IO_L2N_T0_D03_14_R21") (pintype "output"))
    )
    (net (code "221") (name "/UART_TX_FPGA1") (class "Default")
      (node (ref "U9") (pin "P21") (pinfunction "IO_L2P_T0_D02_14_P21") (pintype "input"))
    )
    (net (code "222") (name "/USER_FPGA1_BUTTON0") (class "Default")
      (node (ref "U9") (pin "P14") (pinfunction "IO_L19P_T3_A10_D26_14_P14") (pintype "bidirectional"))
    )
    (net (code "223") (name "/USER_FPGA1_BUTTON1") (class "Default")
      (node (ref "U9") (pin "U17") (pinfunction "IO_L18P_T2_A12_D28_14_U17") (pintype "bidirectional"))
    )
    (net (code "224") (name "/USER_FPGA1_BUTTON2") (class "Default")
      (node (ref "U9") (pin "U18") (pinfunction "IO_L18N_T2_A11_D27_14_U18") (pintype "bidirectional"))
    )
    (net (code "225") (name "/USER_FPGA1_BUTTON3") (class "Default")
      (node (ref "U9") (pin "AB18") (pinfunction "IO_L17N_T2_A13_D29_14_AB18") (pintype "bidirectional"))
    )
    (net (code "227") (name "/USER_IO_FPGA1_IO0") (class "Default")
      (node (ref "U9") (pin "V5") (pinfunction "IO_L16N_T2_34_V5") (pintype "bidirectional"))
    )
    (net (code "228") (name "/USER_IO_FPGA1_IO1") (class "Default")
      (node (ref "U9") (pin "U6") (pinfunction "IO_L16P_T2_34_U6") (pintype "bidirectional"))
    )
    (net (code "229") (name "/USER_IO_FPGA1_IO2") (class "Default")
      (node (ref "U9") (pin "V7") (pinfunction "IO_L19P_T3_34_V7") (pintype "bidirectional"))
    )
    (net (code "230") (name "/USER_IO_FPGA1_IO3") (class "Default")
      (node (ref "U9") (pin "V9") (pinfunction "IO_L21P_T3_DQS_34_V9") (pintype "bidirectional"))
    )
    (net (code "231") (name "/USER_IO_FPGA1_IO4") (class "Default")
      (node (ref "U9") (pin "V8") (pinfunction "IO_L21N_T3_DQS_34_V8") (pintype "bidirectional"))
    )
    (net (code "232") (name "/USER_IO_FPGA1_IO5") (class "Default")
      (node (ref "U9") (pin "W9") (pinfunction "IO_L24P_T3_34_W9") (pintype "bidirectional"))
    )
    (net (code "233") (name "/USER_IO_FPGA1_IO6") (class "Default")
      (node (ref "U9") (pin "W6") (pinfunction "IO_L15P_T2_DQS_34_W6") (pintype "bidirectional"))
    )
    (net (code "234") (name "/USER_IO_FPGA1_IO7") (class "Default")
      (node (ref "U9") (pin "Y9") (pinfunction "IO_L24N_T3_34_Y9") (pintype "bidirectional"))
    )
    (net (code "235") (name "/USER_IO_FPGA1_IO8") (class "Default")
      (node (ref "U9") (pin "W7") (pinfunction "IO_L19N_T3_VREF_34_W7") (pintype "bidirectional"))
    )
    (net (code "236") (name "/USER_IO_FPGA1_IO9") (class "Default")
      (node (ref "U9") (pin "Y8") (pinfunction "IO_L23P_T3_34_Y8") (pintype "bidirectional"))
    )
    (net (code "237") (name "/USER_IO_FPGA1_IO10") (class "Default")
      (node (ref "U9") (pin "Y7") (pinfunction "IO_L23N_T3_34_Y7") (pintype "bidirectional"))
    )
    (net (code "238") (name "/USER_IO_FPGA1_IO11") (class "Default")
      (node (ref "U9") (pin "AA8") (pinfunction "IO_L22P_T3_34_AA8") (pintype "bidirectional"))
    )
    (net (code "239") (name "/USER_IO_FPGA1_IO12") (class "Default")
      (node (ref "U9") (pin "AB8") (pinfunction "IO_L22N_T3_34_AB8") (pintype "bidirectional"))
    )
    (net (code "240") (name "/USER_IO_FPGA1_IO13") (class "Default")
      (node (ref "U9") (pin "Y6") (pinfunction "IO_L18P_T2_34_Y6") (pintype "bidirectional"))
    )
    (net (code "241") (name "/USER_IO_FPGA1_IO14") (class "Default")
      (node (ref "U9") (pin "AB7") (pinfunction "IO_L20P_T3_34_AB7") (pintype "bidirectional"))
    )
    (net (code "242") (name "/USER_IO_FPGA1_IO15") (class "Default")
      (node (ref "U9") (pin "AA6") (pinfunction "IO_L18N_T2_34_AA6") (pintype "bidirectional"))
    )
    (net (code "243") (name "/USER_IO_FPGA1_IO16") (class "Default")
      (node (ref "U9") (pin "AB6") (pinfunction "IO_L20N_T3_34_AB6") (pintype "bidirectional"))
    )
    (net (code "244") (name "/USER_IO_FPGA1_IO17") (class "Default")
      (node (ref "U9") (pin "W5") (pinfunction "IO_L15N_T2_DQS_34_W5") (pintype "bidirectional"))
    )
    (net (code "245") (name "/USER_IO_FPGA1_IO18") (class "Default")
      (node (ref "U9") (pin "AB5") (pinfunction "IO_L10N_T1_34_AB5") (pintype "bidirectional"))
    )
    (net (code "246") (name "/USER_IO_FPGA1_IO19") (class "Default")
      (node (ref "U9") (pin "AA5") (pinfunction "IO_L10P_T1_34_AA5") (pintype "bidirectional"))
    )
    (net (code "247") (name "/USER_IO_FPGA1_IO20") (class "Default")
      (node (ref "U9") (pin "Y4") (pinfunction "IO_L11P_T1_SRCC_34_Y4") (pintype "bidirectional"))
    )
    (net (code "248") (name "/USER_IO_FPGA1_IO21") (class "Default")
      (node (ref "U9") (pin "AA4") (pinfunction "IO_L11N_T1_SRCC_34_AA4") (pintype "bidirectional"))
    )
    (net (code "249") (name "/USER_IO_FPGA1_IO22") (class "Default")
      (node (ref "U9") (pin "W4") (pinfunction "IO_L12N_T1_MRCC_34_W4") (pintype "bidirectional"))
    )
    (net (code "250") (name "/USER_IO_FPGA1_IO23") (class "Default")
      (node (ref "U9") (pin "AB3") (pinfunction "IO_L8P_T1_34_AB3") (pintype "bidirectional"))
    )
    (net (code "251") (name "/USER_IO_FPGA1_IO24") (class "Default")
      (node (ref "U9") (pin "AA3") (pinfunction "IO_L9N_T1_DQS_34_AA3") (pintype "bidirectional"))
    )
    (net (code "252") (name "/USER_IO_FPGA1_IO25") (class "Default")
      (node (ref "U9") (pin "AB2") (pinfunction "IO_L8N_T1_34_AB2") (pintype "bidirectional"))
    )
    (net (code "253") (name "/USER_IO_FPGA1_IO26") (class "Default")
      (node (ref "U9") (pin "Y3") (pinfunction "IO_L9P_T1_DQS_34_Y3") (pintype "bidirectional"))
    )
    (net (code "254") (name "/USER_IO_FPGA1_IO27") (class "Default")
      (node (ref "U9") (pin "AB1") (pinfunction "IO_L7N_T1_34_AB1") (pintype "bidirectional"))
    )
    (net (code "255") (name "/USER_IO_FPGA1_IO28") (class "Default")
      (node (ref "U9") (pin "Y2") (pinfunction "IO_L4N_T0_34_Y2") (pintype "bidirectional"))
    )
    (net (code "256") (name "/USER_IO_FPGA1_IO29") (class "Default")
      (node (ref "U9") (pin "AA1") (pinfunction "IO_L7P_T1_34_AA1") (pintype "bidirectional"))
    )
    (net (code "257") (name "/USER_IO_FPGA1_IO30") (class "Default")
      (node (ref "U9") (pin "V4") (pinfunction "IO_L12P_T1_MRCC_34_V4") (pintype "bidirectional"))
    )
    (net (code "258") (name "/USER_IO_FPGA1_IO31") (class "Default")
      (node (ref "U9") (pin "Y1") (pinfunction "IO_L5N_T0_34_Y1") (pintype "bidirectional"))
    )
    (net (code "259") (name "/USER_IO_FPGA1_IO32") (class "Default")
      (node (ref "U9") (pin "W2") (pinfunction "IO_L4P_T0_34_W2") (pintype "bidirectional"))
    )
    (net (code "260") (name "/USER_IO_FPGA1_IO33") (class "Default")
      (node (ref "U9") (pin "W1") (pinfunction "IO_L5P_T0_34_W1") (pintype "bidirectional"))
    )
    (net (code "261") (name "/USER_IO_FPGA1_IO34") (class "Default")
      (node (ref "U9") (pin "V3") (pinfunction "IO_L6N_T0_VREF_34_V3") (pintype "bidirectional"))
    )
    (net (code "262") (name "/USER_IO_FPGA1_IO35") (class "Default")
      (node (ref "U9") (pin "V2") (pinfunction "IO_L2N_T0_34_V2") (pintype "bidirectional"))
    )
    (net (code "263") (name "/USER_IO_FPGA1_IO36") (class "Default")
      (node (ref "U9") (pin "U3") (pinfunction "IO_L6P_T0_34_U3") (pintype "bidirectional"))
    )
    (net (code "264") (name "/USER_IO_FPGA1_IO37") (class "Default")
      (node (ref "U9") (pin "U2") (pinfunction "IO_L2P_T0_34_U2") (pintype "bidirectional"))
    )
    (net (code "265") (name "/USER_IO_FPGA1_IO38") (class "Default")
      (node (ref "U9") (pin "U1") (pinfunction "IO_L1N_T0_34_U1") (pintype "bidirectional"))
    )
    (net (code "266") (name "/USER_IO_FPGA1_IO39") (class "Default")
      (node (ref "U9") (pin "U5") (pinfunction "IO_L14N_T2_SRCC_34_U5") (pintype "bidirectional"))
    )
    (net (code "267") (name "/USER_IO_FPGA1_IO40") (class "Default")
      (node (ref "U9") (pin "T6") (pinfunction "IO_L17N_T2_34_T6") (pintype "bidirectional"))
    )
    (net (code "268") (name "/USER_IO_FPGA1_IO41") (class "Default")
      (node (ref "U9") (pin "T5") (pinfunction "IO_L14P_T2_SRCC_34_T5") (pintype "bidirectional"))
    )
    (net (code "269") (name "/USER_IO_FPGA1_IO42") (class "Default")
      (node (ref "U9") (pin "R4") (pinfunction "IO_L13P_T2_MRCC_34_R4") (pintype "bidirectional"))
    )
    (net (code "270") (name "/USER_IO_FPGA1_IO43") (class "Default")
      (node (ref "U9") (pin "T4") (pinfunction "IO_L13N_T2_MRCC_34_T4") (pintype "bidirectional"))
    )
    (net (code "271") (name "/USER_IO_FPGA1_IO44") (class "Default")
      (node (ref "U9") (pin "T1") (pinfunction "IO_L1P_T0_34_T1") (pintype "bidirectional"))
    )
    (net (code "272") (name "/USER_IO_FPGA1_IO45") (class "Default")
      (node (ref "U9") (pin "R2") (pinfunction "IO_L3N_T0_DQS_34_R2") (pintype "bidirectional"))
    )
    (net (code "273") (name "/USER_IO_FPGA1_IO46") (class "Default")
      (node (ref "U9") (pin "R3") (pinfunction "IO_L3P_T0_DQS_34_R3") (pintype "bidirectional"))
    )
    (net (code "274") (name "/USER_IO_FPGA1_IO47") (class "Default")
      (node (ref "U9") (pin "R6") (pinfunction "IO_L17P_T2_34_R6") (pintype "bidirectional"))
    )
    (net (code "276") (name "GND") (class "Default")
      (node (ref "C100") (pin "1") (pinfunction "1_1") (pintype "passive"))
      (node (ref "C101") (pin "1") (pinfunction "1_1") (pintype "passive"))
      (node (ref "C103") (pin "1") (pinfunction "1_1") (pintype "passive"))
      (node (ref "C104") (pin "1") (pinfunction "1_1") (pintype "passive"))
      (node (ref "C105") (pin "1") (pinfunction "1_1") (pintype "passive"))
      (node (ref "C106") (pin "1") (pinfunction "1_1") (pintype "passive"))
      (node (ref "C107") (pin "1") (pinfunction "1_1") (pintype "passive"))
      (node (ref "C108") (pin "1") (pinfunction "1_1") (pintype "passive"))
      (node (ref "C109") (pin "1") (pinfunction "1_1") (pintype "passive"))
      (node (ref "C110") (pin "1") (pinfunction "1_1") (pintype "passive"))
      (node (ref "C111") (pin "1") (pinfunction "1_1") (pintype "passive"))
      (node (ref "C112") (pin "1") (pinfunction "1_1") (pintype "passive"))
      (node (ref "C113") (pin "1") (pinfunction "1_1") (pintype "passive"))
      (node (ref "C114") (pin "1") (pinfunction "1_1") (pintype "passive"))
      (node (ref "C115") (pin "1") (pinfunction "1_1") (pintype "passive"))
      (node (ref "C116") (pin "1") (pinfunction "1_1") (pintype "passive"))
      (node (ref "C117") (pin "1") (pinfunction "1_1") (pintype "passive"))
      (node (ref "C118") (pin "1") (pinfunction "1_1") (pintype "passive"))
      (node (ref "C119") (pin "1") (pinfunction "1_1") (pintype "passive"))
      (node (ref "C120") (pin "1") (pinfunction "1_1") (pintype "passive"))
      (node (ref "C121") (pin "1") (pinfunction "1_1") (pintype "passive"))
      (node (ref "C122") (pin "1") (pinfunction "1_1") (pintype "passive"))
      (node (ref "C123") (pin "1") (pinfunction "1_1") (pintype "passive"))
      (node (ref "C124") (pin "1") (pinfunction "1_1") (pintype "passive"))
      (node (ref "C125") (pin "1") (pinfunction "1_1") (pintype "passive"))
      (node (ref "C126") (pin "1") (pinfunction "1_1") (pintype "passive"))
      (node (ref "C127") (pin "1") (pinfunction "1_1") (pintype "passive"))
      (node (ref "C128") (pin "1") (pinfunction "1_1") (pintype "passive"))
      (node (ref "C129") (pin "1") (pinfunction "1_1") (pintype "passive"))
      (node (ref "C130") (pin "1") (pinfunction "1_1") (pintype "passive"))
      (node (ref "C131") (pin "1") (pinfunction "1_1") (pintype "passive"))
      (node (ref "C132") (pin "1") (pinfunction "1_1") (pintype "passive"))
      (node (ref "C133") (pin "1") (pinfunction "1_1") (pintype "passive"))
      (node (ref "C135") (pin "1") (pinfunction "1_1") (pintype "passive"))
      (node (ref "C39") (pin "1") (pinfunction "1_1") (pintype "passive"))
      (node (ref "C40") (pin "1") (pinfunction "1_1") (pintype "passive"))
      (node (ref "C41") (pin "1") (pinfunction "1_1") (pintype "passive"))
      (node (ref "C42") (pin "1") (pinfunction "1_1") (pintype "passive"))
      (node (ref "C45") (pin "1") (pinfunction "1_1") (pintype "passive"))
      (node (ref "C46") (pin "1") (pinfunction "1_1") (pintype "passive"))
      (node (ref "C47") (pin "1") (pinfunction "1_1") (pintype "passive"))
      (node (ref "C48") (pin "1") (pinfunction "1_1") (pintype "passive"))
      (node (ref "C49") (pin "1") (pinfunction "1_1") (pintype "passive"))
      (node (ref "C50") (pin "1") (pinfunction "1_1") (pintype "passive"))
      (node (ref "C51") (pin "1") (pinfunction "1_1") (pintype "passive"))
      (node (ref "C52") (pin "1") (pinfunction "1_1") (pintype "passive"))
      (node (ref "C53") (pin "1") (pinfunction "1_1") (pintype "passive"))
      (node (ref "C54") (pin "1") (pinfunction "1_1") (pintype "passive"))
      (node (ref "C55") (pin "1") (pinfunction "1_1") (pintype "passive"))
      (node (ref "C56") (pin "1") (pinfunction "1_1") (pintype "passive"))
      (node (ref "C57") (pin "1") (pinfunction "1_1") (pintype "passive"))
      (node (ref "C58") (pin "1") (pinfunction "1_1") (pintype "passive"))
      (node (ref "C59") (pin "1") (pinfunction "1_1") (pintype "passive"))
      (node (ref "C60") (pin "1") (pinfunction "1_1") (pintype "passive"))
      (node (ref "C61") (pin "1") (pinfunction "1_1") (pintype "passive"))
      (node (ref "C62") (pin "1") (pinfunction "1_1") (pintype "passive"))
      (node (ref "C63") (pin "1") (pinfunction "1_1") (pintype "passive"))
      (node (ref "C64") (pin "1") (pinfunction "1_1") (pintype "passive"))
      (node (ref "C65") (pin "1") (pinfunction "1_1") (pintype "passive"))
      (node (ref "C66") (pin "1") (pinfunction "1_1") (pintype "passive"))
      (node (ref "C67") (pin "1") (pinfunction "1_1") (pintype "passive"))
      (node (ref "C68") (pin "1") (pinfunction "1_1") (pintype "passive"))
      (node (ref "C69") (pin "1") (pinfunction "1_1") (pintype "passive"))
      (node (ref "C70") (pin "1") (pinfunction "1_1") (pintype "passive"))
      (node (ref "C71") (pin "1") (pinfunction "1_1") (pintype "passive"))
      (node (ref "C72") (pin "1") (pinfunction "1_1") (pintype "passive"))
      (node (ref "C73") (pin "1") (pinfunction "1_1") (pintype "passive"))
      (node (ref "C74") (pin "1") (pinfunction "1_1") (pintype "passive"))
      (node (ref "C75") (pin "1") (pinfunction "1_1") (pintype "passive"))
      (node (ref "C76") (pin "1") (pinfunction "1_1") (pintype "passive"))
      (node (ref "C77") (pin "1") (pinfunction "1_1") (pintype "passive"))
      (node (ref "C78") (pin "1") (pinfunction "1_1") (pintype "passive"))
      (node (ref "C79") (pin "1") (pinfunction "1_1") (pintype "passive"))
      (node (ref "C80") (pin "1") (pinfunction "1_1") (pintype "passive"))
      (node (ref "C81") (pin "1") (pinfunction "1_1") (pintype "passive"))
      (node (ref "C82") (pin "1") (pinfunction "1_1") (pintype "passive"))
      (node (ref "C83") (pin "1") (pinfunction "1_1") (pintype "passive"))
      (node (ref "C84") (pin "1") (pinfunction "1_1") (pintype "passive"))
      (node (ref "C85") (pin "1") (pinfunction "1_1") (pintype "passive"))
      (node (ref "C86") (pin "1") (pinfunction "1_1") (pintype "passive"))
      (node (ref "C87") (pin "1") (pinfunction "1_1") (pintype "passive"))
      (node (ref "C88") (pin "1") (pinfunction "1_1") (pintype "passive"))
      (node (ref "C89") (pin "1") (pinfunction "1_1") (pintype "passive"))
      (node (ref "C90") (pin "1") (pinfunction "1_1") (pintype "passive"))
      (node (ref "C91") (pin "1") (pinfunction "1_1") (pintype "passive"))
      (node (ref "C92") (pin "1") (pinfunction "1_1") (pintype "passive"))
      (node (ref "C93") (pin "1") (pinfunction "1_1") (pintype "passive"))
      (node (ref "C94") (pin "1") (pinfunction "1_1") (pintype "passive"))
      (node (ref "C95") (pin "1") (pinfunction "1_1") (pintype "passive"))
      (node (ref "C96") (pin "1") (pinfunction "1_1") (pintype "passive"))
      (node (ref "C97") (pin "1") (pinfunction "1_1") (pintype "passive"))
      (node (ref "C98") (pin "1") (pinfunction "1_1") (pintype "passive"))
      (node (ref "C99") (pin "1") (pinfunction "1_1") (pintype "passive"))
      (node (ref "L5") (pin "1") (pinfunction "1_1") (pintype "passive"))
      (node (ref "Q2") (pin "2") (pinfunction "S_2") (pintype "passive"))
      (node (ref "R44") (pin "1") (pinfunction "1_1") (pintype "passive"))
      (node (ref "SW3") (pin "1") (pinfunction "1_1") (pintype "passive"))
      (node (ref "SW3") (pin "2") (pinfunction "2_2") (pintype "passive"))
      (node (ref "SW4") (pin "1") (pinfunction "1_1") (pintype "passive"))
      (node (ref "SW4") (pin "2") (pinfunction "2_2") (pintype "passive"))
      (node (ref "SW5") (pin "4") (pinfunction "4_4") (pintype "passive"))
      (node (ref "SW5") (pin "5") (pinfunction "5_5") (pintype "passive"))
      (node (ref "SW5") (pin "6") (pinfunction "6_6") (pintype "passive"))
      (node (ref "U10") (pin "3") (pinfunction "VSS_3") (pintype "power_in"))
      (node (ref "U11") (pin "3") (pinfunction "GND_3") (pintype "passive"))
      (node (ref "U12") (pin "3") (pinfunction "GND_3") (pintype "power_in"))
      (node (ref "U13") (pin "4") (pinfunction "GND_4") (pintype "passive"))
      (node (ref "U9") (pin "A11") (pinfunction "GND_A11") (pintype "power_in"))
      (node (ref "U9") (pin "A12") (pinfunction "GND_A12") (pintype "power_in"))
      (node (ref "U9") (pin "A2") (pinfunction "GND_A2") (pintype "power_in"))
      (node (ref "U9") (pin "A22") (pinfunction "GND_A22") (pintype "power_in"))
      (node (ref "U9") (pin "A3") (pinfunction "GND_A3") (pintype "power_in"))
      (node (ref "U9") (pin "A5") (pinfunction "GND_A5") (pintype "power_in"))
      (node (ref "U9") (pin "A7") (pinfunction "GND_A7") (pintype "power_in"))
      (node (ref "U9") (pin "A9") (pinfunction "GND_A9") (pintype "power_in"))
      (node (ref "U9") (pin "AA12") (pinfunction "GND_AA12") (pintype "power_in"))
      (node (ref "U9") (pin "AA2") (pinfunction "GND_AA2") (pintype "power_in"))
      (node (ref "U9") (pin "AA22") (pinfunction "GND_AA22") (pintype "power_in"))
      (node (ref "U9") (pin "AB19") (pinfunction "GND_AB19") (pintype "power_in"))
      (node (ref "U9") (pin "AB9") (pinfunction "GND_AB9") (pintype "power_in"))
      (node (ref "U9") (pin "B12") (pinfunction "GND_B12") (pintype "power_in"))
      (node (ref "U9") (pin "B19") (pinfunction "GND_B19") (pintype "power_in"))
      (node (ref "U9") (pin "B3") (pinfunction "GND_B3") (pintype "power_in"))
      (node (ref "U9") (pin "C10") (pinfunction "GND_C10") (pintype "power_in"))
      (node (ref "U9") (pin "C12") (pinfunction "GND_C12") (pintype "power_in"))
      (node (ref "U9") (pin "C16") (pinfunction "GND_C16") (pintype "power_in"))
      (node (ref "U9") (pin "C3") (pinfunction "GND_C3") (pintype "power_in"))
      (node (ref "U9") (pin "C6") (pinfunction "GND_C6") (pintype "power_in"))
      (node (ref "U9") (pin "D12") (pinfunction "GND_D12") (pintype "power_in"))
      (node (ref "U9") (pin "D13") (pinfunction "GND_D13") (pintype "power_in"))
      (node (ref "U9") (pin "D3") (pinfunction "GND_D3") (pintype "power_in"))
      (node (ref "U9") (pin "D4") (pinfunction "GND_D4") (pintype "power_in"))
      (node (ref "U9") (pin "D8") (pinfunction "GND_D8") (pintype "power_in"))
      (node (ref "U9") (pin "E11") (pinfunction "GND_E11") (pintype "power_in"))
      (node (ref "U9") (pin "E20") (pinfunction "GND_E20") (pintype "power_in"))
      (node (ref "U9") (pin "E4") (pinfunction "GND_E4") (pintype "power_in"))
      (node (ref "U9") (pin "E5") (pinfunction "GND_E5") (pintype "power_in"))
      (node (ref "U9") (pin "E7") (pinfunction "GND_E7") (pintype "power_in"))
      (node (ref "U9") (pin "E9") (pinfunction "GND_E9") (pintype "power_in"))
      (node (ref "U9") (pin "F11") (pinfunction "GND_F11") (pintype "power_in"))
      (node (ref "U9") (pin "F17") (pinfunction "GND_F17") (pintype "power_in"))
      (node (ref "U9") (pin "F5") (pinfunction "GND_F5") (pintype "power_in"))
      (node (ref "U9") (pin "G10") (pinfunction "GND_G10") (pintype "power_in"))
      (node (ref "U9") (pin "G12") (pinfunction "GND_G12") (pintype "power_in"))
      (node (ref "U9") (pin "G14") (pinfunction "GND_G14") (pintype "power_in"))
      (node (ref "U9") (pin "G5") (pinfunction "GND_G5") (pintype "power_in"))
      (node (ref "U9") (pin "G6") (pinfunction "GND_G6") (pintype "power_in"))
      (node (ref "U9") (pin "G7") (pinfunction "GND_G7") (pintype "power_in"))
      (node (ref "U9") (pin "G8") (pinfunction "GND_G8") (pintype "power_in"))
      (node (ref "U9") (pin "G9") (pinfunction "GND_G9") (pintype "power_in"))
      (node (ref "U9") (pin "H1") (pinfunction "GND_H1") (pintype "power_in"))
      (node (ref "U9") (pin "H11") (pinfunction "GND_H11") (pintype "power_in"))
      (node (ref "U9") (pin "H21") (pinfunction "GND_H21") (pintype "power_in"))
      (node (ref "U9") (pin "H7") (pinfunction "GND_H7") (pintype "power_in"))
      (node (ref "U9") (pin "H9") (pinfunction "GND_H9") (pintype "power_in"))
      (node (ref "U9") (pin "J10") (pinfunction "GND_J10") (pintype "power_in"))
      (node (ref "U9") (pin "J12") (pinfunction "GND_J12") (pintype "power_in"))
      (node (ref "U9") (pin "J18") (pinfunction "GND_J18") (pintype "power_in"))
      (node (ref "U9") (pin "J8") (pinfunction "GND_J8") (pintype "power_in"))
      (node (ref "U9") (pin "K11") (pinfunction "GND_K11") (pintype "power_in"))
      (node (ref "U9") (pin "K15") (pinfunction "GND_K15") (pintype "power_in"))
      (node (ref "U9") (pin "K5") (pinfunction "GND_K5") (pintype "power_in"))
      (node (ref "U9") (pin "K7") (pinfunction "GND_K7") (pintype "power_in"))
      (node (ref "U9") (pin "K9") (pinfunction "GNDADC_0_K9") (pintype "power_in"))
      (node (ref "U9") (pin "L2") (pinfunction "GND_L2") (pintype "power_in"))
      (node (ref "U9") (pin "L22") (pinfunction "GND_L22") (pintype "power_in"))
      (node (ref "U9") (pin "L8") (pinfunction "GND_L8") (pintype "power_in"))
      (node (ref "U9") (pin "M11") (pinfunction "GND_M11") (pintype "power_in"))
      (node (ref "U9") (pin "M19") (pinfunction "GND_M19") (pintype "power_in"))
      (node (ref "U9") (pin "M7") (pinfunction "GND_M7") (pintype "power_in"))
      (node (ref "U9") (pin "N10") (pinfunction "DXP_0_N10") (pintype "input"))
      (node (ref "U9") (pin "N16") (pinfunction "GND_N16") (pintype "power_in"))
      (node (ref "U9") (pin "N6") (pinfunction "GND_N6") (pintype "power_in"))
      (node (ref "U9") (pin "N8") (pinfunction "GND_N8") (pintype "power_in"))
      (node (ref "U9") (pin "N9") (pinfunction "DXN_0_N9") (pintype "input"))
      (node (ref "U9") (pin "P11") (pinfunction "GND_P11") (pintype "power_in"))
      (node (ref "U9") (pin "P13") (pinfunction "GND_P13") (pintype "power_in"))
      (node (ref "U9") (pin "P3") (pinfunction "GND_P3") (pintype "power_in"))
      (node (ref "U9") (pin "P7") (pinfunction "GND_P7") (pintype "power_in"))
      (node (ref "U9") (pin "P9") (pinfunction "GND_P9") (pintype "power_in"))
      (node (ref "U9") (pin "R10") (pinfunction "GND_R10") (pintype "power_in"))
      (node (ref "U9") (pin "R12") (pinfunction "GND_R12") (pintype "power_in"))
      (node (ref "U9") (pin "R20") (pinfunction "GND_R20") (pintype "power_in"))
      (node (ref "U9") (pin "R8") (pinfunction "GND_R8") (pintype "power_in"))
      (node (ref "U9") (pin "T11") (pinfunction "GND_T11") (pintype "power_in"))
      (node (ref "U9") (pin "T17") (pinfunction "GND_T17") (pintype "power_in"))
      (node (ref "U9") (pin "T7") (pinfunction "GND_T7") (pintype "power_in"))
      (node (ref "U9") (pin "T9") (pinfunction "GND_T9") (pintype "power_in"))
      (node (ref "U9") (pin "U14") (pinfunction "GND_U14") (pintype "power_in"))
      (node (ref "U9") (pin "U4") (pinfunction "GND_U4") (pintype "power_in"))
      (node (ref "U9") (pin "V1") (pinfunction "GND_V1") (pintype "power_in"))
      (node (ref "U9") (pin "V11") (pinfunction "GND_V11") (pintype "power_in"))
      (node (ref "U9") (pin "V21") (pinfunction "GND_V21") (pintype "power_in"))
      (node (ref "U9") (pin "W18") (pinfunction "GND_W18") (pintype "power_in"))
      (node (ref "U9") (pin "W8") (pinfunction "GND_W8") (pintype "power_in"))
      (node (ref "U9") (pin "Y15") (pinfunction "GND_Y15") (pintype "power_in"))
      (node (ref "U9") (pin "Y5") (pinfunction "GND_Y5") (pintype "power_in"))
      (node (ref "X1") (pin "2") (pinfunction "GND_2") (pintype "passive"))
    )
    (net (code "277") (name "Net-(C47-Pad2)") (class "Default")
      (node (ref "C47") (pin "2") (pinfunction "2_2") (pintype "passive"))
      (node (ref "R40") (pin "1") (pinfunction "1_1") (pintype "passive"))
      (node (ref "R41") (pin "2") (pinfunction "2_2") (pintype "passive"))
      (node (ref "SW3") (pin "3") (pinfunction "3_3") (pintype "passive"))
      (node (ref "SW3") (pin "4") (pinfunction "4_4") (pintype "passive"))
    )
    (net (code "278") (name "Net-(C65-Pad2)") (class "Default")
      (node (ref "C65") (pin "2") (pinfunction "2_2") (pintype "passive"))
      (node (ref "R42") (pin "1") (pinfunction "1_1") (pintype "passive"))
      (node (ref "R43") (pin "2") (pinfunction "2_2") (pintype "passive"))
      (node (ref "SW4") (pin "3") (pinfunction "3_3") (pintype "passive"))
      (node (ref "SW4") (pin "4") (pinfunction "4_4") (pintype "passive"))
    )
    (net (code "279") (name "Net-(DS1-K)") (class "Default")
      (node (ref "DS1") (pin "2") (pinfunction "K_2") (pintype "passive"))
      (node (ref "R44") (pin "2") (pinfunction "2_2") (pintype "passive"))
    )
    (net (code "280") (name "Net-(DS2-A)") (class "Default")
      (node (ref "DS2") (pin "1") (pinfunction "A_1") (pintype "passive"))
      (node (ref "R45") (pin "1") (pinfunction "1_1") (pintype "passive"))
    )
    (net (code "281") (name "Net-(U9G-MGTRREF_216)") (class "Default")
      (node (ref "R32") (pin "2") (pinfunction "2_2") (pintype "passive"))
      (node (ref "U9") (pin "F8") (pinfunction "MGTRREF_216_F8") (pintype "input"))
    )
    (net (code "282") (name "unconnected-(U9A-IO_0_14-PadP20)") (class "Default")
      (node (ref "U9") (pin "P20") (pinfunction "IO_0_14_P20") (pintype "bidirectional+no_connect"))
    )
    (net (code "283") (name "unconnected-(U9A-IO_L3N_T0_DQS_EMCCLK_14-PadV22)") (class "Default")
      (node (ref "U9") (pin "V22") (pinfunction "IO_L3N_T0_DQS_EMCCLK_14_V22") (pintype "bidirectional+no_connect"))
    )
    (net (code "284") (name "unconnected-(U9A-IO_L5N_T0_D07_14-PadR19)") (class "Default")
      (node (ref "U9") (pin "R19") (pinfunction "IO_L5N_T0_D07_14_R19") (pintype "bidirectional+no_connect"))
    )
    (net (code "285") (name "unconnected-(U9A-IO_L5P_T0_D06_14-PadP19)") (class "Default")
      (node (ref "U9") (pin "P19") (pinfunction "IO_L5P_T0_D06_14_P19") (pintype "bidirectional+no_connect"))
    )
    (net (code "286") (name "unconnected-(U9A-IO_L6N_T0_D08_VREF_14-PadT20)") (class "Default")
      (node (ref "U9") (pin "T20") (pinfunction "IO_L6N_T0_D08_VREF_14_T20") (pintype "bidirectional+no_connect"))
    )
    (net (code "287") (name "unconnected-(U9A-IO_L7P_T1_D09_14-PadW21)") (class "Default")
      (node (ref "U9") (pin "W21") (pinfunction "IO_L7P_T1_D09_14_W21") (pintype "bidirectional+no_connect"))
    )
    (net (code "288") (name "unconnected-(U9A-IO_L12N_T1_MRCC_14-PadW20)") (class "Default")
      (node (ref "U9") (pin "W20") (pinfunction "IO_L12N_T1_MRCC_14_W20") (pintype "input+no_connect"))
    )
    (net (code "289") (name "unconnected-(U9A-IO_L13N_T2_MRCC_14-PadY19)") (class "Default")
      (node (ref "U9") (pin "Y19") (pinfunction "IO_L13N_T2_MRCC_14_Y19") (pintype "bidirectional+no_connect"))
    )
    (net (code "290") (name "unconnected-(U9A-IO_L16N_T2_A15_D31_14-PadW17)") (class "Default")
      (node (ref "U9") (pin "W17") (pinfunction "IO_L16N_T2_A15_D31_14_W17") (pintype "bidirectional+no_connect"))
    )
    (net (code "291") (name "unconnected-(U9A-IO_L16P_T2_CSI_B_14-PadV17)") (class "Default")
      (node (ref "U9") (pin "V17") (pinfunction "IO_L16P_T2_CSI_B_14_V17") (pintype "bidirectional+no_connect"))
    )
    (net (code "292") (name "unconnected-(U9A-IO_L17P_T2_A14_D30_14-PadAA18)") (class "Default")
      (node (ref "U9") (pin "AA18") (pinfunction "IO_L17P_T2_A14_D30_14_AA18") (pintype "bidirectional+no_connect"))
    )
    (net (code "293") (name "unconnected-(U9A-IO_L19N_T3_A09_D25_VREF_14-PadR14)") (class "Default")
      (node (ref "U9") (pin "R14") (pinfunction "IO_L19N_T3_A09_D25_VREF_14_R14") (pintype "bidirectional+no_connect"))
    )
    (net (code "294") (name "unconnected-(U9A-IO_L20N_T3_A07_D23_14-PadT18)") (class "Default")
      (node (ref "U9") (pin "T18") (pinfunction "IO_L20N_T3_A07_D23_14_T18") (pintype "bidirectional+no_connect"))
    )
    (net (code "295") (name "unconnected-(U9A-IO_L20P_T3_A08_D24_14-PadR18)") (class "Default")
      (node (ref "U9") (pin "R18") (pinfunction "IO_L20P_T3_A08_D24_14_R18") (pintype "bidirectional+no_connect"))
    )
    (net (code "296") (name "unconnected-(U9A-IO_L21P_T3_DQS_14-PadN17)") (class "Default")
      (node (ref "U9") (pin "N17") (pinfunction "IO_L21P_T3_DQS_14_N17") (pintype "bidirectional+no_connect"))
    )
    (net (code "297") (name "unconnected-(U9D-IO_0_34-PadT3)") (class "Default")
      (node (ref "U9") (pin "T3") (pinfunction "IO_0_34_T3") (pintype "bidirectional+no_connect"))
    )
    (net (code "298") (name "unconnected-(U9D-IO_25_34-PadU7)") (class "Default")
      (node (ref "U9") (pin "U7") (pinfunction "IO_25_34_U7") (pintype "bidirectional+no_connect"))
    )
    (net (code "299") (name "unconnected-(U9E-IO_0_35-PadF4)") (class "Default")
      (node (ref "U9") (pin "F4") (pinfunction "IO_0_35_F4") (pintype "bidirectional"))
    )
    (net (code "300") (name "unconnected-(U9E-IO_25_35-PadL6)") (class "Default")
      (node (ref "U9") (pin "L6") (pinfunction "IO_25_35_L6") (pintype "bidirectional+no_connect"))
    )
    (net (code "301") (name "unconnected-(U9E-IO_L19N_T3_VREF_35-PadN3)") (class "Default")
      (node (ref "U9") (pin "N3") (pinfunction "IO_L19N_T3_VREF_35_N3") (pintype "bidirectional+no_connect"))
    )
    (net (code "302") (name "unconnected-(U9E-IO_L19P_T3_35-PadN4)") (class "Default")
      (node (ref "U9") (pin "N4") (pinfunction "IO_L19P_T3_35_N4") (pintype "bidirectional+no_connect"))
    )
    (net (code "303") (name "unconnected-(U9E-IO_L21N_T3_DQS_35-PadP4)") (class "Default")
      (node (ref "U9") (pin "P4") (pinfunction "IO_L21N_T3_DQS_35_P4") (pintype "bidirectional+no_connect"))
    )
    (net (code "304") (name "unconnected-(U9E-IO_L21P_T3_DQS_35-PadP5)") (class "Default")
      (node (ref "U9") (pin "P5") (pinfunction "IO_L21P_T3_DQS_35_P5") (pintype "bidirectional+no_connect"))
    )
    (net (code "305") (name "unconnected-(U9E-IO_L22N_T3_35-PadN2)") (class "Default")
      (node (ref "U9") (pin "N2") (pinfunction "IO_L22N_T3_35_N2") (pintype "bidirectional+no_connect"))
    )
    (net (code "306") (name "unconnected-(U9E-IO_L22P_T3_35-PadP2)") (class "Default")
      (node (ref "U9") (pin "P2") (pinfunction "IO_L22P_T3_35_P2") (pintype "bidirectional+no_connect"))
    )
    (net (code "307") (name "unconnected-(U9E-IO_L23N_T3_35-PadM5)") (class "Default")
      (node (ref "U9") (pin "M5") (pinfunction "IO_L23N_T3_35_M5") (pintype "bidirectional+no_connect"))
    )
    (net (code "308") (name "unconnected-(U9E-IO_L23P_T3_35-PadM6)") (class "Default")
      (node (ref "U9") (pin "M6") (pinfunction "IO_L23P_T3_35_M6") (pintype "bidirectional+no_connect"))
    )
    (net (code "309") (name "unconnected-(U9E-IO_L24N_T3_35-PadN5)") (class "Default")
      (node (ref "U9") (pin "N5") (pinfunction "IO_L24N_T3_35_N5") (pintype "bidirectional+no_connect"))
    )
    (net (code "310") (name "unconnected-(U9E-IO_L24P_T3_35-PadP6)") (class "Default")
      (node (ref "U9") (pin "P6") (pinfunction "IO_L24P_T3_35_P6") (pintype "bidirectional+no_connect"))
    )
    (net (code "311") (name "unconnected-(U9G-MGTREFCLK1N_216-PadE10)") (class "Default")
      (node (ref "U9") (pin "E10") (pinfunction "MGTREFCLK1N_216_E10") (pintype "input+no_connect"))
    )
    (net (code "312") (name "unconnected-(U9G-MGTREFCLK1P_216-PadF10)") (class "Default")
      (node (ref "U9") (pin "F10") (pinfunction "MGTREFCLK1P_216_F10") (pintype "input+no_connect"))
    )
    (net (code "313") (name "unconnected-(U9L-NC-PadAA9)") (class "Default")
      (node (ref "U9") (pin "AA9") (pinfunction "NC_AA9") (pintype "passive+no_connect"))
    )
    (net (code "314") (name "unconnected-(U9L-NC-PadAA10)") (class "Default")
      (node (ref "U9") (pin "AA10") (pinfunction "NC_AA10") (pintype "passive+no_connect"))
    )
    (net (code "315") (name "unconnected-(U9L-NC-PadAA11)") (class "Default")
      (node (ref "U9") (pin "AA11") (pinfunction "NC_AA11") (pintype "passive+no_connect"))
    )
    (net (code "316") (name "unconnected-(U9L-NC-PadAA13)") (class "Default")
      (node (ref "U9") (pin "AA13") (pinfunction "NC_AA13") (pintype "passive+no_connect"))
    )
    (net (code "317") (name "unconnected-(U9L-NC-PadAA14)") (class "Default")
      (node (ref "U9") (pin "AA14") (pinfunction "NC_AA14") (pintype "passive+no_connect"))
    )
    (net (code "318") (name "unconnected-(U9L-NC-PadAA15)") (class "Default")
      (node (ref "U9") (pin "AA15") (pinfunction "NC_AA15") (pintype "passive+no_connect"))
    )
    (net (code "319") (name "unconnected-(U9L-NC-PadAA16)") (class "Default")
      (node (ref "U9") (pin "AA16") (pinfunction "NC_AA16") (pintype "passive+no_connect"))
    )
    (net (code "320") (name "unconnected-(U9L-NC-PadAB10)") (class "Default")
      (node (ref "U9") (pin "AB10") (pinfunction "NC_AB10") (pintype "passive+no_connect"))
    )
    (net (code "321") (name "unconnected-(U9L-NC-PadAB11)") (class "Default")
      (node (ref "U9") (pin "AB11") (pinfunction "NC_AB11") (pintype "passive+no_connect"))
    )
    (net (code "322") (name "unconnected-(U9L-NC-PadAB12)") (class "Default")
      (node (ref "U9") (pin "AB12") (pinfunction "NC_AB12") (pintype "passive+no_connect"))
    )
    (net (code "323") (name "unconnected-(U9L-NC-PadAB13)") (class "Default")
      (node (ref "U9") (pin "AB13") (pinfunction "NC_AB13") (pintype "passive+no_connect"))
    )
    (net (code "324") (name "unconnected-(U9L-NC-PadAB15)") (class "Default")
      (node (ref "U9") (pin "AB15") (pinfunction "NC_AB15") (pintype "passive+no_connect"))
    )
    (net (code "325") (name "unconnected-(U9L-NC-PadAB16)") (class "Default")
      (node (ref "U9") (pin "AB16") (pinfunction "NC_AB16") (pintype "passive+no_connect"))
    )
    (net (code "326") (name "unconnected-(U9L-NC-PadAB17)") (class "Default")
      (node (ref "U9") (pin "AB17") (pinfunction "NC_AB17") (pintype "passive+no_connect"))
    )
    (net (code "327") (name "unconnected-(U9L-NC-PadT14)") (class "Default")
      (node (ref "U9") (pin "T14") (pinfunction "NC_T14") (pintype "passive+no_connect"))
    )
    (net (code "328") (name "unconnected-(U9L-NC-PadT15)") (class "Default")
      (node (ref "U9") (pin "T15") (pinfunction "NC_T15") (pintype "passive+no_connect"))
    )
    (net (code "329") (name "unconnected-(U9L-NC-PadT16)") (class "Default")
      (node (ref "U9") (pin "T16") (pinfunction "NC_T16") (pintype "passive+no_connect"))
    )
    (net (code "330") (name "unconnected-(U9L-NC-PadU15)") (class "Default")
      (node (ref "U9") (pin "U15") (pinfunction "NC_U15") (pintype "passive+no_connect"))
    )
    (net (code "331") (name "unconnected-(U9L-NC-PadU16)") (class "Default")
      (node (ref "U9") (pin "U16") (pinfunction "NC_U16") (pintype "passive+no_connect"))
    )
    (net (code "332") (name "unconnected-(U9L-NC-PadV10)") (class "Default")
      (node (ref "U9") (pin "V10") (pinfunction "NC_V10") (pintype "passive+no_connect"))
    )
    (net (code "333") (name "unconnected-(U9L-NC-PadV13)") (class "Default")
      (node (ref "U9") (pin "V13") (pinfunction "NC_V13") (pintype "passive+no_connect"))
    )
    (net (code "334") (name "unconnected-(U9L-NC-PadV14)") (class "Default")
      (node (ref "U9") (pin "V14") (pinfunction "NC_V14") (pintype "passive+no_connect"))
    )
    (net (code "335") (name "unconnected-(U9L-NC-PadV15)") (class "Default")
      (node (ref "U9") (pin "V15") (pinfunction "NC_V15") (pintype "passive+no_connect"))
    )
    (net (code "336") (name "unconnected-(U9L-NC-PadW10)") (class "Default")
      (node (ref "U9") (pin "W10") (pinfunction "NC_W10") (pintype "passive+no_connect"))
    )
    (net (code "337") (name "unconnected-(U9L-NC-PadW11)") (class "Default")
      (node (ref "U9") (pin "W11") (pinfunction "NC_W11") (pintype "passive+no_connect"))
    )
    (net (code "338") (name "unconnected-(U9L-NC-PadW12)") (class "Default")
      (node (ref "U9") (pin "W12") (pinfunction "NC_W12") (pintype "passive+no_connect"))
    )
    (net (code "339") (name "unconnected-(U9L-NC-PadW14)") (class "Default")
      (node (ref "U9") (pin "W14") (pinfunction "NC_W14") (pintype "passive+no_connect"))
    )
    (net (code "340") (name "unconnected-(U9L-NC-PadW15)") (class "Default")
      (node (ref "U9") (pin "W15") (pinfunction "NC_W15") (pintype "passive+no_connect"))
    )
    (net (code "341") (name "unconnected-(U9L-NC-PadW16)") (class "Default")
      (node (ref "U9") (pin "W16") (pinfunction "NC_W16") (pintype "passive+no_connect"))
    )
    (net (code "342") (name "unconnected-(U9L-NC-PadY11)") (class "Default")
      (node (ref "U9") (pin "Y11") (pinfunction "NC_Y11") (pintype "passive+no_connect"))
    )
    (net (code "343") (name "unconnected-(U9L-NC-PadY12)") (class "Default")
      (node (ref "U9") (pin "Y12") (pinfunction "NC_Y12") (pintype "passive+no_connect"))
    )
    (net (code "344") (name "unconnected-(U9L-NC-PadY13)") (class "Default")
      (node (ref "U9") (pin "Y13") (pinfunction "NC_Y13") (pintype "passive+no_connect"))
    )
    (net (code "345") (name "unconnected-(U9L-NC-PadY14)") (class "Default")
      (node (ref "U9") (pin "Y14") (pinfunction "NC_Y14") (pintype "passive+no_connect"))
    )
    (net (code "346") (name "unconnected-(U9L-NC-PadY16)") (class "Default")
      (node (ref "U9") (pin "Y16") (pinfunction "NC_Y16") (pintype "passive+no_connect"))
    )
    (net (code "347") (name "unconnected-(U9L-NC-PadY17)") (class "Default")
      (node (ref "U9") (pin "Y17") (pinfunction "NC_Y17") (pintype "passive+no_connect"))
    )
    (net (code "348") (name "unconnected-(U11-NC-Pad2)") (class "Default")
      (node (ref "U11") (pin "2") (pinfunction "NC_2") (pintype "passive+no_connect"))
    )
  )
)
